# Sheet_1_2023-10-08.net
KiCad netlist of a schematic drawn in Altium Designer
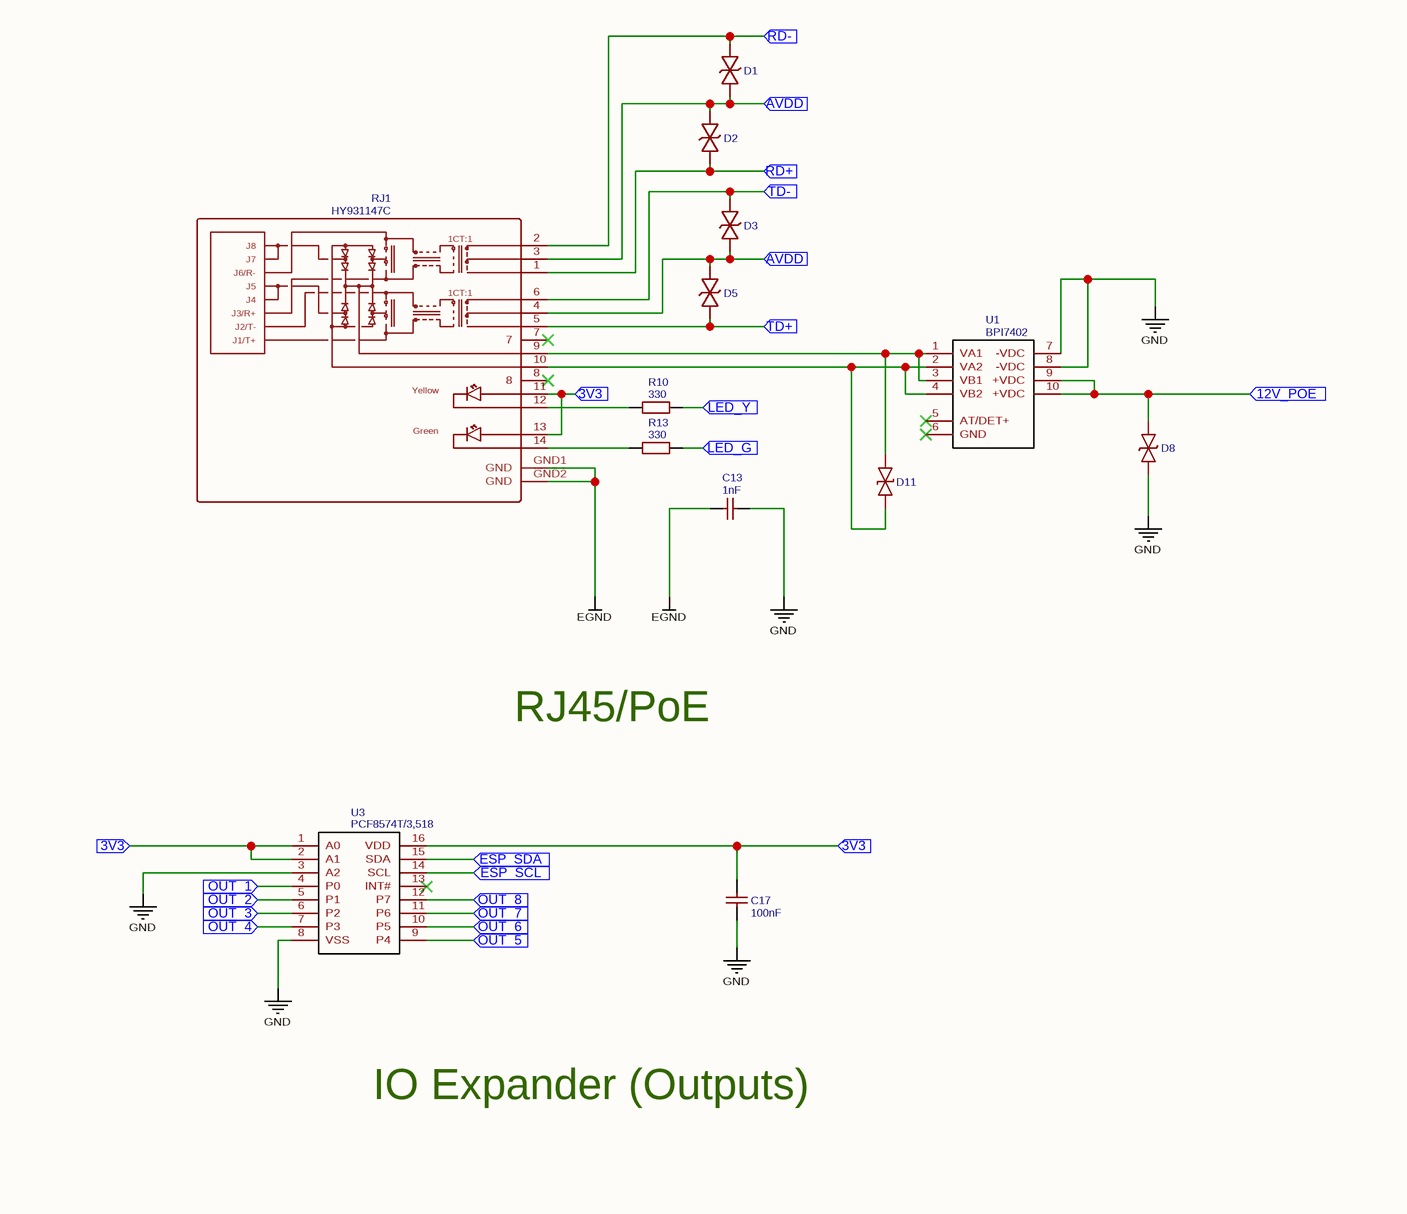
[diagram p0: Sheet_1_2023-10-08.schdoc, top left]
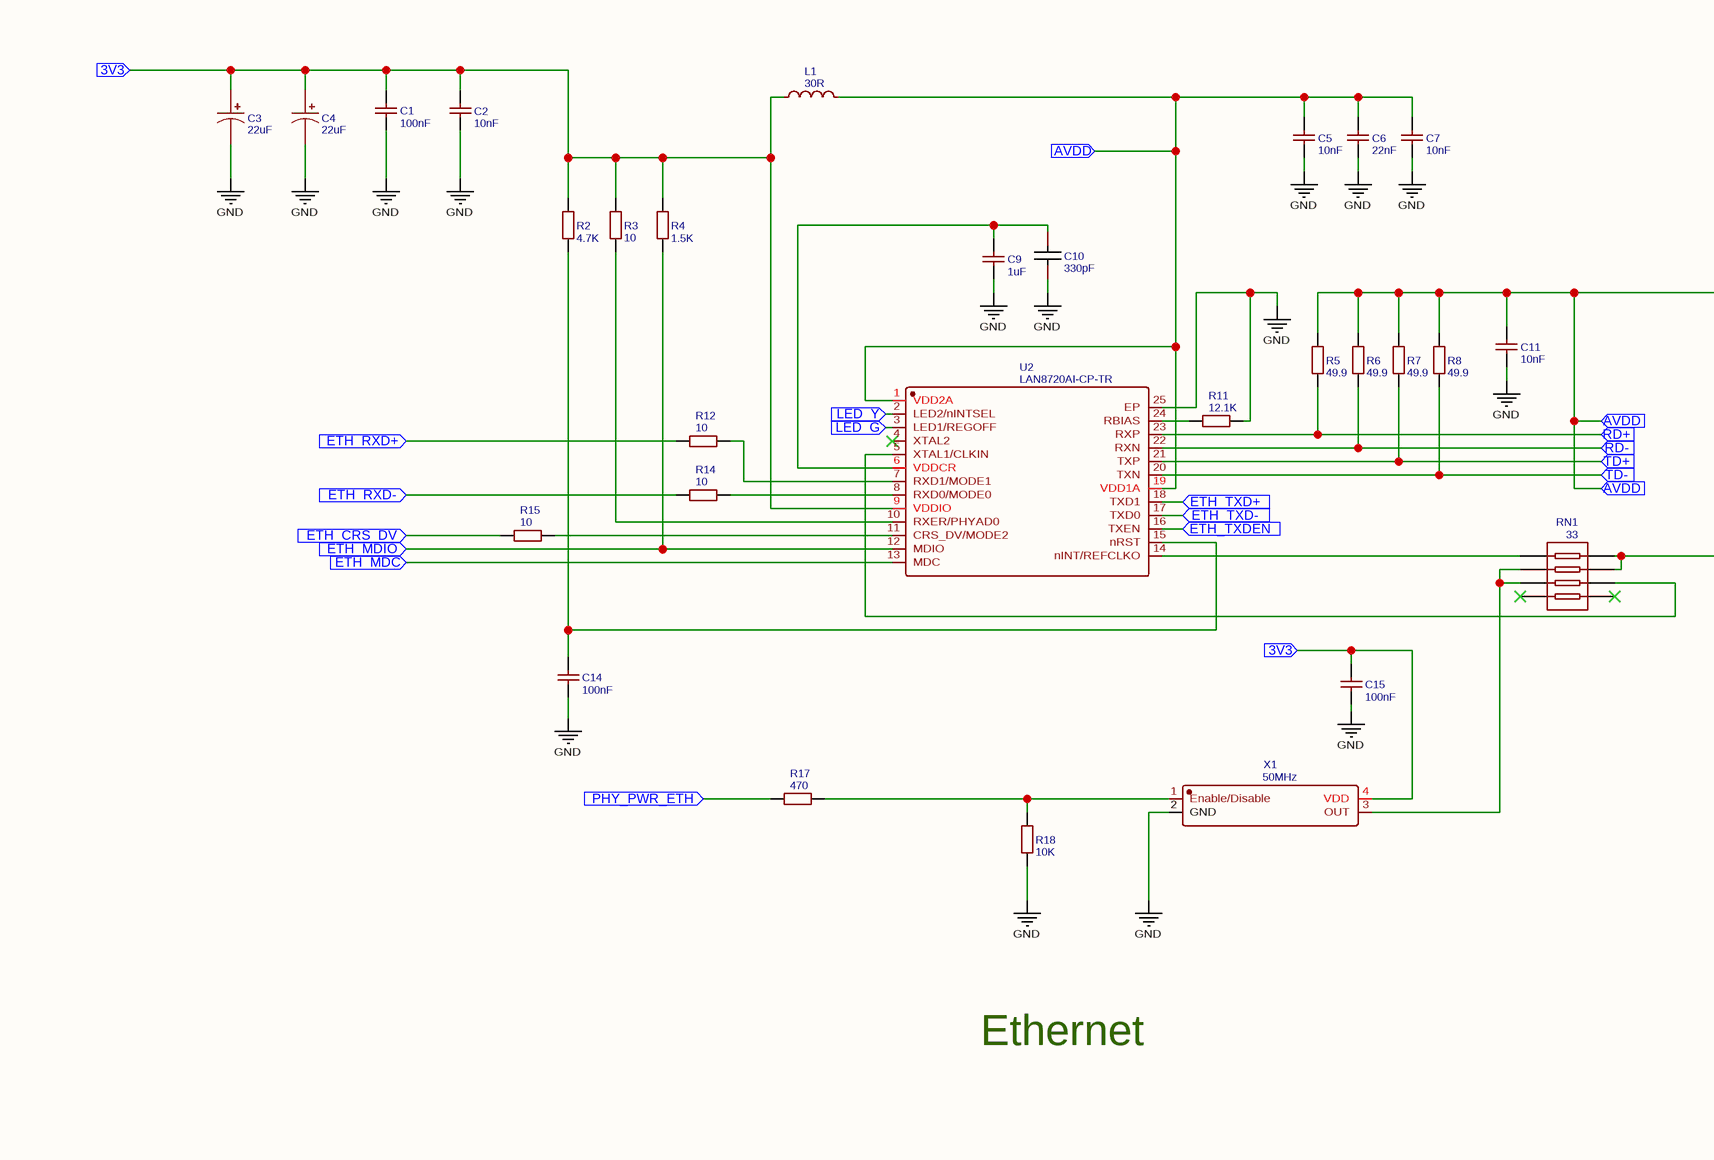
[diagram p1: Sheet_1_2023-10-08.schdoc, top middle]
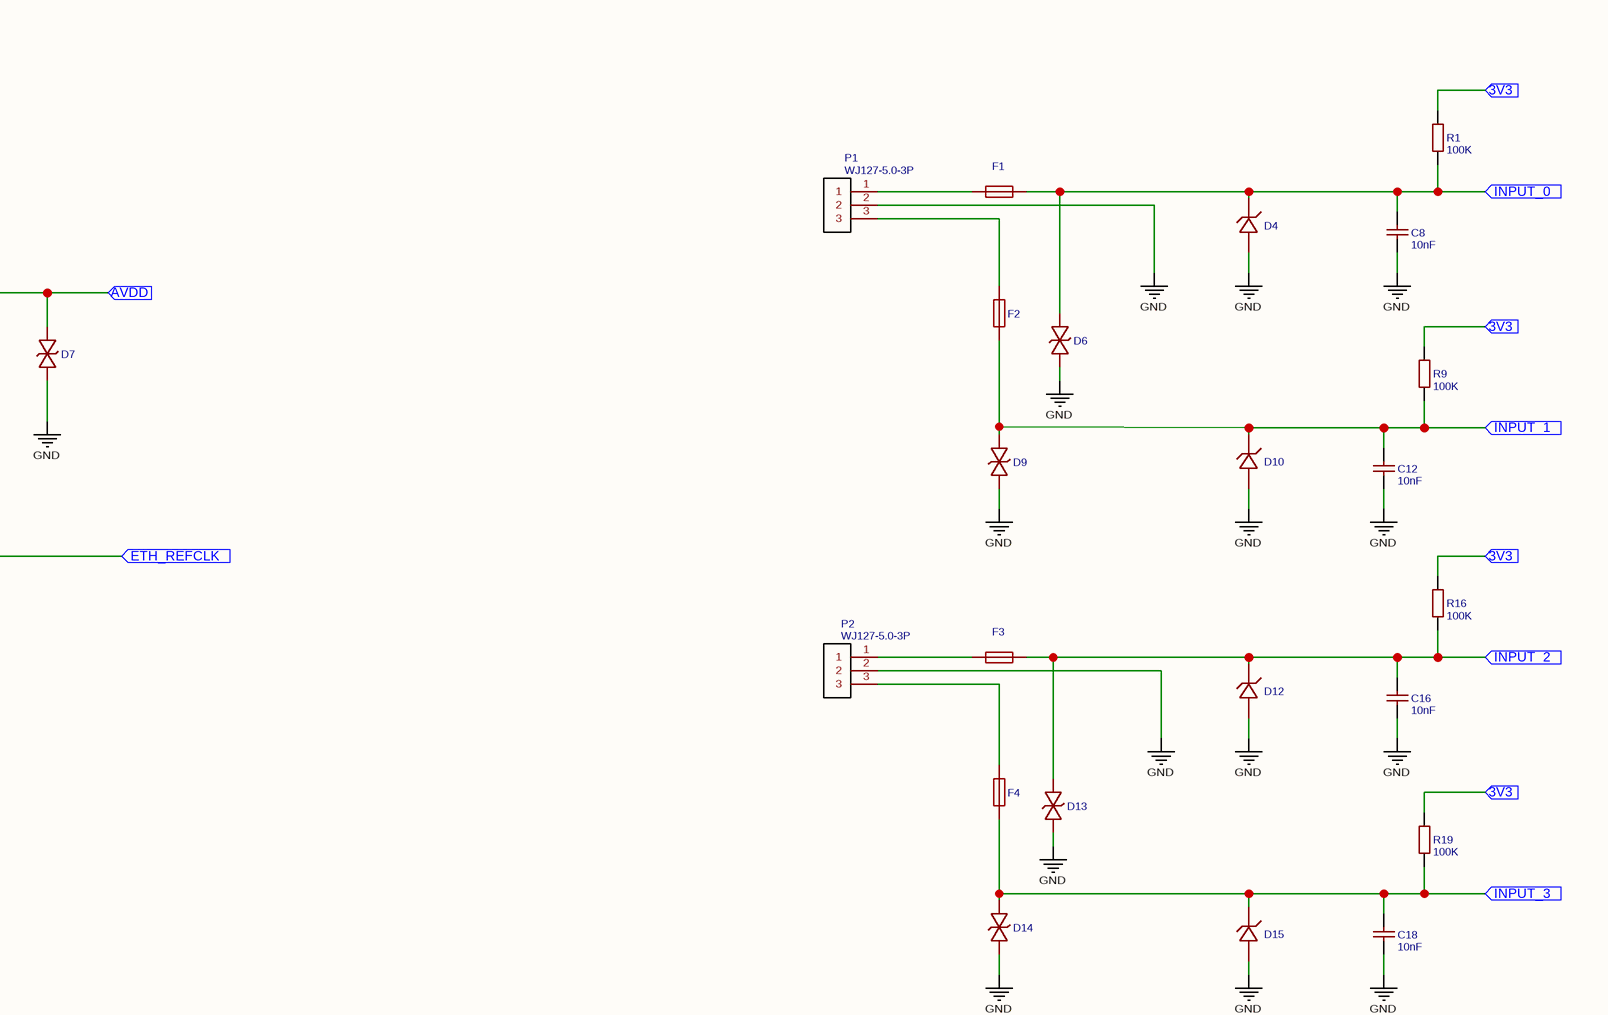
[diagram p2: Sheet_1_2023-10-08.schdoc, top right]
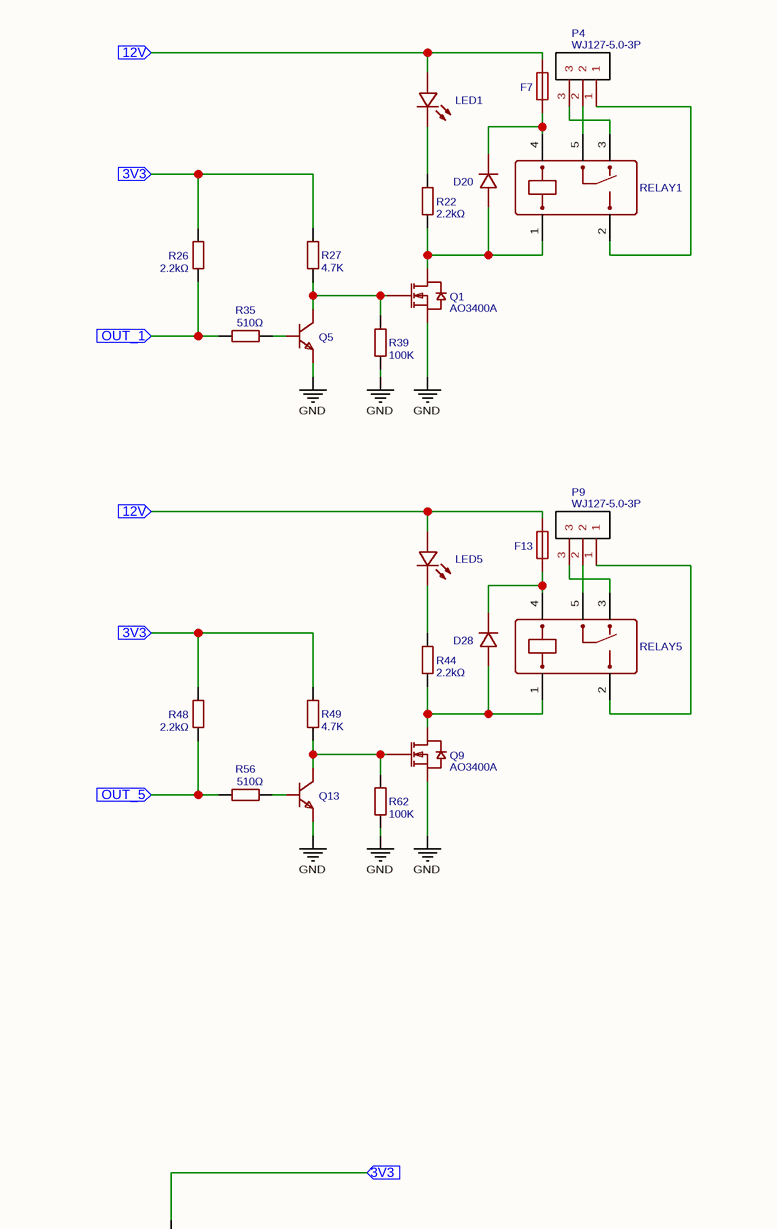
[diagram p3: Sheet_1_2023-10-08.schdoc, centre left]
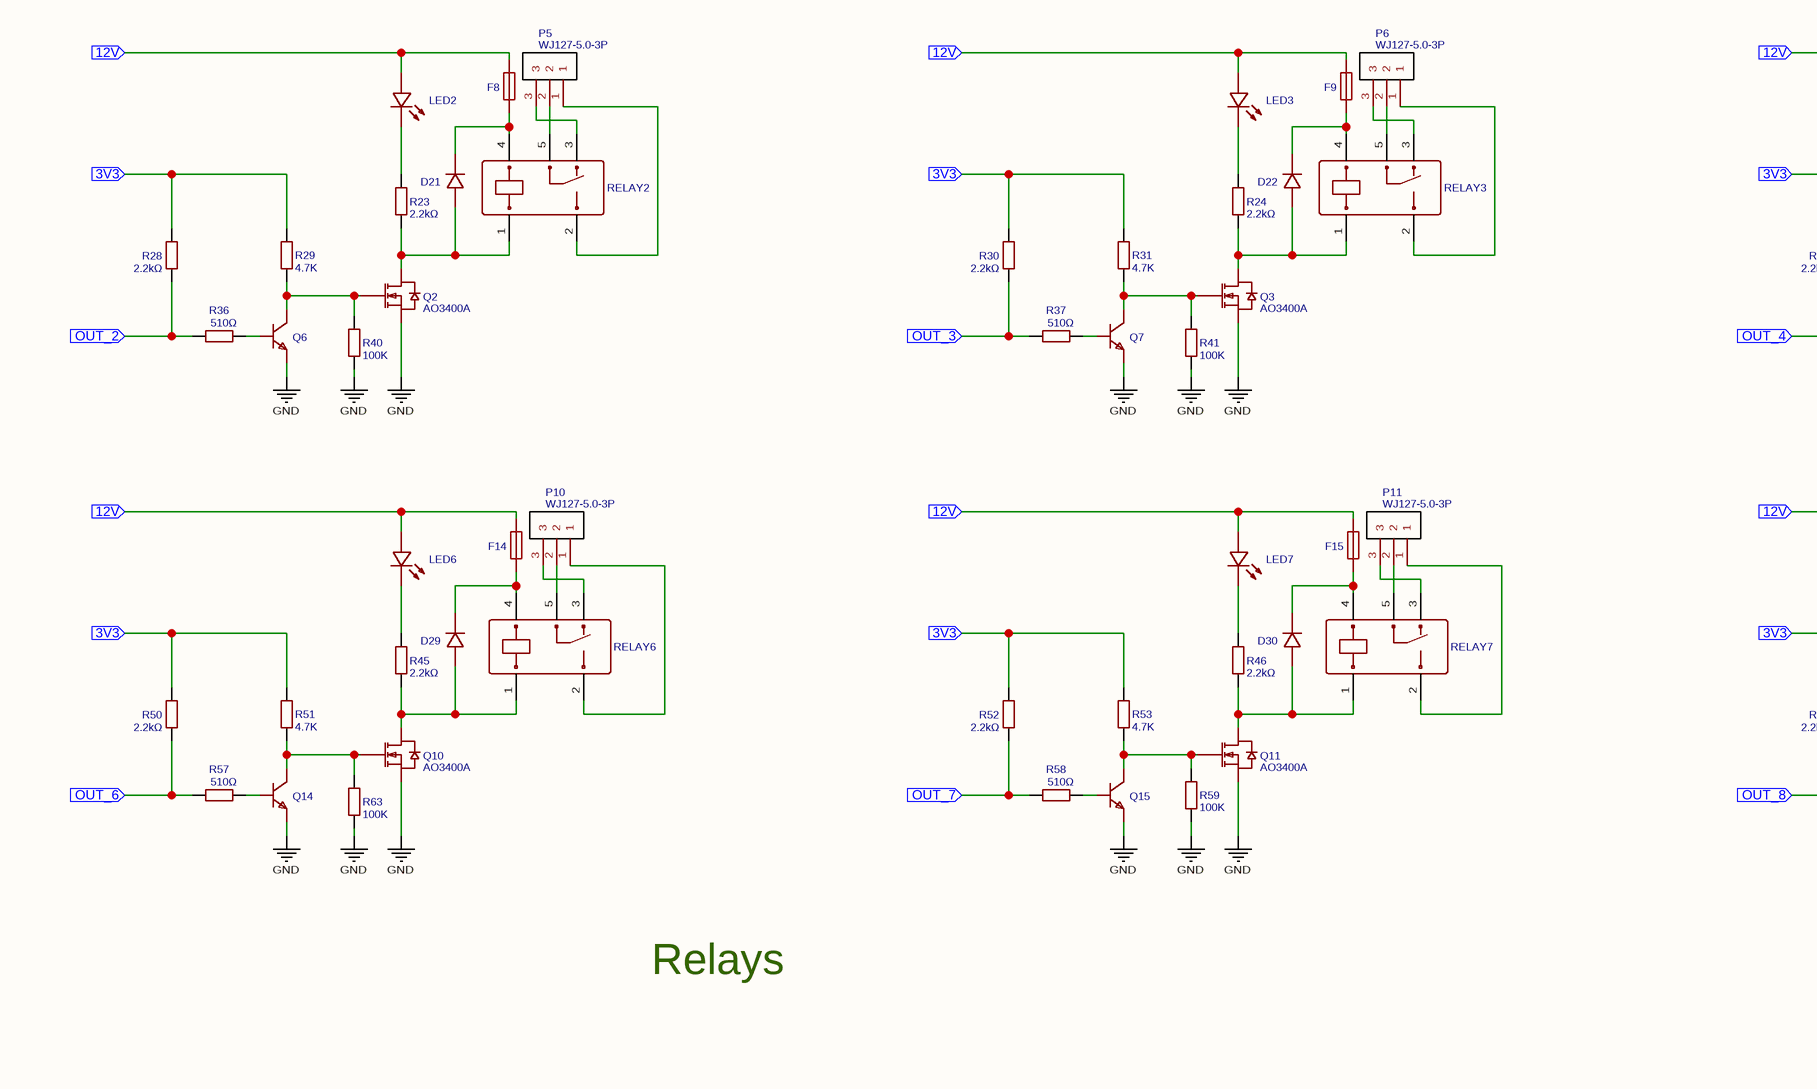
[diagram p4: Sheet_1_2023-10-08.schdoc, centre middle]
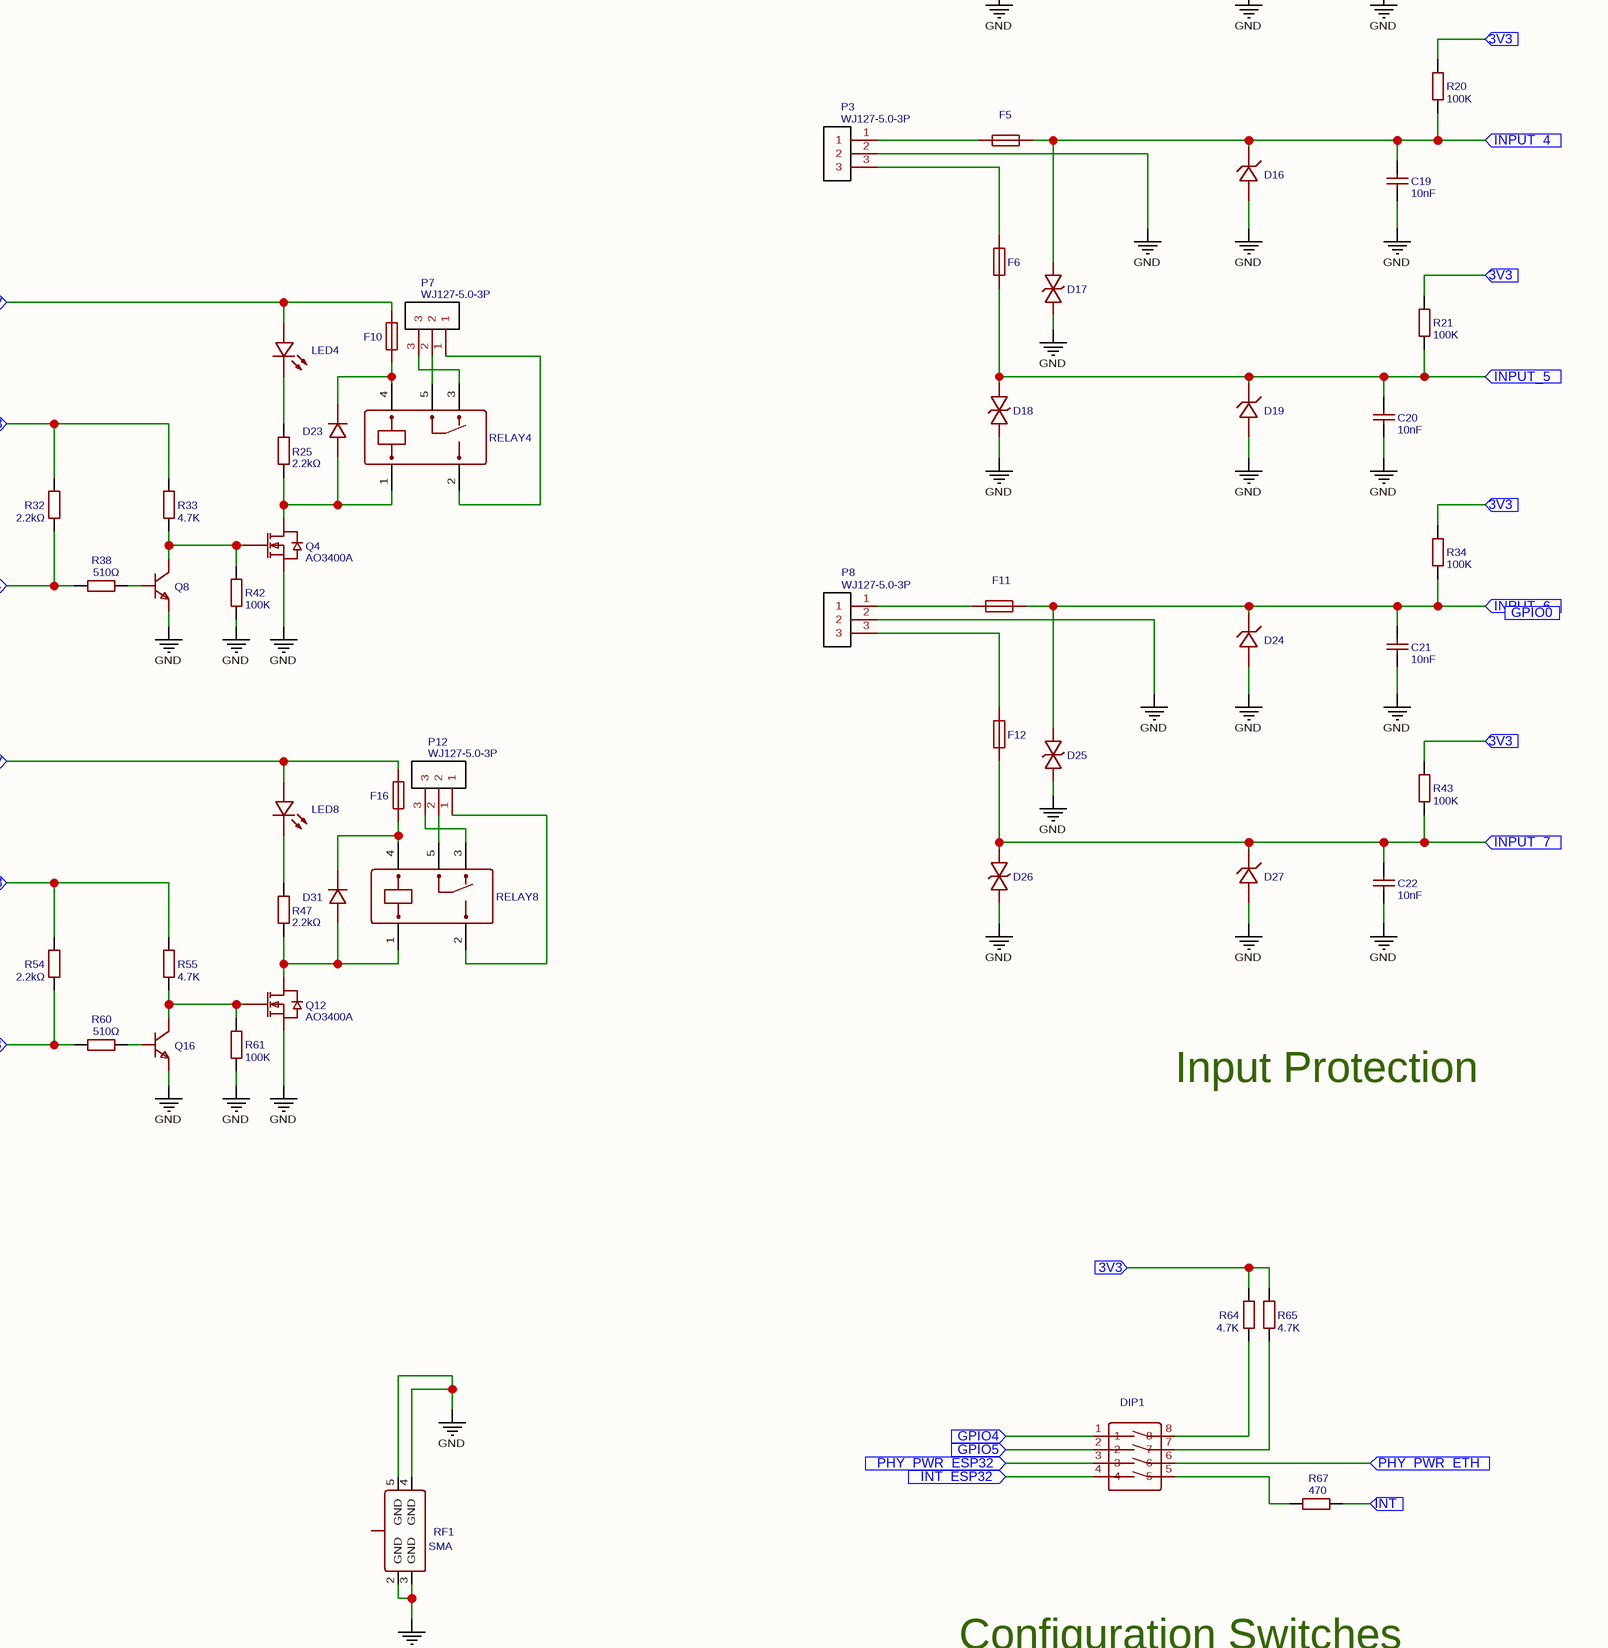
[diagram p5: Sheet_1_2023-10-08.schdoc, centre right]
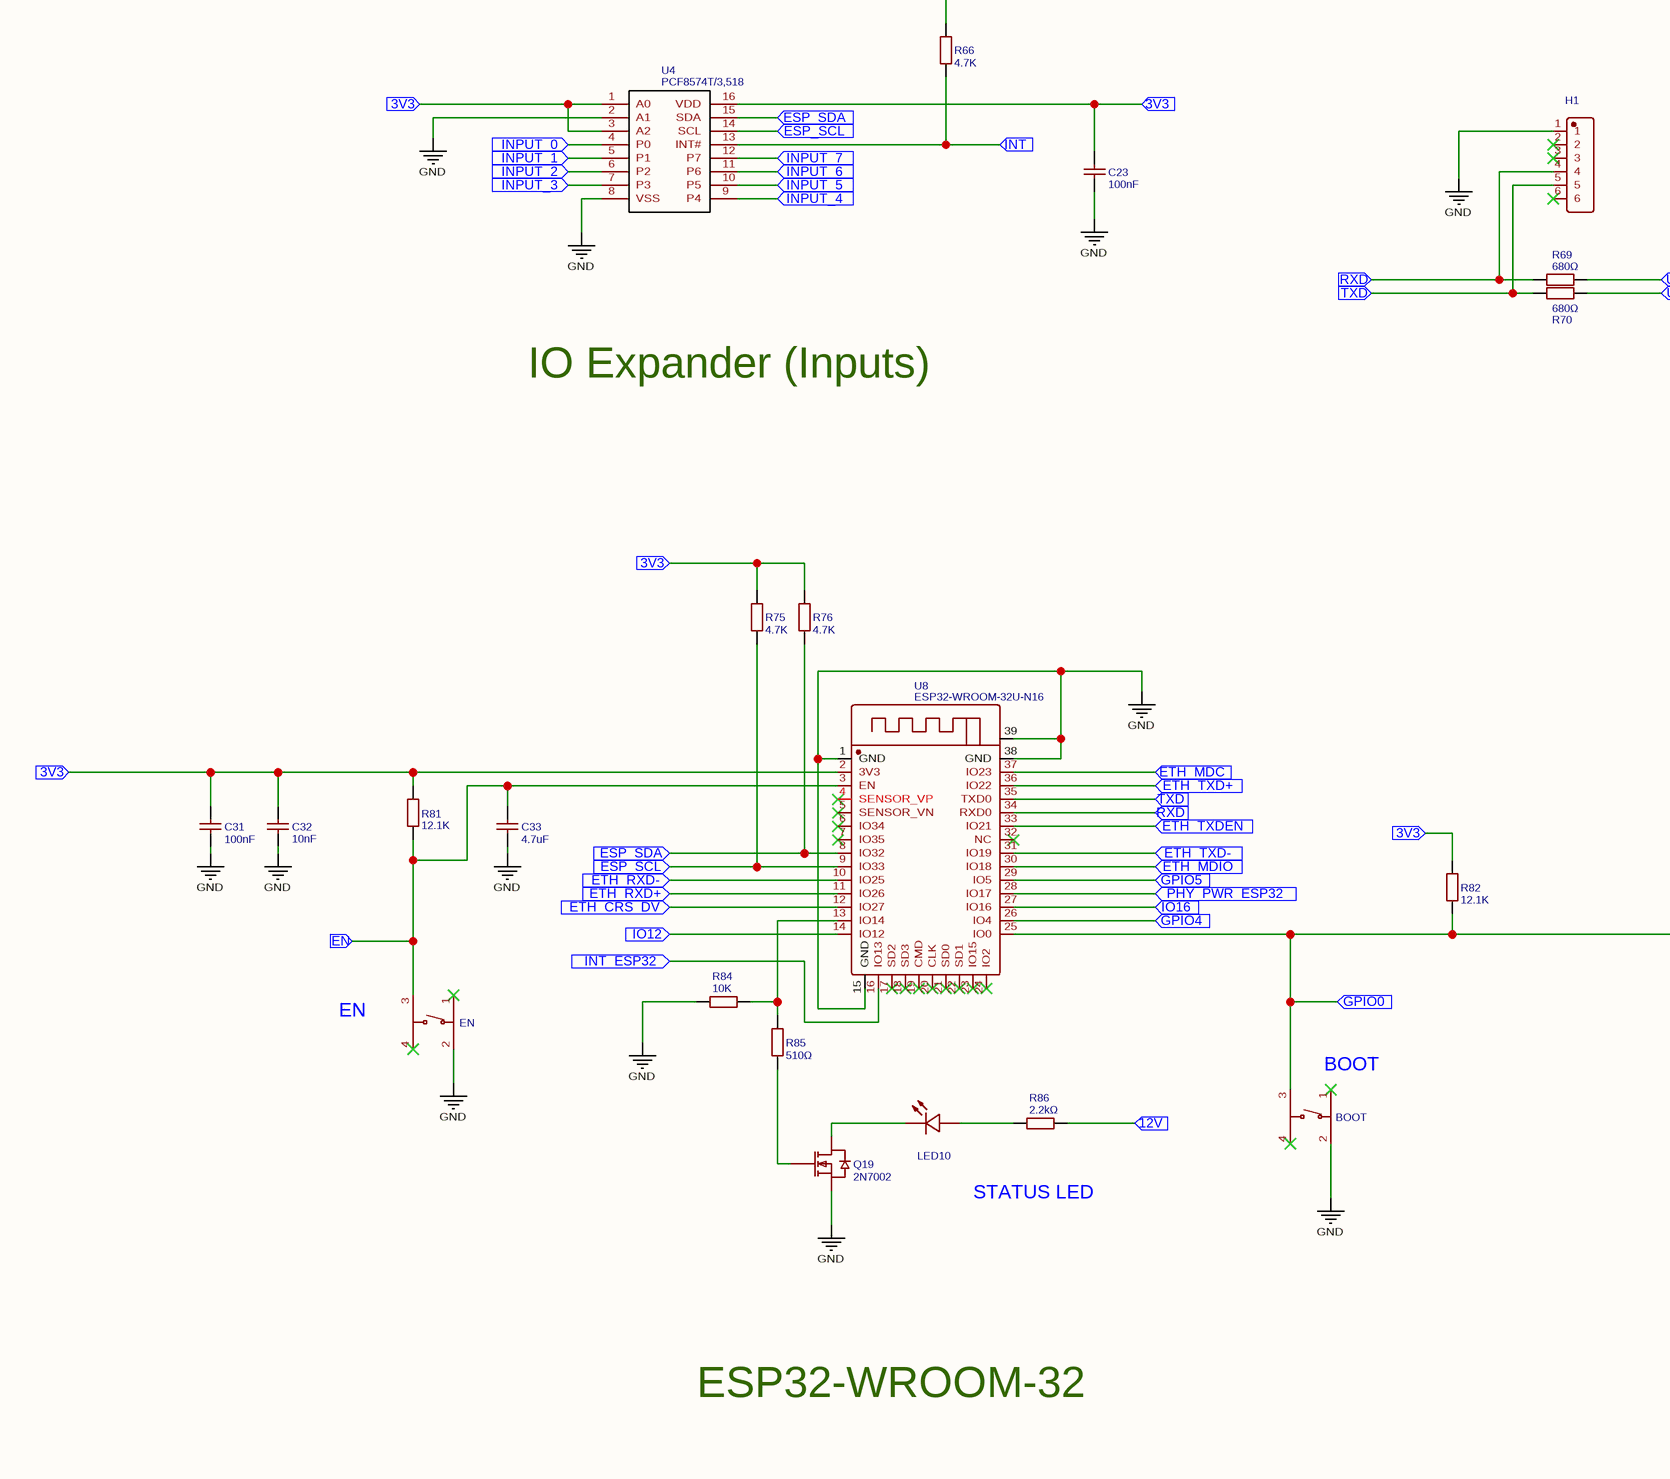
[diagram p6: Sheet_1_2023-10-08.schdoc, bottom left]
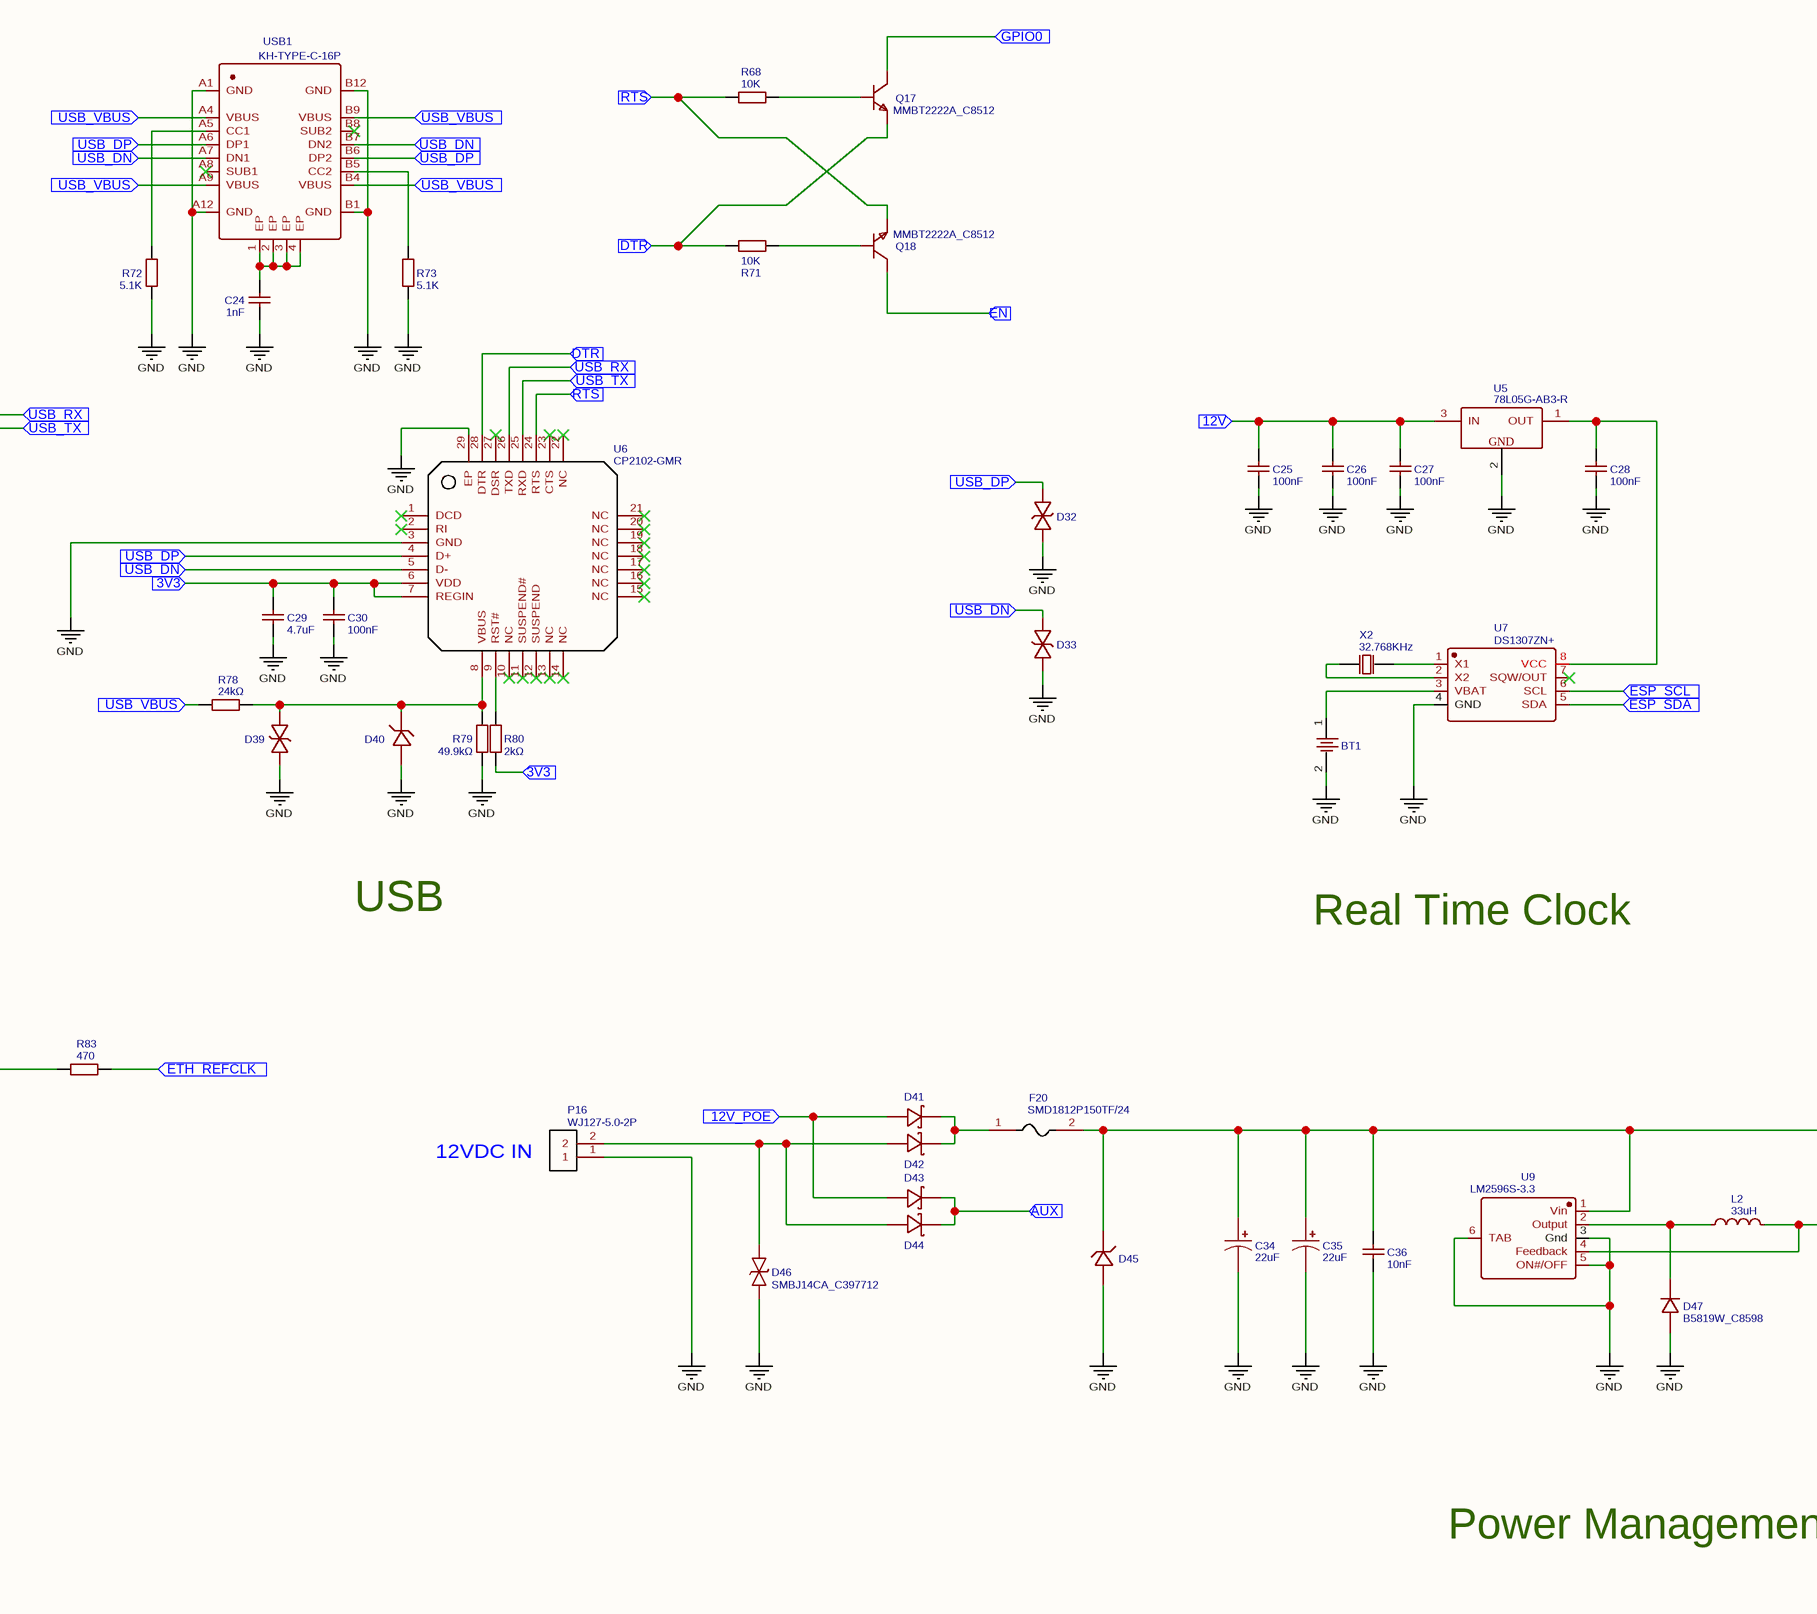
[diagram p7: Sheet_1_2023-10-08.schdoc, bottom middle]
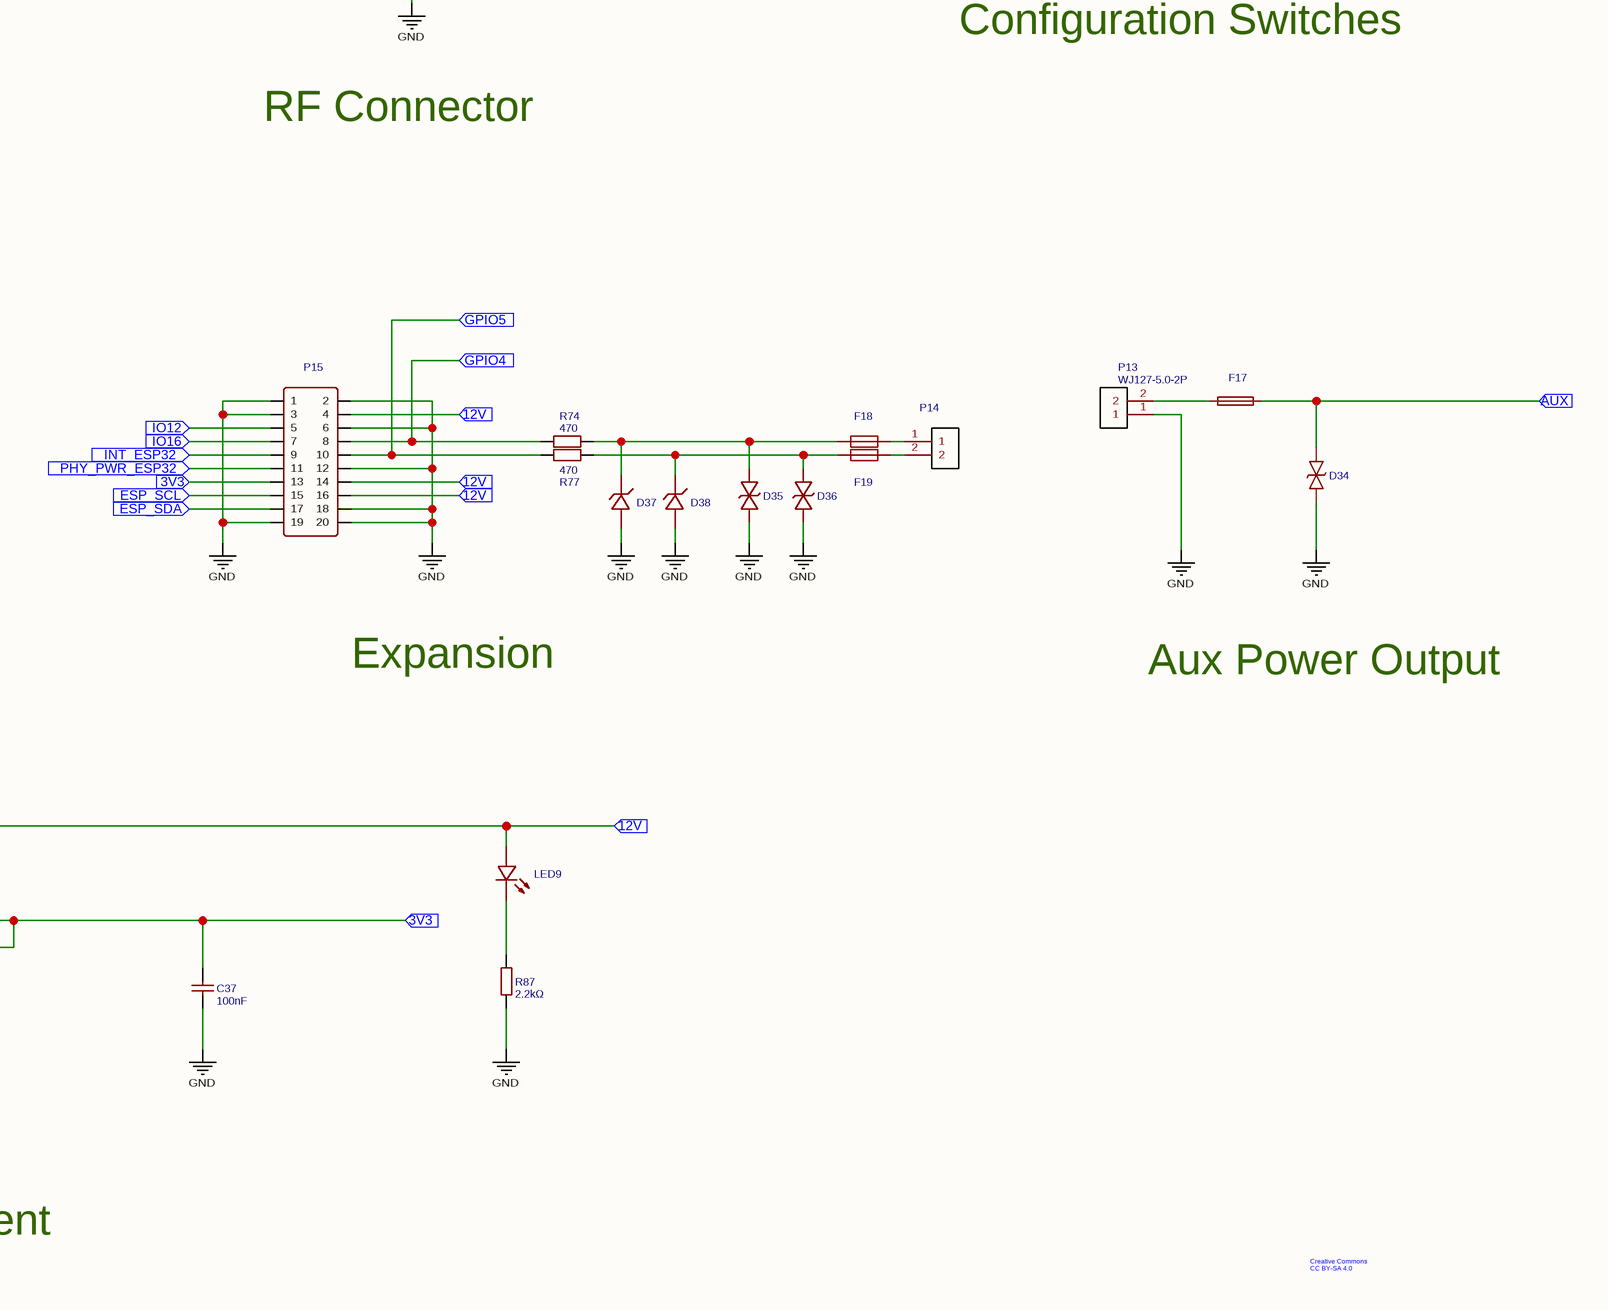
[diagram p8: Sheet_1_2023-10-08.schdoc, bottom right]

(export (version "E")
  (design (tool "Eeschema 10.0.6"))
  (components
    (comp (ref "BOOT")
      (value "TS-1187A-B-A-B")
      (fields (field (name "BOM_SUPPLIER PART") "C318884") (field (name "CONTRIBUTOR") "LCSC"))
      (libsource (lib "altium-import") (part "root_3_TS-1187A-B-A-B_"))
    )
    (comp (ref "BT1")
      (value "BS-12-A1AJ002-F")
      (fields (field (name "BOM_SUPPLIER PART") "C964720") (field (name "CONTRIBUTOR") "LCSC"))
      (libsource (lib "altium-import") (part "root_3_BS-12-A1AJ002-F_"))
    )
    (comp (ref "C1")
      (value "100nF")
      (fields
        (field (name "BOM_MANUFACTURER PART") "CL05B104KO5NNNC")
        (field (name "BOM_SUPPLIER PART") "C1525")
      )
      (libsource (lib "altium-import") (part "root_3_100nF_"))
    )
    (comp (ref "C2")
      (value "10nF")
      (fields
        (field (name "BOM_MANUFACTURER PART") "CL05B103KB5NNNC")
        (field (name "BOM_SUPPLIER PART") "C15195")
      )
      (libsource (lib "altium-import") (part "root_3_10nF_"))
    )
    (comp (ref "C3")
      (value "22uF")
      (fields
        (field (name "BOM_SUPPLIER PART") "C512951")
        (field (name "BOM_MANUFACTURER PART") "CN035M220LO5*11L-1A4T")
        (field (name "CONTRIBUTOR") "LCSC")
      )
      (libsource (lib "altium-import") (part "root_0_22uF_"))
    )
    (comp (ref "C4")
      (value "22uF")
      (fields
        (field (name "BOM_SUPPLIER PART") "C512951")
        (field (name "BOM_MANUFACTURER PART") "CN035M220LO5*11L-1A4T")
        (field (name "CONTRIBUTOR") "LCSC")
      )
      (libsource (lib "altium-import") (part "root_0_22uF_"))
    )
    (comp (ref "C5")
      (value "10nF")
      (fields
        (field (name "BOM_MANUFACTURER PART") "CL05B103KB5NNNC")
        (field (name "BOM_SUPPLIER PART") "C15195")
      )
      (libsource (lib "altium-import") (part "root_3_10nF_"))
    )
    (comp (ref "C6")
      (value "22nF")
      (fields
        (field (name "BOM_MANUFACTURER PART") "0402B223K500NT")
        (field (name "BOM_SUPPLIER PART") "C1532")
      )
      (libsource (lib "altium-import") (part "root_3_22nF_"))
    )
    (comp (ref "C7")
      (value "10nF")
      (fields
        (field (name "BOM_MANUFACTURER PART") "CL05B103KB5NNNC")
        (field (name "BOM_SUPPLIER PART") "C15195")
      )
      (libsource (lib "altium-import") (part "root_3_10nF_"))
    )
    (comp (ref "C8")
      (value "10nF")
      (fields
        (field (name "BOM_MANUFACTURER PART") "CL05B103KB5NNNC")
        (field (name "BOM_SUPPLIER PART") "C15195")
      )
      (libsource (lib "altium-import") (part "root_3_10nF_"))
    )
    (comp (ref "C9")
      (value "1uF")
      (fields
        (field (name "BOM_MANUFACTURER PART") "CL10A105KB8NNNC")
        (field (name "BOM_SUPPLIER PART") "C15849")
      )
      (libsource (lib "altium-import") (part "root_3_1uF_"))
    )
    (comp (ref "C10")
      (value "330pF")
      (fields
        (field (name "BOM_MANUFACTURER PART") "CL05C331JB5NNNC")
        (field (name "BOM_SUPPLIER PART") "C13533")
      )
      (libsource (lib "altium-import") (part "root_3_330pF_"))
    )
    (comp (ref "C11")
      (value "10nF")
      (fields
        (field (name "BOM_MANUFACTURER PART") "CL05B103KB5NNNC")
        (field (name "BOM_SUPPLIER PART") "C15195")
      )
      (libsource (lib "altium-import") (part "root_3_10nF_"))
    )
    (comp (ref "C12")
      (value "10nF")
      (fields
        (field (name "BOM_MANUFACTURER PART") "CL05B103KB5NNNC")
        (field (name "BOM_SUPPLIER PART") "C15195")
      )
      (libsource (lib "altium-import") (part "root_3_10nF_"))
    )
    (comp (ref "C13")
      (value "1nF")
      (fields
        (field (name "BOM_MANUFACTURER PART") "1206B102K202NT")
        (field (name "BOM_SUPPLIER PART") "C9196")
      )
      (libsource (lib "altium-import") (part "root_0_1nF_"))
    )
    (comp (ref "C14")
      (value "100nF")
      (fields
        (field (name "BOM_MANUFACTURER PART") "CL05B104KO5NNNC")
        (field (name "BOM_SUPPLIER PART") "C1525")
      )
      (libsource (lib "altium-import") (part "root_3_100nF_"))
    )
    (comp (ref "C15")
      (value "100nF")
      (fields
        (field (name "BOM_MANUFACTURER PART") "CL05B104KO5NNNC")
        (field (name "BOM_SUPPLIER PART") "C1525")
      )
      (libsource (lib "altium-import") (part "root_3_100nF_"))
    )
    (comp (ref "C16")
      (value "10nF")
      (fields
        (field (name "BOM_MANUFACTURER PART") "CL05B103KB5NNNC")
        (field (name "BOM_SUPPLIER PART") "C15195")
      )
      (libsource (lib "altium-import") (part "root_3_10nF_"))
    )
    (comp (ref "C17")
      (value "100nF")
      (fields
        (field (name "BOM_MANUFACTURER PART") "CL05B104KO5NNNC")
        (field (name "BOM_SUPPLIER PART") "C1525")
      )
      (libsource (lib "altium-import") (part "root_3_100nF_"))
    )
    (comp (ref "C18")
      (value "10nF")
      (fields
        (field (name "BOM_MANUFACTURER PART") "CL05B103KB5NNNC")
        (field (name "BOM_SUPPLIER PART") "C15195")
      )
      (libsource (lib "altium-import") (part "root_3_10nF_"))
    )
    (comp (ref "C19")
      (value "10nF")
      (fields
        (field (name "BOM_MANUFACTURER PART") "CL05B103KB5NNNC")
        (field (name "BOM_SUPPLIER PART") "C15195")
      )
      (libsource (lib "altium-import") (part "root_3_10nF_"))
    )
    (comp (ref "C20")
      (value "10nF")
      (fields
        (field (name "BOM_MANUFACTURER PART") "CL05B103KB5NNNC")
        (field (name "BOM_SUPPLIER PART") "C15195")
      )
      (libsource (lib "altium-import") (part "root_3_10nF_"))
    )
    (comp (ref "C21")
      (value "10nF")
      (fields
        (field (name "BOM_MANUFACTURER PART") "CL05B103KB5NNNC")
        (field (name "BOM_SUPPLIER PART") "C15195")
      )
      (libsource (lib "altium-import") (part "root_3_10nF_"))
    )
    (comp (ref "C22")
      (value "10nF")
      (fields
        (field (name "BOM_MANUFACTURER PART") "CL05B103KB5NNNC")
        (field (name "BOM_SUPPLIER PART") "C15195")
      )
      (libsource (lib "altium-import") (part "root_3_10nF_"))
    )
    (comp (ref "C23")
      (value "100nF")
      (fields
        (field (name "BOM_MANUFACTURER PART") "CL05B104KO5NNNC")
        (field (name "BOM_SUPPLIER PART") "C1525")
      )
      (libsource (lib "altium-import") (part "root_3_100nF_"))
    )
    (comp (ref "C24")
      (value "1nF")
      (fields
        (field (name "BOM_MANUFACTURER PART") "1206B102K202NT")
        (field (name "BOM_SUPPLIER PART") "C9196")
      )
      (libsource (lib "altium-import") (part "root_3_1nF_"))
    )
    (comp (ref "C25")
      (value "100nF")
      (fields
        (field (name "BOM_MANUFACTURER PART") "CL05B104KO5NNNC")
        (field (name "BOM_SUPPLIER PART") "C1525")
      )
      (libsource (lib "altium-import") (part "root_3_100nF_"))
    )
    (comp (ref "C26")
      (value "100nF")
      (fields
        (field (name "BOM_MANUFACTURER PART") "CL05B104KO5NNNC")
        (field (name "BOM_SUPPLIER PART") "C1525")
      )
      (libsource (lib "altium-import") (part "root_3_100nF_"))
    )
    (comp (ref "C27")
      (value "100nF")
      (fields
        (field (name "BOM_MANUFACTURER PART") "CL05B104KO5NNNC")
        (field (name "BOM_SUPPLIER PART") "C1525")
      )
      (libsource (lib "altium-import") (part "root_3_100nF_"))
    )
    (comp (ref "C28")
      (value "100nF")
      (fields
        (field (name "BOM_MANUFACTURER PART") "CL05B104KO5NNNC")
        (field (name "BOM_SUPPLIER PART") "C1525")
      )
      (libsource (lib "altium-import") (part "root_3_100nF_"))
    )
    (comp (ref "C29")
      (value "4.7uF")
      (fields
        (field (name "BOM_MANUFACTURER PART") "1206B475K500NT")
        (field (name "BOM_SUPPLIER PART") "C29823")
      )
      (libsource (lib "altium-import") (part "root_1_4.7uF_"))
    )
    (comp (ref "C30")
      (value "100nF")
      (fields
        (field (name "BOM_MANUFACTURER PART") "CL05B104KO5NNNC")
        (field (name "BOM_SUPPLIER PART") "C1525")
      )
      (libsource (lib "altium-import") (part "root_3_100nF_"))
    )
    (comp (ref "C31")
      (value "100nF")
      (fields
        (field (name "BOM_MANUFACTURER PART") "CL05B104KO5NNNC")
        (field (name "BOM_SUPPLIER PART") "C1525")
      )
      (libsource (lib "altium-import") (part "root_3_100nF_"))
    )
    (comp (ref "C32")
      (value "10nF")
      (fields
        (field (name "BOM_MANUFACTURER PART") "CL05B103KB5NNNC")
        (field (name "BOM_SUPPLIER PART") "C15195")
      )
      (libsource (lib "altium-import") (part "root_3_10nF_"))
    )
    (comp (ref "C33")
      (value "4.7uF")
      (fields
        (field (name "BOM_MANUFACTURER PART") "1206B475K500NT")
        (field (name "BOM_SUPPLIER PART") "C29823")
      )
      (libsource (lib "altium-import") (part "root_1_4.7uF_"))
    )
    (comp (ref "C34")
      (value "22uF")
      (fields
        (field (name "BOM_SUPPLIER PART") "C512951")
        (field (name "BOM_MANUFACTURER PART") "CN035M220LO5*11L-1A4T")
        (field (name "CONTRIBUTOR") "LCSC")
      )
      (libsource (lib "altium-import") (part "root_0_22uF_"))
    )
    (comp (ref "C35")
      (value "22uF")
      (fields
        (field (name "BOM_SUPPLIER PART") "C512951")
        (field (name "BOM_MANUFACTURER PART") "CN035M220LO5*11L-1A4T")
        (field (name "CONTRIBUTOR") "LCSC")
      )
      (libsource (lib "altium-import") (part "root_0_22uF_"))
    )
    (comp (ref "C36")
      (value "10nF")
      (fields
        (field (name "BOM_MANUFACTURER PART") "CL21B103KBANNNC")
        (field (name "BOM_SUPPLIER PART") "C1710")
      )
      (libsource (lib "altium-import") (part "root_3_10nF_"))
    )
    (comp (ref "C37")
      (value "100nF")
      (fields
        (field (name "BOM_MANUFACTURER PART") "CL05B104KO5NNNC")
        (field (name "BOM_SUPPLIER PART") "C1525")
      )
      (libsource (lib "altium-import") (part "root_3_100nF_"))
    )
    (comp (ref "D1")
      (value "PESD03V32D-LC")
      (fields (field (name "BOM_SUPPLIER PART") "C2912528") (field (name "CONTRIBUTOR") "LCSC"))
      (libsource (lib "altium-import") (part "root_3_PESD03V32D-LC_"))
    )
    (comp (ref "D2")
      (value "PESD03V32D-LC")
      (fields (field (name "BOM_SUPPLIER PART") "C2912528") (field (name "CONTRIBUTOR") "LCSC"))
      (libsource (lib "altium-import") (part "root_3_PESD03V32D-LC_"))
    )
    (comp (ref "D3")
      (value "PESD03V32D-LC")
      (fields (field (name "BOM_SUPPLIER PART") "C2912528") (field (name "CONTRIBUTOR") "LCSC"))
      (libsource (lib "altium-import") (part "root_3_PESD03V32D-LC_"))
    )
    (comp (ref "D4")
      (value "ZMM3V3")
      (fields (field (name "BOM_SUPPLIER PART") "C8056"))
      (libsource (lib "altium-import") (part "root_3_ZMM3V3_"))
    )
    (comp (ref "D5")
      (value "PESD03V32D-LC")
      (fields (field (name "BOM_SUPPLIER PART") "C2912528") (field (name "CONTRIBUTOR") "LCSC"))
      (libsource (lib "altium-import") (part "root_3_PESD03V32D-LC_"))
    )
    (comp (ref "D6")
      (value "PESD03V32D-LC")
      (fields (field (name "BOM_SUPPLIER PART") "C2912528") (field (name "CONTRIBUTOR") "LCSC"))
      (libsource (lib "altium-import") (part "root_3_PESD03V32D-LC_"))
    )
    (comp (ref "D7")
      (value "PESD03V32D-LC")
      (fields (field (name "BOM_SUPPLIER PART") "C2912528") (field (name "CONTRIBUTOR") "LCSC"))
      (libsource (lib "altium-import") (part "root_3_PESD03V32D-LC_"))
    )
    (comp (ref "D8")
      (value "SMBJ14CA_C397712")
      (fields
        (field (name "BOM_SUPPLIER PART") "C397712")
        (field (name "BOM_MANUFACTURER PART") "SMBJ14CA")
        (field (name "CONTRIBUTOR") "LCSC")
      )
      (libsource (lib "altium-import") (part "root_3_SMBJ14CA_C397712_"))
    )
    (comp (ref "D9")
      (value "PESD03V32D-LC")
      (fields (field (name "BOM_SUPPLIER PART") "C2912528") (field (name "CONTRIBUTOR") "LCSC"))
      (libsource (lib "altium-import") (part "root_3_PESD03V32D-LC_"))
    )
    (comp (ref "D10")
      (value "ZMM3V3")
      (fields (field (name "BOM_SUPPLIER PART") "C8056"))
      (libsource (lib "altium-import") (part "root_3_ZMM3V3_"))
    )
    (comp (ref "D11")
      (value "SMBJ64CA")
      (fields (field (name "BOM_SUPPLIER PART") "C123975") (field (name "CONTRIBUTOR") "LCSC"))
      (libsource (lib "altium-import") (part "root_3_SMBJ64CA_"))
    )
    (comp (ref "D12")
      (value "ZMM3V3")
      (fields (field (name "BOM_SUPPLIER PART") "C8056"))
      (libsource (lib "altium-import") (part "root_3_ZMM3V3_"))
    )
    (comp (ref "D13")
      (value "PESD03V32D-LC")
      (fields (field (name "BOM_SUPPLIER PART") "C2912528") (field (name "CONTRIBUTOR") "LCSC"))
      (libsource (lib "altium-import") (part "root_3_PESD03V32D-LC_"))
    )
    (comp (ref "D14")
      (value "PESD03V32D-LC")
      (fields (field (name "BOM_SUPPLIER PART") "C2912528") (field (name "CONTRIBUTOR") "LCSC"))
      (libsource (lib "altium-import") (part "root_3_PESD03V32D-LC_"))
    )
    (comp (ref "D15")
      (value "ZMM3V3")
      (fields (field (name "BOM_SUPPLIER PART") "C8056"))
      (libsource (lib "altium-import") (part "root_3_ZMM3V3_"))
    )
    (comp (ref "D16")
      (value "ZMM3V3")
      (fields (field (name "BOM_SUPPLIER PART") "C8056"))
      (libsource (lib "altium-import") (part "root_3_ZMM3V3_"))
    )
    (comp (ref "D17")
      (value "PESD03V32D-LC")
      (fields (field (name "BOM_SUPPLIER PART") "C2912528") (field (name "CONTRIBUTOR") "LCSC"))
      (libsource (lib "altium-import") (part "root_3_PESD03V32D-LC_"))
    )
    (comp (ref "D18")
      (value "PESD03V32D-LC")
      (fields (field (name "BOM_SUPPLIER PART") "C2912528") (field (name "CONTRIBUTOR") "LCSC"))
      (libsource (lib "altium-import") (part "root_3_PESD03V32D-LC_"))
    )
    (comp (ref "D19")
      (value "ZMM3V3")
      (fields (field (name "BOM_SUPPLIER PART") "C8056"))
      (libsource (lib "altium-import") (part "root_3_ZMM3V3_"))
    )
    (comp (ref "D20")
      (value "B5819W_C8598")
      (fields (field (name "BOM_MANUFACTURER PART") "B5819W") (field (name "BOM_SUPPLIER PART") "C8598"))
      (libsource (lib "altium-import") (part "root_1_B5819W_C8598_"))
    )
    (comp (ref "D21")
      (value "B5819W_C8598")
      (fields (field (name "BOM_MANUFACTURER PART") "B5819W") (field (name "BOM_SUPPLIER PART") "C8598"))
      (libsource (lib "altium-import") (part "root_1_B5819W_C8598_"))
    )
    (comp (ref "D22")
      (value "B5819W_C8598")
      (fields (field (name "BOM_MANUFACTURER PART") "B5819W") (field (name "BOM_SUPPLIER PART") "C8598"))
      (libsource (lib "altium-import") (part "root_1_B5819W_C8598_"))
    )
    (comp (ref "D23")
      (value "B5819W_C8598")
      (fields (field (name "BOM_MANUFACTURER PART") "B5819W") (field (name "BOM_SUPPLIER PART") "C8598"))
      (libsource (lib "altium-import") (part "root_1_B5819W_C8598_"))
    )
    (comp (ref "D24")
      (value "ZMM3V3")
      (fields (field (name "BOM_SUPPLIER PART") "C8056"))
      (libsource (lib "altium-import") (part "root_3_ZMM3V3_"))
    )
    (comp (ref "D25")
      (value "PESD03V32D-LC")
      (fields (field (name "BOM_SUPPLIER PART") "C2912528") (field (name "CONTRIBUTOR") "LCSC"))
      (libsource (lib "altium-import") (part "root_3_PESD03V32D-LC_"))
    )
    (comp (ref "D26")
      (value "PESD03V32D-LC")
      (fields (field (name "BOM_SUPPLIER PART") "C2912528") (field (name "CONTRIBUTOR") "LCSC"))
      (libsource (lib "altium-import") (part "root_3_PESD03V32D-LC_"))
    )
    (comp (ref "D27")
      (value "ZMM3V3")
      (fields (field (name "BOM_SUPPLIER PART") "C8056"))
      (libsource (lib "altium-import") (part "root_3_ZMM3V3_"))
    )
    (comp (ref "D28")
      (value "B5819W_C8598")
      (fields (field (name "BOM_MANUFACTURER PART") "B5819W") (field (name "BOM_SUPPLIER PART") "C8598"))
      (libsource (lib "altium-import") (part "root_1_B5819W_C8598_"))
    )
    (comp (ref "D29")
      (value "B5819W_C8598")
      (fields (field (name "BOM_MANUFACTURER PART") "B5819W") (field (name "BOM_SUPPLIER PART") "C8598"))
      (libsource (lib "altium-import") (part "root_1_B5819W_C8598_"))
    )
    (comp (ref "D30")
      (value "B5819W_C8598")
      (fields (field (name "BOM_MANUFACTURER PART") "B5819W") (field (name "BOM_SUPPLIER PART") "C8598"))
      (libsource (lib "altium-import") (part "root_1_B5819W_C8598_"))
    )
    (comp (ref "D31")
      (value "B5819W_C8598")
      (fields (field (name "BOM_MANUFACTURER PART") "B5819W") (field (name "BOM_SUPPLIER PART") "C8598"))
      (libsource (lib "altium-import") (part "root_1_B5819W_C8598_"))
    )
    (comp (ref "D32")
      (value "PESD03V32D-LC")
      (fields (field (name "BOM_SUPPLIER PART") "C2912528") (field (name "CONTRIBUTOR") "LCSC"))
      (libsource (lib "") (part "root_1_PESD03V32D-LC__1"))
    )
    (comp (ref "D33")
      (value "PESD03V32D-LC")
      (fields (field (name "BOM_SUPPLIER PART") "C2912528") (field (name "CONTRIBUTOR") "LCSC"))
      (libsource (lib "altium-import") (part "root_1_PESD03V32D-LC_"))
    )
    (comp (ref "D34")
      (value "SMBJ14CA_C397712")
      (fields
        (field (name "BOM_SUPPLIER PART") "C397712")
        (field (name "BOM_MANUFACTURER PART") "SMBJ14CA")
        (field (name "CONTRIBUTOR") "LCSC")
      )
      (libsource (lib "altium-import") (part "root_3_SMBJ14CA_C397712_"))
    )
    (comp (ref "D35")
      (value "PESD03V32D-LC")
      (fields (field (name "BOM_SUPPLIER PART") "C2912528") (field (name "CONTRIBUTOR") "LCSC"))
      (libsource (lib "altium-import") (part "root_3_PESD03V32D-LC_"))
    )
    (comp (ref "D36")
      (value "PESD03V32D-LC")
      (fields (field (name "BOM_SUPPLIER PART") "C2912528") (field (name "CONTRIBUTOR") "LCSC"))
      (libsource (lib "altium-import") (part "root_3_PESD03V32D-LC_"))
    )
    (comp (ref "D37")
      (value "ZMM3V3")
      (fields (field (name "BOM_SUPPLIER PART") "C8056"))
      (libsource (lib "altium-import") (part "root_3_ZMM3V3_"))
    )
    (comp (ref "D38")
      (value "ZMM3V3")
      (fields (field (name "BOM_SUPPLIER PART") "C8056"))
      (libsource (lib "altium-import") (part "root_3_ZMM3V3_"))
    )
    (comp (ref "D39")
      (value "PESD03V32D-LC")
      (fields (field (name "BOM_SUPPLIER PART") "C2912528") (field (name "CONTRIBUTOR") "LCSC"))
      (libsource (lib "altium-import") (part "root_1_PESD03V32D-LC_"))
    )
    (comp (ref "D40")
      (value "ZMM3V3")
      (fields (field (name "BOM_SUPPLIER PART") "C8056"))
      (libsource (lib "") (part "root_3_ZMM3V3__1"))
    )
    (comp (ref "D41")
      (value "SS34_C8678")
      (fields (field (name "BOM_MANUFACTURER PART") "SS34") (field (name "BOM_SUPPLIER PART") "C8678"))
      (libsource (lib "") (part "root_0_SS34_C8678__1"))
    )
    (comp (ref "D42")
      (value "SS34_C8678")
      (fields (field (name "BOM_MANUFACTURER PART") "SS34") (field (name "BOM_SUPPLIER PART") "C8678"))
      (libsource (lib "altium-import") (part "root_0_SS34_C8678_"))
    )
    (comp (ref "D43")
      (value "SS34_C8678")
      (fields (field (name "BOM_MANUFACTURER PART") "SS34") (field (name "BOM_SUPPLIER PART") "C8678"))
      (libsource (lib "") (part "root_0_SS34_C8678__1"))
    )
    (comp (ref "D44")
      (value "SS34_C8678")
      (fields (field (name "BOM_MANUFACTURER PART") "SS34") (field (name "BOM_SUPPLIER PART") "C8678"))
      (libsource (lib "altium-import") (part "root_0_SS34_C8678_"))
    )
    (comp (ref "D45")
      (value "2EZ13D5_C388131")
      (fields
        (field (name "BOM_SUPPLIER PART") "C388131")
        (field (name "BOM_MANUFACTURER PART") "2EZ13D5")
        (field (name "CONTRIBUTOR") "LCSC")
      )
      (libsource (lib "altium-import") (part "root_3_2EZ13D5_C388131_"))
    )
    (comp (ref "D46")
      (value "SMBJ14CA_C397712")
      (fields
        (field (name "BOM_SUPPLIER PART") "C397712")
        (field (name "BOM_MANUFACTURER PART") "SMBJ14CA")
        (field (name "CONTRIBUTOR") "LCSC")
      )
      (libsource (lib "altium-import") (part "root_3_SMBJ14CA_C397712_"))
    )
    (comp (ref "D47")
      (value "B5819W_C8598")
      (fields (field (name "BOM_MANUFACTURER PART") "B5819W") (field (name "BOM_SUPPLIER PART") "C8598"))
      (libsource (lib "altium-import") (part "root_3_B5819W_C8598_"))
    )
    (comp (ref "DIP1")
      (value "DSIC04LHGET")
      (fields (field (name "BOM_SUPPLIER PART") "C54959"))
      (libsource (lib "altium-import") (part "root_3_DSIC04LHGET_"))
    )
    (comp (ref "EN")
      (value "TS-1187A-B-A-B")
      (fields (field (name "BOM_SUPPLIER PART") "C318884") (field (name "CONTRIBUTOR") "LCSC"))
      (libsource (lib "altium-import") (part "root_3_TS-1187A-B-A-B_"))
    )
    (comp (ref "F1")
      (value "BSMD0603-002-60V")
      (fields (field (name "BOM_SUPPLIER PART") "C914089") (field (name "CONTRIBUTOR") "LCSC"))
      (libsource (lib "altium-import") (part "root_0_BSMD0603-002-60V_"))
    )
    (comp (ref "F2")
      (value "BSMD0603-002-60V")
      (fields (field (name "BOM_SUPPLIER PART") "C914089") (field (name "CONTRIBUTOR") "LCSC"))
      (libsource (lib "altium-import") (part "root_1_BSMD0603-002-60V_"))
    )
    (comp (ref "F3")
      (value "BSMD0603-002-60V")
      (fields (field (name "BOM_SUPPLIER PART") "C914089") (field (name "CONTRIBUTOR") "LCSC"))
      (libsource (lib "altium-import") (part "root_0_BSMD0603-002-60V_"))
    )
    (comp (ref "F4")
      (value "BSMD0603-002-60V")
      (fields (field (name "BOM_SUPPLIER PART") "C914089") (field (name "CONTRIBUTOR") "LCSC"))
      (libsource (lib "altium-import") (part "root_1_BSMD0603-002-60V_"))
    )
    (comp (ref "F5")
      (value "BSMD0603-002-60V")
      (fields (field (name "BOM_SUPPLIER PART") "C914089") (field (name "CONTRIBUTOR") "LCSC"))
      (libsource (lib "altium-import") (part "root_0_BSMD0603-002-60V_"))
    )
    (comp (ref "F6")
      (value "BSMD0603-002-60V")
      (fields (field (name "BOM_SUPPLIER PART") "C914089") (field (name "CONTRIBUTOR") "LCSC"))
      (libsource (lib "altium-import") (part "root_1_BSMD0603-002-60V_"))
    )
    (comp (ref "F7")
      (value "BSMD0603-025-16V")
      (fields (field (name "BOM_SUPPLIER PART") "C883094") (field (name "CONTRIBUTOR") "LCSC"))
      (libsource (lib "altium-import") (part "root_3_BSMD0603-025-16V_"))
    )
    (comp (ref "F8")
      (value "BSMD0603-025-16V")
      (fields (field (name "BOM_SUPPLIER PART") "C883094") (field (name "CONTRIBUTOR") "LCSC"))
      (libsource (lib "altium-import") (part "root_3_BSMD0603-025-16V_"))
    )
    (comp (ref "F9")
      (value "BSMD0603-025-16V")
      (fields (field (name "BOM_SUPPLIER PART") "C883094") (field (name "CONTRIBUTOR") "LCSC"))
      (libsource (lib "altium-import") (part "root_3_BSMD0603-025-16V_"))
    )
    (comp (ref "F10")
      (value "BSMD0603-025-16V")
      (fields (field (name "BOM_SUPPLIER PART") "C883094") (field (name "CONTRIBUTOR") "LCSC"))
      (libsource (lib "altium-import") (part "root_3_BSMD0603-025-16V_"))
    )
    (comp (ref "F11")
      (value "BSMD0603-002-60V")
      (fields (field (name "BOM_SUPPLIER PART") "C914089") (field (name "CONTRIBUTOR") "LCSC"))
      (libsource (lib "altium-import") (part "root_0_BSMD0603-002-60V_"))
    )
    (comp (ref "F12")
      (value "BSMD0603-002-60V")
      (fields (field (name "BOM_SUPPLIER PART") "C914089") (field (name "CONTRIBUTOR") "LCSC"))
      (libsource (lib "altium-import") (part "root_1_BSMD0603-002-60V_"))
    )
    (comp (ref "F13")
      (value "BSMD0603-025-16V")
      (fields (field (name "BOM_SUPPLIER PART") "C883094") (field (name "CONTRIBUTOR") "LCSC"))
      (libsource (lib "altium-import") (part "root_3_BSMD0603-025-16V_"))
    )
    (comp (ref "F14")
      (value "BSMD0603-025-16V")
      (fields (field (name "BOM_SUPPLIER PART") "C883094") (field (name "CONTRIBUTOR") "LCSC"))
      (libsource (lib "altium-import") (part "root_3_BSMD0603-025-16V_"))
    )
    (comp (ref "F15")
      (value "BSMD0603-025-16V")
      (fields (field (name "BOM_SUPPLIER PART") "C883094") (field (name "CONTRIBUTOR") "LCSC"))
      (libsource (lib "altium-import") (part "root_3_BSMD0603-025-16V_"))
    )
    (comp (ref "F16")
      (value "BSMD0603-025-16V")
      (fields (field (name "BOM_SUPPLIER PART") "C883094") (field (name "CONTRIBUTOR") "LCSC"))
      (libsource (lib "altium-import") (part "root_3_BSMD0603-025-16V_"))
    )
    (comp (ref "F17")
      (value "ASMD2920-075")
      (fields (field (name "BOM_SUPPLIER PART") "C135375") (field (name "CONTRIBUTOR") "LCSC"))
      (libsource (lib "altium-import") (part "root_0_ASMD2920-075_"))
    )
    (comp (ref "F18")
      (value "BSMD0603-002-60V")
      (fields (field (name "BOM_SUPPLIER PART") "C914089") (field (name "CONTRIBUTOR") "LCSC"))
      (libsource (lib "altium-import") (part "root_0_BSMD0603-002-60V_"))
    )
    (comp (ref "F19")
      (value "BSMD0603-002-60V")
      (fields (field (name "BOM_SUPPLIER PART") "C914089") (field (name "CONTRIBUTOR") "LCSC"))
      (libsource (lib "altium-import") (part "root_0_BSMD0603-002-60V_"))
    )
    (comp (ref "F20")
      (value "SMD1812P150TF/24")
      (fields (field (name "BOM_SUPPLIER PART") "C32404"))
      (libsource (lib "altium-import") (part "root_0_SMD1812P150TF/24_"))
    )
    (comp (ref "H1")
      (value "PZ254-1-06-Z-8.5")
      (fields (field (name "BOM_SUPPLIER PART") "C2894929") (field (name "CONTRIBUTOR") "LCSC"))
      (libsource (lib "altium-import") (part "root_0_PZ254-1-06-Z-8.5_"))
    )
    (comp (ref "L1")
      (value "30R")
      (fields
        (field (name "BOM_SUPPLIER PART") "C216133")
        (field (name "BOM_MANUFACTURER PART") "SBM2012G300LSP")
        (field (name "CONTRIBUTOR") "LCSC")
      )
      (libsource (lib "altium-import") (part "root_0_30R_"))
    )
    (comp (ref "L2")
      (value "33uH")
      (fields
        (field (name "BOM_MANUFACTURER PART") "VLU0810-330K")
        (field (name "BOM_SUPPLIER PART") "C72622")
      )
      (libsource (lib "altium-import") (part "root_0_33uH_"))
    )
    (comp (ref "LED1")
      (value "0603White light_C2290")
      (fields (field (name "BOM_MANUFACTURER PART") "KT-0603白灯") (field (name "BOM_SUPPLIER PART") "C2290"))
      (libsource (lib "altium-import") (part "root_3_0603White light_C2290_"))
    )
    (comp (ref "LED2")
      (value "0603White light_C2290")
      (fields (field (name "BOM_MANUFACTURER PART") "KT-0603白灯") (field (name "BOM_SUPPLIER PART") "C2290"))
      (libsource (lib "altium-import") (part "root_3_0603White light_C2290_"))
    )
    (comp (ref "LED3")
      (value "0603White light_C2290")
      (fields (field (name "BOM_MANUFACTURER PART") "KT-0603白灯") (field (name "BOM_SUPPLIER PART") "C2290"))
      (libsource (lib "altium-import") (part "root_3_0603White light_C2290_"))
    )
    (comp (ref "LED4")
      (value "0603White light_C2290")
      (fields (field (name "BOM_MANUFACTURER PART") "KT-0603白灯") (field (name "BOM_SUPPLIER PART") "C2290"))
      (libsource (lib "altium-import") (part "root_3_0603White light_C2290_"))
    )
    (comp (ref "LED5")
      (value "0603White light_C2290")
      (fields (field (name "BOM_MANUFACTURER PART") "KT-0603白灯") (field (name "BOM_SUPPLIER PART") "C2290"))
      (libsource (lib "altium-import") (part "root_3_0603White light_C2290_"))
    )
    (comp (ref "LED6")
      (value "0603White light_C2290")
      (fields (field (name "BOM_MANUFACTURER PART") "KT-0603白灯") (field (name "BOM_SUPPLIER PART") "C2290"))
      (libsource (lib "altium-import") (part "root_3_0603White light_C2290_"))
    )
    (comp (ref "LED7")
      (value "0603White light_C2290")
      (fields (field (name "BOM_MANUFACTURER PART") "KT-0603白灯") (field (name "BOM_SUPPLIER PART") "C2290"))
      (libsource (lib "altium-import") (part "root_3_0603White light_C2290_"))
    )
    (comp (ref "LED8")
      (value "0603White light_C2290")
      (fields (field (name "BOM_MANUFACTURER PART") "KT-0603白灯") (field (name "BOM_SUPPLIER PART") "C2290"))
      (libsource (lib "altium-import") (part "root_3_0603White light_C2290_"))
    )
    (comp (ref "LED9")
      (value "0603White light_C2290")
      (fields (field (name "BOM_MANUFACTURER PART") "KT-0603白灯") (field (name "BOM_SUPPLIER PART") "C2290"))
      (libsource (lib "altium-import") (part "root_3_0603White light_C2290_"))
    )
    (comp (ref "LED10")
      (value "0603White light_C2290")
      (fields (field (name "BOM_MANUFACTURER PART") "KT-0603白灯") (field (name "BOM_SUPPLIER PART") "C2290"))
      (libsource (lib "altium-import") (part "root_2_0603White light_C2290_"))
    )
    (comp (ref "P1")
      (value "WJ127-5.0-3P")
      (fields (field (name "BOM_SUPPLIER PART") "C8393"))
      (libsource (lib "altium-import") (part "root_1_WJ127-5.0-3P_"))
    )
    (comp (ref "P2")
      (value "WJ127-5.0-3P")
      (fields (field (name "BOM_SUPPLIER PART") "C8393"))
      (libsource (lib "altium-import") (part "root_1_WJ127-5.0-3P_"))
    )
    (comp (ref "P3")
      (value "WJ127-5.0-3P")
      (fields (field (name "BOM_SUPPLIER PART") "C8393"))
      (libsource (lib "altium-import") (part "root_1_WJ127-5.0-3P_"))
    )
    (comp (ref "P4")
      (value "WJ127-5.0-3P")
      (fields (field (name "BOM_SUPPLIER PART") "C8393"))
      (libsource (lib "altium-import") (part "root_0_WJ127-5.0-3P_"))
    )
    (comp (ref "P5")
      (value "WJ127-5.0-3P")
      (fields (field (name "BOM_SUPPLIER PART") "C8393"))
      (libsource (lib "altium-import") (part "root_0_WJ127-5.0-3P_"))
    )
    (comp (ref "P6")
      (value "WJ127-5.0-3P")
      (fields (field (name "BOM_SUPPLIER PART") "C8393"))
      (libsource (lib "altium-import") (part "root_0_WJ127-5.0-3P_"))
    )
    (comp (ref "P7")
      (value "WJ127-5.0-3P")
      (fields (field (name "BOM_SUPPLIER PART") "C8393"))
      (libsource (lib "altium-import") (part "root_0_WJ127-5.0-3P_"))
    )
    (comp (ref "P8")
      (value "WJ127-5.0-3P")
      (fields (field (name "BOM_SUPPLIER PART") "C8393"))
      (libsource (lib "altium-import") (part "root_1_WJ127-5.0-3P_"))
    )
    (comp (ref "P9")
      (value "WJ127-5.0-3P")
      (fields (field (name "BOM_SUPPLIER PART") "C8393"))
      (libsource (lib "altium-import") (part "root_0_WJ127-5.0-3P_"))
    )
    (comp (ref "P10")
      (value "WJ127-5.0-3P")
      (fields (field (name "BOM_SUPPLIER PART") "C8393"))
      (libsource (lib "altium-import") (part "root_0_WJ127-5.0-3P_"))
    )
    (comp (ref "P11")
      (value "WJ127-5.0-3P")
      (fields (field (name "BOM_SUPPLIER PART") "C8393"))
      (libsource (lib "altium-import") (part "root_0_WJ127-5.0-3P_"))
    )
    (comp (ref "P12")
      (value "WJ127-5.0-3P")
      (fields (field (name "BOM_SUPPLIER PART") "C8393"))
      (libsource (lib "altium-import") (part "root_0_WJ127-5.0-3P_"))
    )
    (comp (ref "P13")
      (value "WJ127-5.0-2P")
      (fields (field (name "BOM_SUPPLIER PART") "C3703"))
      (libsource (lib "altium-import") (part "root_1_WJ127-5.0-2P_"))
    )
    (comp (ref "P14")
      (value "WJ127-5.0-2P")
      (fields (field (name "BOM_SUPPLIER PART") "C3703"))
      (libsource (lib "altium-import") (part "root_3_WJ127-5.0-2P_"))
    )
    (comp (ref "P15")
      (value "Header-Female-2.54_2x10")
      (fields
        (field (name "BOM_MANUFACTURER PART") "2.54mm,2×10Double row female")
        (field (name "BOM_SUPPLIER PART") "C30867")
      )
      (libsource (lib "altium-import") (part "root_0_Header-Female-2.54_2x10_"))
    )
    (comp (ref "P16")
      (value "WJ127-5.0-2P")
      (fields (field (name "BOM_SUPPLIER PART") "C3703"))
      (libsource (lib "altium-import") (part "root_1_WJ127-5.0-2P_"))
    )
    (comp (ref "Q1")
      (value "AO3400A")
      (fields (field (name "BOM_SUPPLIER PART") "C20917"))
      (libsource (lib "altium-import") (part "root_0_AO3400A_"))
    )
    (comp (ref "Q2")
      (value "AO3400A")
      (fields (field (name "BOM_SUPPLIER PART") "C20917"))
      (libsource (lib "altium-import") (part "root_0_AO3400A_"))
    )
    (comp (ref "Q3")
      (value "AO3400A")
      (fields (field (name "BOM_SUPPLIER PART") "C20917"))
      (libsource (lib "altium-import") (part "root_0_AO3400A_"))
    )
    (comp (ref "Q4")
      (value "AO3400A")
      (fields (field (name "BOM_SUPPLIER PART") "C20917"))
      (libsource (lib "altium-import") (part "root_0_AO3400A_"))
    )
    (comp (ref "Q5")
      (value "2N3904")
      (fields
        (field (name "BOM_MANUFACTURER PART") "MMBT3904")
        (field (name "BOM_SUPPLIER PART") "C20526")
        (field (name "CONTRIBUTOR") "立创EDA官方封装库")
      )
      (libsource (lib "altium-import") (part "root_0_2N3904_"))
    )
    (comp (ref "Q6")
      (value "2N3904")
      (fields
        (field (name "BOM_MANUFACTURER PART") "MMBT3904")
        (field (name "BOM_SUPPLIER PART") "C20526")
        (field (name "CONTRIBUTOR") "立创EDA官方封装库")
      )
      (libsource (lib "altium-import") (part "root_0_2N3904_"))
    )
    (comp (ref "Q7")
      (value "2N3904")
      (fields
        (field (name "BOM_MANUFACTURER PART") "MMBT3904")
        (field (name "BOM_SUPPLIER PART") "C20526")
        (field (name "CONTRIBUTOR") "立创EDA官方封装库")
      )
      (libsource (lib "altium-import") (part "root_0_2N3904_"))
    )
    (comp (ref "Q8")
      (value "2N3904")
      (fields
        (field (name "BOM_MANUFACTURER PART") "MMBT3904")
        (field (name "BOM_SUPPLIER PART") "C20526")
        (field (name "CONTRIBUTOR") "立创EDA官方封装库")
      )
      (libsource (lib "altium-import") (part "root_0_2N3904_"))
    )
    (comp (ref "Q9")
      (value "AO3400A")
      (fields (field (name "BOM_SUPPLIER PART") "C20917"))
      (libsource (lib "altium-import") (part "root_0_AO3400A_"))
    )
    (comp (ref "Q10")
      (value "AO3400A")
      (fields (field (name "BOM_SUPPLIER PART") "C20917"))
      (libsource (lib "altium-import") (part "root_0_AO3400A_"))
    )
    (comp (ref "Q11")
      (value "AO3400A")
      (fields (field (name "BOM_SUPPLIER PART") "C20917"))
      (libsource (lib "altium-import") (part "root_0_AO3400A_"))
    )
    (comp (ref "Q12")
      (value "AO3400A")
      (fields (field (name "BOM_SUPPLIER PART") "C20917"))
      (libsource (lib "altium-import") (part "root_0_AO3400A_"))
    )
    (comp (ref "Q13")
      (value "2N3904")
      (fields
        (field (name "BOM_MANUFACTURER PART") "MMBT3904")
        (field (name "BOM_SUPPLIER PART") "C20526")
        (field (name "CONTRIBUTOR") "立创EDA官方封装库")
      )
      (libsource (lib "altium-import") (part "root_0_2N3904_"))
    )
    (comp (ref "Q14")
      (value "2N3904")
      (fields
        (field (name "BOM_MANUFACTURER PART") "MMBT3904")
        (field (name "BOM_SUPPLIER PART") "C20526")
        (field (name "CONTRIBUTOR") "立创EDA官方封装库")
      )
      (libsource (lib "altium-import") (part "root_0_2N3904_"))
    )
    (comp (ref "Q15")
      (value "2N3904")
      (fields
        (field (name "BOM_MANUFACTURER PART") "MMBT3904")
        (field (name "BOM_SUPPLIER PART") "C20526")
        (field (name "CONTRIBUTOR") "立创EDA官方封装库")
      )
      (libsource (lib "altium-import") (part "root_0_2N3904_"))
    )
    (comp (ref "Q16")
      (value "2N3904")
      (fields
        (field (name "BOM_MANUFACTURER PART") "MMBT3904")
        (field (name "BOM_SUPPLIER PART") "C20526")
        (field (name "CONTRIBUTOR") "立创EDA官方封装库")
      )
      (libsource (lib "altium-import") (part "root_0_2N3904_"))
    )
    (comp (ref "Q17")
      (value "MMBT2222A_C8512")
      (fields (field (name "BOM_MANUFACTURER PART") "MMBT2222A") (field (name "BOM_SUPPLIER PART") "C8512"))
      (libsource (lib "altium-import") (part "root_0_MMBT2222A_C8512_"))
    )
    (comp (ref "Q18")
      (value "MMBT2222A_C8512")
      (fields (field (name "BOM_MANUFACTURER PART") "MMBT2222A") (field (name "BOM_SUPPLIER PART") "C8512"))
      (libsource (lib "") (part "root_0_MMBT2222A_C8512__1"))
    )
    (comp (ref "Q19")
      (value "2N7002")
      (fields (field (name "BOM_SUPPLIER PART") "C8545"))
      (libsource (lib "altium-import") (part "root_0_2N7002_"))
    )
    (comp (ref "R1")
      (value "100K")
      (fields
        (field (name "BOM_MANUFACTURER PART") "0402WGF1003TCE")
        (field (name "BOM_SUPPLIER PART") "C25741")
      )
      (libsource (lib "altium-import") (part "root_3_100K_"))
    )
    (comp (ref "R2")
      (value "4.7K")
      (fields
        (field (name "BOM_MANUFACTURER PART") "0402WGF4701TCE")
        (field (name "BOM_SUPPLIER PART") "C25900")
      )
      (libsource (lib "altium-import") (part "root_3_4.7K_"))
    )
    (comp (ref "R3")
      (value "10")
      (fields
        (field (name "BOM_MANUFACTURER PART") "0402WGF100JTCE")
        (field (name "BOM_SUPPLIER PART") "C25077")
      )
      (libsource (lib "altium-import") (part "root_3_10_"))
    )
    (comp (ref "R4")
      (value "1.5K")
      (fields
        (field (name "BOM_MANUFACTURER PART") "0402WGF1501TCE")
        (field (name "BOM_SUPPLIER PART") "C25867")
      )
      (libsource (lib "altium-import") (part "root_3_1.5K_"))
    )
    (comp (ref "R5")
      (value "49.9")
      (fields
        (field (name "BOM_MANUFACTURER PART") "0402WGF499JTCE")
        (field (name "BOM_SUPPLIER PART") "C25120")
      )
      (libsource (lib "altium-import") (part "root_3_49.9_"))
    )
    (comp (ref "R6")
      (value "49.9")
      (fields
        (field (name "BOM_MANUFACTURER PART") "0402WGF499JTCE")
        (field (name "BOM_SUPPLIER PART") "C25120")
      )
      (libsource (lib "altium-import") (part "root_3_49.9_"))
    )
    (comp (ref "R7")
      (value "49.9")
      (fields
        (field (name "BOM_MANUFACTURER PART") "0402WGF499JTCE")
        (field (name "BOM_SUPPLIER PART") "C25120")
      )
      (libsource (lib "altium-import") (part "root_3_49.9_"))
    )
    (comp (ref "R8")
      (value "49.9")
      (fields
        (field (name "BOM_MANUFACTURER PART") "0402WGF499JTCE")
        (field (name "BOM_SUPPLIER PART") "C25120")
      )
      (libsource (lib "altium-import") (part "root_3_49.9_"))
    )
    (comp (ref "R9")
      (value "100K")
      (fields
        (field (name "BOM_MANUFACTURER PART") "0402WGF1003TCE")
        (field (name "BOM_SUPPLIER PART") "C25741")
      )
      (libsource (lib "altium-import") (part "root_3_100K_"))
    )
    (comp (ref "R10")
      (value "330")
      (fields
        (field (name "BOM_MANUFACTURER PART") "0402WGF3300TCE")
        (field (name "BOM_SUPPLIER PART") "C25104")
      )
      (libsource (lib "altium-import") (part "root_0_330_"))
    )
    (comp (ref "R11")
      (value "12.1K")
      (fields
        (field (name "BOM_MANUFACTURER PART") "0402WGF1212TCE")
        (field (name "BOM_SUPPLIER PART") "C25852")
      )
      (libsource (lib "altium-import") (part "root_0_12.1K_"))
    )
    (comp (ref "R12")
      (value "10")
      (fields
        (field (name "BOM_MANUFACTURER PART") "0402WGF100JTCE")
        (field (name "BOM_SUPPLIER PART") "C25077")
      )
      (libsource (lib "altium-import") (part "root_0_10_"))
    )
    (comp (ref "R13")
      (value "330")
      (fields
        (field (name "BOM_MANUFACTURER PART") "0402WGF3300TCE")
        (field (name "BOM_SUPPLIER PART") "C25104")
      )
      (libsource (lib "altium-import") (part "root_0_330_"))
    )
    (comp (ref "R14")
      (value "10")
      (fields
        (field (name "BOM_MANUFACTURER PART") "0402WGF100JTCE")
        (field (name "BOM_SUPPLIER PART") "C25077")
      )
      (libsource (lib "altium-import") (part "root_0_10_"))
    )
    (comp (ref "R15")
      (value "10")
      (fields
        (field (name "BOM_MANUFACTURER PART") "0402WGF100JTCE")
        (field (name "BOM_SUPPLIER PART") "C25077")
      )
      (libsource (lib "altium-import") (part "root_0_10_"))
    )
    (comp (ref "R16")
      (value "100K")
      (fields
        (field (name "BOM_MANUFACTURER PART") "0402WGF1003TCE")
        (field (name "BOM_SUPPLIER PART") "C25741")
      )
      (libsource (lib "altium-import") (part "root_3_100K_"))
    )
    (comp (ref "R17")
      (value "470")
      (fields
        (field (name "BOM_MANUFACTURER PART") "0402WGF4700TCE")
        (field (name "BOM_SUPPLIER PART") "C25117")
      )
      (libsource (lib "altium-import") (part "root_0_470_"))
    )
    (comp (ref "R18")
      (value "10K")
      (fields
        (field (name "BOM_MANUFACTURER PART") "0402WGF1002TCE")
        (field (name "BOM_SUPPLIER PART") "C25744")
      )
      (libsource (lib "altium-import") (part "root_3_10K_"))
    )
    (comp (ref "R19")
      (value "100K")
      (fields
        (field (name "BOM_MANUFACTURER PART") "0402WGF1003TCE")
        (field (name "BOM_SUPPLIER PART") "C25741")
      )
      (libsource (lib "altium-import") (part "root_3_100K_"))
    )
    (comp (ref "R20")
      (value "100K")
      (fields
        (field (name "BOM_MANUFACTURER PART") "0402WGF1003TCE")
        (field (name "BOM_SUPPLIER PART") "C25741")
      )
      (libsource (lib "altium-import") (part "root_3_100K_"))
    )
    (comp (ref "R21")
      (value "100K")
      (fields
        (field (name "BOM_MANUFACTURER PART") "0402WGF1003TCE")
        (field (name "BOM_SUPPLIER PART") "C25741")
      )
      (libsource (lib "altium-import") (part "root_3_100K_"))
    )
    (comp (ref "R22")
      (value "2.2kΩ")
      (fields
        (field (name "BOM_MANUFACTURER PART") "0603WAF2201T5E")
        (field (name "BOM_SUPPLIER PART") "C4190")
      )
      (libsource (lib "altium-import") (part "root_3_2.2kΩ_"))
    )
    (comp (ref "R23")
      (value "2.2kΩ")
      (fields
        (field (name "BOM_MANUFACTURER PART") "0603WAF2201T5E")
        (field (name "BOM_SUPPLIER PART") "C4190")
      )
      (libsource (lib "altium-import") (part "root_3_2.2kΩ_"))
    )
    (comp (ref "R24")
      (value "2.2kΩ")
      (fields
        (field (name "BOM_MANUFACTURER PART") "0603WAF2201T5E")
        (field (name "BOM_SUPPLIER PART") "C4190")
      )
      (libsource (lib "altium-import") (part "root_3_2.2kΩ_"))
    )
    (comp (ref "R25")
      (value "2.2kΩ")
      (fields
        (field (name "BOM_MANUFACTURER PART") "0603WAF2201T5E")
        (field (name "BOM_SUPPLIER PART") "C4190")
      )
      (libsource (lib "altium-import") (part "root_3_2.2kΩ_"))
    )
    (comp (ref "R26")
      (value "2.2kΩ")
      (fields
        (field (name "BOM_MANUFACTURER PART") "0402WGF2201TCE")
        (field (name "BOM_SUPPLIER PART") "C25879")
      )
      (libsource (lib "altium-import") (part "root_3_2.2kΩ_"))
    )
    (comp (ref "R27")
      (value "4.7K")
      (fields
        (field (name "BOM_MANUFACTURER PART") "0402WGF4701TCE")
        (field (name "BOM_SUPPLIER PART") "C25900")
      )
      (libsource (lib "altium-import") (part "root_3_4.7K_"))
    )
    (comp (ref "R28")
      (value "2.2kΩ")
      (fields
        (field (name "BOM_MANUFACTURER PART") "0402WGF2201TCE")
        (field (name "BOM_SUPPLIER PART") "C25879")
      )
      (libsource (lib "altium-import") (part "root_3_2.2kΩ_"))
    )
    (comp (ref "R29")
      (value "4.7K")
      (fields
        (field (name "BOM_MANUFACTURER PART") "0402WGF4701TCE")
        (field (name "BOM_SUPPLIER PART") "C25900")
      )
      (libsource (lib "altium-import") (part "root_3_4.7K_"))
    )
    (comp (ref "R30")
      (value "2.2kΩ")
      (fields
        (field (name "BOM_MANUFACTURER PART") "0402WGF2201TCE")
        (field (name "BOM_SUPPLIER PART") "C25879")
      )
      (libsource (lib "altium-import") (part "root_3_2.2kΩ_"))
    )
    (comp (ref "R31")
      (value "4.7K")
      (fields
        (field (name "BOM_MANUFACTURER PART") "0402WGF4701TCE")
        (field (name "BOM_SUPPLIER PART") "C25900")
      )
      (libsource (lib "altium-import") (part "root_3_4.7K_"))
    )
    (comp (ref "R32")
      (value "2.2kΩ")
      (fields
        (field (name "BOM_MANUFACTURER PART") "0402WGF2201TCE")
        (field (name "BOM_SUPPLIER PART") "C25879")
      )
      (libsource (lib "altium-import") (part "root_3_2.2kΩ_"))
    )
    (comp (ref "R33")
      (value "4.7K")
      (fields
        (field (name "BOM_MANUFACTURER PART") "0402WGF4701TCE")
        (field (name "BOM_SUPPLIER PART") "C25900")
      )
      (libsource (lib "altium-import") (part "root_3_4.7K_"))
    )
    (comp (ref "R34")
      (value "100K")
      (fields
        (field (name "BOM_MANUFACTURER PART") "0402WGF1003TCE")
        (field (name "BOM_SUPPLIER PART") "C25741")
      )
      (libsource (lib "altium-import") (part "root_3_100K_"))
    )
    (comp (ref "R35")
      (value "510Ω")
      (fields
        (field (name "BOM_MANUFACTURER PART") "0402WGF5100TCE")
        (field (name "BOM_SUPPLIER PART") "C25123")
      )
      (libsource (lib "altium-import") (part "root_2_510Ω_"))
    )
    (comp (ref "R36")
      (value "510Ω")
      (fields
        (field (name "BOM_MANUFACTURER PART") "0402WGF5100TCE")
        (field (name "BOM_SUPPLIER PART") "C25123")
      )
      (libsource (lib "altium-import") (part "root_2_510Ω_"))
    )
    (comp (ref "R37")
      (value "510Ω")
      (fields
        (field (name "BOM_MANUFACTURER PART") "0402WGF5100TCE")
        (field (name "BOM_SUPPLIER PART") "C25123")
      )
      (libsource (lib "altium-import") (part "root_2_510Ω_"))
    )
    (comp (ref "R38")
      (value "510Ω")
      (fields
        (field (name "BOM_MANUFACTURER PART") "0402WGF5100TCE")
        (field (name "BOM_SUPPLIER PART") "C25123")
      )
      (libsource (lib "altium-import") (part "root_2_510Ω_"))
    )
    (comp (ref "R39")
      (value "100K")
      (fields
        (field (name "BOM_MANUFACTURER PART") "0402WGF1003TCE")
        (field (name "BOM_SUPPLIER PART") "C25741")
      )
      (libsource (lib "altium-import") (part "root_3_100K_"))
    )
    (comp (ref "R40")
      (value "100K")
      (fields
        (field (name "BOM_MANUFACTURER PART") "0402WGF1003TCE")
        (field (name "BOM_SUPPLIER PART") "C25741")
      )
      (libsource (lib "altium-import") (part "root_3_100K_"))
    )
    (comp (ref "R41")
      (value "100K")
      (fields
        (field (name "BOM_MANUFACTURER PART") "0402WGF1003TCE")
        (field (name "BOM_SUPPLIER PART") "C25741")
      )
      (libsource (lib "altium-import") (part "root_3_100K_"))
    )
    (comp (ref "R42")
      (value "100K")
      (fields
        (field (name "BOM_MANUFACTURER PART") "0402WGF1003TCE")
        (field (name "BOM_SUPPLIER PART") "C25741")
      )
      (libsource (lib "altium-import") (part "root_3_100K_"))
    )
    (comp (ref "R43")
      (value "100K")
      (fields
        (field (name "BOM_MANUFACTURER PART") "0402WGF1003TCE")
        (field (name "BOM_SUPPLIER PART") "C25741")
      )
      (libsource (lib "altium-import") (part "root_3_100K_"))
    )
    (comp (ref "R44")
      (value "2.2kΩ")
      (fields
        (field (name "BOM_MANUFACTURER PART") "0603WAF2201T5E")
        (field (name "BOM_SUPPLIER PART") "C4190")
      )
      (libsource (lib "altium-import") (part "root_3_2.2kΩ_"))
    )
    (comp (ref "R45")
      (value "2.2kΩ")
      (fields
        (field (name "BOM_MANUFACTURER PART") "0603WAF2201T5E")
        (field (name "BOM_SUPPLIER PART") "C4190")
      )
      (libsource (lib "altium-import") (part "root_3_2.2kΩ_"))
    )
    (comp (ref "R46")
      (value "2.2kΩ")
      (fields
        (field (name "BOM_MANUFACTURER PART") "0603WAF2201T5E")
        (field (name "BOM_SUPPLIER PART") "C4190")
      )
      (libsource (lib "altium-import") (part "root_3_2.2kΩ_"))
    )
    (comp (ref "R47")
      (value "2.2kΩ")
      (fields
        (field (name "BOM_MANUFACTURER PART") "0603WAF2201T5E")
        (field (name "BOM_SUPPLIER PART") "C4190")
      )
      (libsource (lib "altium-import") (part "root_3_2.2kΩ_"))
    )
    (comp (ref "R48")
      (value "2.2kΩ")
      (fields
        (field (name "BOM_MANUFACTURER PART") "0402WGF2201TCE")
        (field (name "BOM_SUPPLIER PART") "C25879")
      )
      (libsource (lib "altium-import") (part "root_3_2.2kΩ_"))
    )
    (comp (ref "R49")
      (value "4.7K")
      (fields
        (field (name "BOM_MANUFACTURER PART") "0402WGF4701TCE")
        (field (name "BOM_SUPPLIER PART") "C25900")
      )
      (libsource (lib "altium-import") (part "root_3_4.7K_"))
    )
    (comp (ref "R50")
      (value "2.2kΩ")
      (fields
        (field (name "BOM_MANUFACTURER PART") "0402WGF2201TCE")
        (field (name "BOM_SUPPLIER PART") "C25879")
      )
      (libsource (lib "altium-import") (part "root_3_2.2kΩ_"))
    )
    (comp (ref "R51")
      (value "4.7K")
      (fields
        (field (name "BOM_MANUFACTURER PART") "0402WGF4701TCE")
        (field (name "BOM_SUPPLIER PART") "C25900")
      )
      (libsource (lib "altium-import") (part "root_3_4.7K_"))
    )
    (comp (ref "R52")
      (value "2.2kΩ")
      (fields
        (field (name "BOM_MANUFACTURER PART") "0402WGF2201TCE")
        (field (name "BOM_SUPPLIER PART") "C25879")
      )
      (libsource (lib "altium-import") (part "root_3_2.2kΩ_"))
    )
    (comp (ref "R53")
      (value "4.7K")
      (fields
        (field (name "BOM_MANUFACTURER PART") "0402WGF4701TCE")
        (field (name "BOM_SUPPLIER PART") "C25900")
      )
      (libsource (lib "altium-import") (part "root_3_4.7K_"))
    )
    (comp (ref "R54")
      (value "2.2kΩ")
      (fields
        (field (name "BOM_MANUFACTURER PART") "0402WGF2201TCE")
        (field (name "BOM_SUPPLIER PART") "C25879")
      )
      (libsource (lib "altium-import") (part "root_3_2.2kΩ_"))
    )
    (comp (ref "R55")
      (value "4.7K")
      (fields
        (field (name "BOM_MANUFACTURER PART") "0402WGF4701TCE")
        (field (name "BOM_SUPPLIER PART") "C25900")
      )
      (libsource (lib "altium-import") (part "root_3_4.7K_"))
    )
    (comp (ref "R56")
      (value "510Ω")
      (fields
        (field (name "BOM_MANUFACTURER PART") "0402WGF5100TCE")
        (field (name "BOM_SUPPLIER PART") "C25123")
      )
      (libsource (lib "altium-import") (part "root_2_510Ω_"))
    )
    (comp (ref "R57")
      (value "510Ω")
      (fields
        (field (name "BOM_MANUFACTURER PART") "0402WGF5100TCE")
        (field (name "BOM_SUPPLIER PART") "C25123")
      )
      (libsource (lib "altium-import") (part "root_2_510Ω_"))
    )
    (comp (ref "R58")
      (value "510Ω")
      (fields
        (field (name "BOM_MANUFACTURER PART") "0402WGF5100TCE")
        (field (name "BOM_SUPPLIER PART") "C25123")
      )
      (libsource (lib "altium-import") (part "root_2_510Ω_"))
    )
    (comp (ref "R59")
      (value "100K")
      (fields
        (field (name "BOM_MANUFACTURER PART") "0402WGF1003TCE")
        (field (name "BOM_SUPPLIER PART") "C25741")
      )
      (libsource (lib "altium-import") (part "root_3_100K_"))
    )
    (comp (ref "R60")
      (value "510Ω")
      (fields
        (field (name "BOM_MANUFACTURER PART") "0402WGF5100TCE")
        (field (name "BOM_SUPPLIER PART") "C25123")
      )
      (libsource (lib "altium-import") (part "root_2_510Ω_"))
    )
    (comp (ref "R61")
      (value "100K")
      (fields
        (field (name "BOM_MANUFACTURER PART") "0402WGF1003TCE")
        (field (name "BOM_SUPPLIER PART") "C25741")
      )
      (libsource (lib "altium-import") (part "root_3_100K_"))
    )
    (comp (ref "R62")
      (value "100K")
      (fields
        (field (name "BOM_MANUFACTURER PART") "0402WGF1003TCE")
        (field (name "BOM_SUPPLIER PART") "C25741")
      )
      (libsource (lib "altium-import") (part "root_3_100K_"))
    )
    (comp (ref "R63")
      (value "100K")
      (fields
        (field (name "BOM_MANUFACTURER PART") "0402WGF1003TCE")
        (field (name "BOM_SUPPLIER PART") "C25741")
      )
      (libsource (lib "altium-import") (part "root_3_100K_"))
    )
    (comp (ref "R64")
      (value "4.7K")
      (fields
        (field (name "BOM_MANUFACTURER PART") "0402WGF4701TCE")
        (field (name "BOM_SUPPLIER PART") "C25900")
      )
      (libsource (lib "altium-import") (part "root_3_4.7K_"))
    )
    (comp (ref "R65")
      (value "4.7K")
      (fields
        (field (name "BOM_MANUFACTURER PART") "0402WGF4701TCE")
        (field (name "BOM_SUPPLIER PART") "C25900")
      )
      (libsource (lib "altium-import") (part "root_3_4.7K_"))
    )
    (comp (ref "R66")
      (value "4.7K")
      (fields
        (field (name "BOM_MANUFACTURER PART") "0402WGF4701TCE")
        (field (name "BOM_SUPPLIER PART") "C25900")
      )
      (libsource (lib "altium-import") (part "root_3_4.7K_"))
    )
    (comp (ref "R67")
      (value "470")
      (fields
        (field (name "BOM_MANUFACTURER PART") "0402WGF4700TCE")
        (field (name "BOM_SUPPLIER PART") "C25117")
      )
      (libsource (lib "altium-import") (part "root_0_470_"))
    )
    (comp (ref "R68")
      (value "10K")
      (fields
        (field (name "BOM_MANUFACTURER PART") "0402WGF1002TCE")
        (field (name "BOM_SUPPLIER PART") "C25744")
      )
      (libsource (lib "altium-import") (part "root_2_10K_"))
    )
    (comp (ref "R69")
      (value "680Ω")
      (fields
        (field (name "BOM_MANUFACTURER PART") "0402WGF6800TCE")
        (field (name "BOM_SUPPLIER PART") "C25130")
      )
      (libsource (lib "altium-import") (part "root_0_680Ω_"))
    )
    (comp (ref "R70")
      (value "680Ω")
      (fields
        (field (name "BOM_MANUFACTURER PART") "0402WGF6800TCE")
        (field (name "BOM_SUPPLIER PART") "C25130")
      )
      (libsource (lib "altium-import") (part "root_0_680Ω_"))
    )
    (comp (ref "R71")
      (value "10K")
      (fields
        (field (name "BOM_MANUFACTURER PART") "0402WGF1002TCE")
        (field (name "BOM_SUPPLIER PART") "C25744")
      )
      (libsource (lib "altium-import") (part "root_2_10K_"))
    )
    (comp (ref "R72")
      (value "5.1K")
      (fields
        (field (name "BOM_MANUFACTURER PART") "RC0402FR-075K1L")
        (field (name "BOM_SUPPLIER PART") "C105872")
      )
      (libsource (lib "altium-import") (part "root_3_5.1K_"))
    )
    (comp (ref "R73")
      (value "5.1K")
      (fields
        (field (name "BOM_MANUFACTURER PART") "RC0402FR-075K1L")
        (field (name "BOM_SUPPLIER PART") "C105872")
      )
      (libsource (lib "altium-import") (part "root_3_5.1K_"))
    )
    (comp (ref "R74")
      (value "470")
      (fields
        (field (name "BOM_MANUFACTURER PART") "0402WGF4700TCE")
        (field (name "BOM_SUPPLIER PART") "C25117")
      )
      (libsource (lib "altium-import") (part "root_0_470_"))
    )
    (comp (ref "R75")
      (value "4.7K")
      (fields
        (field (name "BOM_MANUFACTURER PART") "0402WGF4701TCE")
        (field (name "BOM_SUPPLIER PART") "C25900")
      )
      (libsource (lib "altium-import") (part "root_3_4.7K_"))
    )
    (comp (ref "R76")
      (value "4.7K")
      (fields
        (field (name "BOM_MANUFACTURER PART") "0402WGF4701TCE")
        (field (name "BOM_SUPPLIER PART") "C25900")
      )
      (libsource (lib "altium-import") (part "root_3_4.7K_"))
    )
    (comp (ref "R77")
      (value "470")
      (fields
        (field (name "BOM_MANUFACTURER PART") "0402WGF4700TCE")
        (field (name "BOM_SUPPLIER PART") "C25117")
      )
      (libsource (lib "altium-import") (part "root_0_470_"))
    )
    (comp (ref "R78")
      (value "24kΩ")
      (fields
        (field (name "BOM_MANUFACTURER PART") "0402WGF2402TCE")
        (field (name "BOM_SUPPLIER PART") "C25769")
      )
      (libsource (lib "altium-import") (part "root_0_24kΩ_"))
    )
    (comp (ref "R79")
      (value "49.9kΩ")
      (fields
        (field (name "BOM_MANUFACTURER PART") "0402WGF4992TCE")
        (field (name "BOM_SUPPLIER PART") "C25897")
      )
      (libsource (lib "altium-import") (part "root_3_49.9kΩ_"))
    )
    (comp (ref "R80")
      (value "2kΩ")
      (fields
        (field (name "BOM_MANUFACTURER PART") "0402WGF2001TCE")
        (field (name "BOM_SUPPLIER PART") "C4109")
      )
      (libsource (lib "altium-import") (part "root_3_2kΩ_"))
    )
    (comp (ref "R81")
      (value "12.1K")
      (fields
        (field (name "BOM_MANUFACTURER PART") "0402WGF1212TCE")
        (field (name "BOM_SUPPLIER PART") "C25852")
      )
      (libsource (lib "altium-import") (part "root_3_12.1K_"))
    )
    (comp (ref "R82")
      (value "12.1K")
      (fields
        (field (name "BOM_MANUFACTURER PART") "0402WGF1212TCE")
        (field (name "BOM_SUPPLIER PART") "C25852")
      )
      (libsource (lib "altium-import") (part "root_3_12.1K_"))
    )
    (comp (ref "R83")
      (value "470")
      (fields
        (field (name "BOM_MANUFACTURER PART") "0402WGF4700TCE")
        (field (name "BOM_SUPPLIER PART") "C25117")
      )
      (libsource (lib "altium-import") (part "root_0_470_"))
    )
    (comp (ref "R84")
      (value "10K")
      (fields
        (field (name "BOM_MANUFACTURER PART") "0402WGF1002TCE")
        (field (name "BOM_SUPPLIER PART") "C25744")
      )
      (libsource (lib "altium-import") (part "root_2_10K_"))
    )
    (comp (ref "R85")
      (value "510Ω")
      (fields
        (field (name "BOM_MANUFACTURER PART") "0402WGF5100TCE")
        (field (name "BOM_SUPPLIER PART") "C25123")
      )
      (libsource (lib "altium-import") (part "root_3_510Ω_"))
    )
    (comp (ref "R86")
      (value "2.2kΩ")
      (fields
        (field (name "BOM_MANUFACTURER PART") "0603WAF2201T5E")
        (field (name "BOM_SUPPLIER PART") "C4190")
      )
      (libsource (lib "altium-import") (part "root_2_2.2kΩ_"))
    )
    (comp (ref "R87")
      (value "2.2kΩ")
      (fields
        (field (name "BOM_MANUFACTURER PART") "0603WAF2201T5E")
        (field (name "BOM_SUPPLIER PART") "C4190")
      )
      (libsource (lib "altium-import") (part "root_3_2.2kΩ_"))
    )
    (comp (ref "RELAY1")
      (value "SRD-12VDC-SL-C")
      (fields (field (name "BOM_SUPPLIER PART") "C30431"))
      (libsource (lib "altium-import") (part "root_3_SRD-12VDC-SL-C_"))
    )
    (comp (ref "RELAY2")
      (value "SRD-12VDC-SL-C")
      (fields (field (name "BOM_SUPPLIER PART") "C30431"))
      (libsource (lib "altium-import") (part "root_3_SRD-12VDC-SL-C_"))
    )
    (comp (ref "RELAY3")
      (value "SRD-12VDC-SL-C")
      (fields (field (name "BOM_SUPPLIER PART") "C30431"))
      (libsource (lib "altium-import") (part "root_3_SRD-12VDC-SL-C_"))
    )
    (comp (ref "RELAY4")
      (value "SRD-12VDC-SL-C")
      (fields (field (name "BOM_SUPPLIER PART") "C30431"))
      (libsource (lib "altium-import") (part "root_3_SRD-12VDC-SL-C_"))
    )
    (comp (ref "RELAY5")
      (value "SRD-12VDC-SL-C")
      (fields (field (name "BOM_SUPPLIER PART") "C30431"))
      (libsource (lib "altium-import") (part "root_3_SRD-12VDC-SL-C_"))
    )
    (comp (ref "RELAY6")
      (value "SRD-12VDC-SL-C")
      (fields (field (name "BOM_SUPPLIER PART") "C30431"))
      (libsource (lib "altium-import") (part "root_3_SRD-12VDC-SL-C_"))
    )
    (comp (ref "RELAY7")
      (value "SRD-12VDC-SL-C")
      (fields (field (name "BOM_SUPPLIER PART") "C30431"))
      (libsource (lib "altium-import") (part "root_3_SRD-12VDC-SL-C_"))
    )
    (comp (ref "RELAY8")
      (value "SRD-12VDC-SL-C")
      (fields (field (name "BOM_SUPPLIER PART") "C30431"))
      (libsource (lib "altium-import") (part "root_3_SRD-12VDC-SL-C_"))
    )
    (comp (ref "RF1")
      (value "SMA")
      (fields
        (field (name "BOM_SUPPLIER PART") "C1509215")
        (field (name "BOM_MANUFACTURER PART") "HJ-SMA200")
        (field (name "CONTRIBUTOR") "LCSC")
      )
      (libsource (lib "altium-import") (part "root_0_SMA_"))
    )
    (comp (ref "RJ1")
      (value "HY931147C")
      (fields (field (name "BOM_SUPPLIER PART") "C91754"))
      (libsource (lib "altium-import") (part "root_0_HY931147C_"))
    )
    (comp (ref "RN1")
      (value "33")
      (fields
        (field (name "BOM_MANUFACTURER PART") "4D02WGJ0330TCE")
        (field (name "BOM_SUPPLIER PART") "C25501")
      )
      (libsource (lib "altium-import") (part "root_0_33_"))
    )
    (comp (ref "U1")
      (value "BPI7402")
      (fields (field (name "CONTRIBUTOR") "dirtypolecat"))
      (libsource (lib "altium-import") (part "root_0_BPI7402_"))
    )
    (comp (ref "U2")
      (value "LAN8720AI-CP-TR")
      (fields (field (name "BOM_SUPPLIER PART") "C17146"))
      (libsource (lib "altium-import") (part "root_0_LAN8720AI-CP-TR_"))
    )
    (comp (ref "U3")
      (value "PCF8574T/3,518")
      (fields (field (name "BOM_SUPPLIER PART") "C7605"))
      (libsource (lib "altium-import") (part "root_0_PCF8574T/3,518_"))
    )
    (comp (ref "U4")
      (value "PCF8574T/3,518")
      (fields (field (name "BOM_SUPPLIER PART") "C7605"))
      (libsource (lib "altium-import") (part "root_0_PCF8574T/3,518_"))
    )
    (comp (ref "U5")
      (value "78L05G-AB3-R")
      (fields (field (name "BOM_SUPPLIER PART") "C71136"))
      (libsource (lib "altium-import") (part "root_0_78L05G-AB3-R_"))
    )
    (comp (ref "U6")
      (value "CP2102-GMR")
      (fields (field (name "BOM_SUPPLIER PART") "C6568"))
      (libsource (lib "altium-import") (part "root_0_CP2102-GMR_"))
    )
    (comp (ref "U7")
      (value "DS1307ZN+")
      (fields (field (name "BOM_SUPPLIER PART") "C26858"))
      (libsource (lib "altium-import") (part "root_0_DS1307ZN+_"))
    )
    (comp (ref "U8")
      (value "ESP32-WROOM-32U-N16")
      (fields (field (name "BOM_SUPPLIER PART") "C529580") (field (name "CONTRIBUTOR") "LCSC"))
      (libsource (lib "altium-import") (part "root_1_ESP32-WROOM-32U-N16_"))
    )
    (comp (ref "U9")
      (value "LM2596S-3.3")
      (fields (field (name "BOM_SUPPLIER PART") "C347420") (field (name "CONTRIBUTOR") "LCSC"))
      (libsource (lib "altium-import") (part "root_0_LM2596S-3.3_"))
    )
    (comp (ref "USB1")
      (value "KH-TYPE-C-16P")
      (fields (field (name "BOM_SUPPLIER PART") "C709357") (field (name "CONTRIBUTOR") "LCSC"))
      (libsource (lib "altium-import") (part "root_0_KH-TYPE-C-16P_"))
    )
    (comp (ref "X1")
      (value "50MHz")
      (fields
        (field (name "BOM_SUPPLIER PART") "C669094")
        (field (name "BOM_MANUFACTURER PART") "OT705050MJBA4SL")
        (field (name "CONTRIBUTOR") "LCSC")
      )
      (libsource (lib "altium-import") (part "root_0_50MHz_"))
    )
    (comp (ref "X2")
      (value "32.768KHz")
      (fields (field (name "BOM_SUPPLIER PART") "C145164") (field (name "CONTRIBUTOR") "LCSC"))
      (libsource (lib "altium-import") (part "root_2_32.768KHz_"))
    )
  )
  (nets
    (net (code "1") (name "/3V3") (class "Default")
      (node (ref "C1") (pin "1") (pinfunction "1_1") (pintype "passive"))
      (node (ref "C15") (pin "1") (pinfunction "1_1") (pintype "passive"))
      (node (ref "C17") (pin "1") (pinfunction "1_1") (pintype "passive"))
      (node (ref "C2") (pin "1") (pinfunction "1_1") (pintype "passive"))
      (node (ref "C23") (pin "1") (pinfunction "1_1") (pintype "passive"))
      (node (ref "C29") (pin "2") (pinfunction "2_2") (pintype "passive"))
      (node (ref "C3") (pin "1") (pinfunction "1_1") (pintype "passive"))
      (node (ref "C30") (pin "1") (pinfunction "1_1") (pintype "passive"))
      (node (ref "C31") (pin "1") (pinfunction "1_1") (pintype "passive"))
      (node (ref "C32") (pin "1") (pinfunction "1_1") (pintype "passive"))
      (node (ref "C37") (pin "1") (pinfunction "1_1") (pintype "passive"))
      (node (ref "C4") (pin "1") (pinfunction "1_1") (pintype "passive"))
      (node (ref "L1") (pin "1") (pinfunction "1_1") (pintype "passive"))
      (node (ref "L2") (pin "2") (pinfunction "2_2") (pintype "passive"))
      (node (ref "P15") (pin "13") (pinfunction "13_13") (pintype "passive"))
      (node (ref "R1") (pin "1") (pinfunction "1_1") (pintype "passive"))
      (node (ref "R16") (pin "1") (pinfunction "1_1") (pintype "passive"))
      (node (ref "R19") (pin "1") (pinfunction "1_1") (pintype "passive"))
      (node (ref "R2") (pin "1") (pinfunction "1_1") (pintype "passive"))
      (node (ref "R20") (pin "1") (pinfunction "1_1") (pintype "passive"))
      (node (ref "R21") (pin "1") (pinfunction "1_1") (pintype "passive"))
      (node (ref "R26") (pin "1") (pinfunction "1_1") (pintype "passive"))
      (node (ref "R27") (pin "1") (pinfunction "1_1") (pintype "passive"))
      (node (ref "R28") (pin "1") (pinfunction "1_1") (pintype "passive"))
      (node (ref "R29") (pin "1") (pinfunction "1_1") (pintype "passive"))
      (node (ref "R3") (pin "1") (pinfunction "1_1") (pintype "passive"))
      (node (ref "R30") (pin "1") (pinfunction "1_1") (pintype "passive"))
      (node (ref "R31") (pin "1") (pinfunction "1_1") (pintype "passive"))
      (node (ref "R32") (pin "1") (pinfunction "1_1") (pintype "passive"))
      (node (ref "R33") (pin "1") (pinfunction "1_1") (pintype "passive"))
      (node (ref "R34") (pin "1") (pinfunction "1_1") (pintype "passive"))
      (node (ref "R4") (pin "1") (pinfunction "1_1") (pintype "passive"))
      (node (ref "R43") (pin "1") (pinfunction "1_1") (pintype "passive"))
      (node (ref "R48") (pin "1") (pinfunction "1_1") (pintype "passive"))
      (node (ref "R49") (pin "1") (pinfunction "1_1") (pintype "passive"))
      (node (ref "R50") (pin "1") (pinfunction "1_1") (pintype "passive"))
      (node (ref "R51") (pin "1") (pinfunction "1_1") (pintype "passive"))
      (node (ref "R52") (pin "1") (pinfunction "1_1") (pintype "passive"))
      (node (ref "R53") (pin "1") (pinfunction "1_1") (pintype "passive"))
      (node (ref "R54") (pin "1") (pinfunction "1_1") (pintype "passive"))
      (node (ref "R55") (pin "1") (pinfunction "1_1") (pintype "passive"))
      (node (ref "R64") (pin "1") (pinfunction "1_1") (pintype "passive"))
      (node (ref "R65") (pin "1") (pinfunction "1_1") (pintype "passive"))
      (node (ref "R66") (pin "1") (pinfunction "1_1") (pintype "passive"))
      (node (ref "R75") (pin "1") (pinfunction "1_1") (pintype "passive"))
      (node (ref "R76") (pin "1") (pinfunction "1_1") (pintype "passive"))
      (node (ref "R80") (pin "2") (pinfunction "2_2") (pintype "passive"))
      (node (ref "R81") (pin "1") (pinfunction "1_1") (pintype "passive"))
      (node (ref "R82") (pin "1") (pinfunction "1_1") (pintype "passive"))
      (node (ref "R9") (pin "1") (pinfunction "1_1") (pintype "passive"))
      (node (ref "RJ1") (pin "11") (pinfunction "11_11") (pintype "passive"))
      (node (ref "RJ1") (pin "13") (pinfunction "13_13") (pintype "passive"))
      (node (ref "U2") (pin "9") (pinfunction "VDDIO_9") (pintype "passive"))
      (node (ref "U3") (pin "1") (pinfunction "A0_1") (pintype "passive"))
      (node (ref "U3") (pin "16") (pinfunction "VDD_16") (pintype "passive"))
      (node (ref "U3") (pin "2") (pinfunction "A1_2") (pintype "passive"))
      (node (ref "U4") (pin "1") (pinfunction "A0_1") (pintype "passive"))
      (node (ref "U4") (pin "16") (pinfunction "VDD_16") (pintype "passive"))
      (node (ref "U4") (pin "3") (pinfunction "A2_3") (pintype "passive"))
      (node (ref "U6") (pin "6") (pinfunction "VDD_6") (pintype "passive"))
      (node (ref "U6") (pin "7") (pinfunction "REGIN_7") (pintype "passive"))
      (node (ref "U8") (pin "2") (pinfunction "3V3_2") (pintype "passive"))
      (node (ref "U9") (pin "4") (pinfunction "Feedback_4") (pintype "passive"))
      (node (ref "X1") (pin "4") (pinfunction "VDD_4") (pintype "passive"))
    )
    (net (code "2") (name "/12V") (class "Default")
      (node (ref "C25") (pin "1") (pinfunction "1_1") (pintype "passive"))
      (node (ref "C26") (pin "1") (pinfunction "1_1") (pintype "passive"))
      (node (ref "C27") (pin "1") (pinfunction "1_1") (pintype "passive"))
      (node (ref "C34") (pin "1") (pinfunction "1_1") (pintype "passive"))
      (node (ref "C35") (pin "1") (pinfunction "1_1") (pintype "passive"))
      (node (ref "C36") (pin "1") (pinfunction "1_1") (pintype "passive"))
      (node (ref "D45") (pin "1") (pinfunction "C_1") (pintype "passive"))
      (node (ref "F10") (pin "1") (pinfunction "1_1") (pintype "passive"))
      (node (ref "F13") (pin "1") (pinfunction "1_1") (pintype "passive"))
      (node (ref "F14") (pin "1") (pinfunction "1_1") (pintype "passive"))
      (node (ref "F15") (pin "1") (pinfunction "1_1") (pintype "passive"))
      (node (ref "F16") (pin "1") (pinfunction "1_1") (pintype "passive"))
      (node (ref "F20") (pin "2") (pinfunction "2_2") (pintype "passive"))
      (node (ref "F7") (pin "1") (pinfunction "1_1") (pintype "passive"))
      (node (ref "F8") (pin "1") (pinfunction "1_1") (pintype "passive"))
      (node (ref "F9") (pin "1") (pinfunction "1_1") (pintype "passive"))
      (node (ref "LED1") (pin "1") (pinfunction "A_1") (pintype "passive"))
      (node (ref "LED2") (pin "1") (pinfunction "A_1") (pintype "passive"))
      (node (ref "LED3") (pin "1") (pinfunction "A_1") (pintype "passive"))
      (node (ref "LED4") (pin "1") (pinfunction "A_1") (pintype "passive"))
      (node (ref "LED5") (pin "1") (pinfunction "A_1") (pintype "passive"))
      (node (ref "LED6") (pin "1") (pinfunction "A_1") (pintype "passive"))
      (node (ref "LED7") (pin "1") (pinfunction "A_1") (pintype "passive"))
      (node (ref "LED8") (pin "1") (pinfunction "A_1") (pintype "passive"))
      (node (ref "LED9") (pin "1") (pinfunction "A_1") (pintype "passive"))
      (node (ref "P15") (pin "14") (pinfunction "14_14") (pintype "passive"))
      (node (ref "P15") (pin "16") (pinfunction "16_16") (pintype "passive"))
      (node (ref "P15") (pin "4") (pinfunction "4_4") (pintype "passive"))
      (node (ref "R86") (pin "1") (pinfunction "1_1") (pintype "passive"))
      (node (ref "U5") (pin "3") (pinfunction "IN_3") (pintype "passive"))
      (node (ref "U9") (pin "1") (pinfunction "Vin_1") (pintype "passive"))
    )
    (net (code "3") (name "/12V_POE") (class "Default")
      (node (ref "D41") (pin "2") (pinfunction "A_2") (pintype "passive"))
      (node (ref "D43") (pin "2") (pinfunction "A_2") (pintype "passive"))
      (node (ref "D8") (pin "1") (pinfunction "1_1") (pintype "passive"))
      (node (ref "U1") (pin "10") (pinfunction "+VDC_10") (pintype "passive"))
      (node (ref "U1") (pin "9") (pinfunction "+VDC_9") (pintype "passive"))
    )
    (net (code "4") (name "/AUX") (class "Default")
      (node (ref "D34") (pin "1") (pinfunction "1_1") (pintype "passive"))
      (node (ref "D43") (pin "1") (pinfunction "K_1") (pintype "passive"))
      (node (ref "D44") (pin "1") (pinfunction "K_1") (pintype "passive"))
      (node (ref "F17") (pin "2") (pinfunction "2_2") (pintype "passive"))
    )
    (net (code "5") (name "/AVDD") (class "Default")
      (node (ref "C11") (pin "1") (pinfunction "1_1") (pintype "passive"))
      (node (ref "C5") (pin "1") (pinfunction "1_1") (pintype "passive"))
      (node (ref "C6") (pin "1") (pinfunction "1_1") (pintype "passive"))
      (node (ref "C7") (pin "1") (pinfunction "1_1") (pintype "passive"))
      (node (ref "D1") (pin "2") (pinfunction "2_2") (pintype "passive"))
      (node (ref "D2") (pin "1") (pinfunction "1_1") (pintype "passive"))
      (node (ref "D3") (pin "2") (pinfunction "2_2") (pintype "passive"))
      (node (ref "D5") (pin "1") (pinfunction "1_1") (pintype "passive"))
      (node (ref "D7") (pin "1") (pinfunction "1_1") (pintype "passive"))
      (node (ref "L1") (pin "2") (pinfunction "2_2") (pintype "passive"))
      (node (ref "R5") (pin "1") (pinfunction "1_1") (pintype "passive"))
      (node (ref "R6") (pin "1") (pinfunction "1_1") (pintype "passive"))
      (node (ref "R7") (pin "1") (pinfunction "1_1") (pintype "passive"))
      (node (ref "R8") (pin "1") (pinfunction "1_1") (pintype "passive"))
      (node (ref "RJ1") (pin "3") (pinfunction "3_3") (pintype "passive"))
      (node (ref "RJ1") (pin "4") (pinfunction "4_4") (pintype "passive"))
      (node (ref "U2") (pin "1") (pinfunction "VDD2A_1") (pintype "passive"))
      (node (ref "U2") (pin "19") (pinfunction "VDD1A_19") (pintype "passive"))
    )
    (net (code "6") (name "/DTR") (class "Default")
      (node (ref "Q17") (pin "2") (pinfunction "E_2") (pintype "passive"))
      (node (ref "R71") (pin "2") (pinfunction "2_2") (pintype "passive"))
      (node (ref "U6") (pin "28") (pinfunction "DTR_28") (pintype "passive"))
    )
    (net (code "7") (name "/EN") (class "Default")
      (node (ref "C33") (pin "2") (pinfunction "2_2") (pintype "passive"))
      (node (ref "EN") (pin "3") (pinfunction "C_3") (pintype "passive"))
      (node (ref "Q18") (pin "3") (pinfunction "C_3") (pintype "passive"))
      (node (ref "R81") (pin "2") (pinfunction "2_2") (pintype "passive"))
      (node (ref "U8") (pin "3") (pinfunction "EN_3") (pintype "passive"))
    )
    (net (code "8") (name "/ESP_SCL") (class "Default")
      (node (ref "P15") (pin "15") (pinfunction "15_15") (pintype "passive"))
      (node (ref "R75") (pin "2") (pinfunction "2_2") (pintype "passive"))
      (node (ref "U3") (pin "14") (pinfunction "SCL_14") (pintype "passive"))
      (node (ref "U4") (pin "14") (pinfunction "SCL_14") (pintype "passive"))
      (node (ref "U7") (pin "6") (pinfunction "SCL_6") (pintype "passive"))
      (node (ref "U8") (pin "9") (pinfunction "IO33_9") (pintype "passive"))
    )
    (net (code "9") (name "/ESP_SDA") (class "Default")
      (node (ref "P15") (pin "17") (pinfunction "17_17") (pintype "passive"))
      (node (ref "R76") (pin "2") (pinfunction "2_2") (pintype "passive"))
      (node (ref "U3") (pin "15") (pinfunction "SDA_15") (pintype "passive"))
      (node (ref "U4") (pin "15") (pinfunction "SDA_15") (pintype "passive"))
      (node (ref "U7") (pin "5") (pinfunction "SDA_5") (pintype "passive"))
      (node (ref "U8") (pin "8") (pinfunction "IO32_8") (pintype "passive"))
    )
    (net (code "10") (name "/ETH_CRS_DV") (class "Default")
      (node (ref "R15") (pin "1") (pinfunction "1_1") (pintype "passive"))
      (node (ref "U8") (pin "12") (pinfunction "IO27_12") (pintype "passive"))
    )
    (net (code "11") (name "/ETH_MDC") (class "Default")
      (node (ref "U2") (pin "13") (pinfunction "MDC_13") (pintype "passive"))
      (node (ref "U8") (pin "37") (pinfunction "IO23_37") (pintype "passive"))
    )
    (net (code "12") (name "/ETH_MDIO") (class "Default")
      (node (ref "R4") (pin "2") (pinfunction "2_2") (pintype "passive"))
      (node (ref "U2") (pin "12") (pinfunction "MDIO_12") (pintype "passive"))
      (node (ref "U8") (pin "30") (pinfunction "IO18_30") (pintype "passive"))
    )
    (net (code "13") (name "/ETH_REFCLK") (class "Default")
      (node (ref "R83") (pin "2") (pinfunction "2_2") (pintype "passive"))
      (node (ref "RN1") (pin "1") (pinfunction "1_1") (pintype "passive"))
      (node (ref "RN1") (pin "2") (pinfunction "2_2") (pintype "passive"))
    )
    (net (code "14") (name "/ETH_RXD+") (class "Default")
      (node (ref "R12") (pin "1") (pinfunction "1_1") (pintype "passive"))
      (node (ref "U8") (pin "11") (pinfunction "IO26_11") (pintype "passive"))
    )
    (net (code "15") (name "/ETH_RXD-") (class "Default")
      (node (ref "R14") (pin "1") (pinfunction "1_1") (pintype "passive"))
      (node (ref "U8") (pin "10") (pinfunction "IO25_10") (pintype "passive"))
    )
    (net (code "16") (name "/ETH_TXD+") (class "Default")
      (node (ref "U2") (pin "18") (pinfunction "TXD1_18") (pintype "passive"))
      (node (ref "U8") (pin "36") (pinfunction "IO22_36") (pintype "passive"))
    )
    (net (code "17") (name "/ETH_TXD-") (class "Default")
      (node (ref "U2") (pin "17") (pinfunction "TXD0_17") (pintype "passive"))
      (node (ref "U8") (pin "31") (pinfunction "IO19_31") (pintype "passive"))
    )
    (net (code "18") (name "/ETH_TXDEN") (class "Default")
      (node (ref "U2") (pin "16") (pinfunction "TXEN_16") (pintype "passive"))
      (node (ref "U8") (pin "33") (pinfunction "IO21_33") (pintype "passive"))
    )
    (net (code "19") (name "/GPIO0") (class "Default")
      (node (ref "BOOT") (pin "3") (pinfunction "C_3") (pintype "passive"))
      (node (ref "Q17") (pin "3") (pinfunction "C_3") (pintype "passive"))
      (node (ref "R82") (pin "2") (pinfunction "2_2") (pintype "passive"))
      (node (ref "R83") (pin "1") (pinfunction "1_1") (pintype "passive"))
      (node (ref "U8") (pin "25") (pinfunction "IO0_25") (pintype "passive"))
    )
    (net (code "20") (name "/GPIO4") (class "Default")
      (node (ref "DIP1") (pin "1") (pinfunction "1_1") (pintype "passive"))
      (node (ref "P15") (pin "8") (pinfunction "8_8") (pintype "passive"))
      (node (ref "R74") (pin "1") (pinfunction "1_1") (pintype "passive"))
      (node (ref "U8") (pin "26") (pinfunction "IO4_26") (pintype "passive"))
    )
    (net (code "21") (name "/GPIO5") (class "Default")
      (node (ref "DIP1") (pin "2") (pinfunction "2_2") (pintype "passive"))
      (node (ref "P15") (pin "10") (pinfunction "10_10") (pintype "passive"))
      (node (ref "R77") (pin "1") (pinfunction "1_1") (pintype "passive"))
      (node (ref "U8") (pin "29") (pinfunction "IO5_29") (pintype "passive"))
    )
    (net (code "22") (name "/INPUT_0") (class "Default")
      (node (ref "C8") (pin "1") (pinfunction "1_1") (pintype "passive"))
      (node (ref "D4") (pin "1") (pinfunction "C_1") (pintype "passive"))
      (node (ref "D6") (pin "1") (pinfunction "1_1") (pintype "passive"))
      (node (ref "F1") (pin "2") (pinfunction "2_2") (pintype "passive"))
      (node (ref "R1") (pin "2") (pinfunction "2_2") (pintype "passive"))
      (node (ref "U4") (pin "4") (pinfunction "P0_4") (pintype "passive"))
    )
    (net (code "23") (name "/INPUT_1") (class "Default")
      (node (ref "C12") (pin "1") (pinfunction "1_1") (pintype "passive"))
      (node (ref "D10") (pin "1") (pinfunction "C_1") (pintype "passive"))
      (node (ref "D9") (pin "1") (pinfunction "1_1") (pintype "passive"))
      (node (ref "F2") (pin "1") (pinfunction "1_1") (pintype "passive"))
      (node (ref "R9") (pin "2") (pinfunction "2_2") (pintype "passive"))
      (node (ref "U4") (pin "5") (pinfunction "P1_5") (pintype "passive"))
    )
    (net (code "24") (name "/INPUT_2") (class "Default")
      (node (ref "C16") (pin "1") (pinfunction "1_1") (pintype "passive"))
      (node (ref "D12") (pin "1") (pinfunction "C_1") (pintype "passive"))
      (node (ref "D13") (pin "1") (pinfunction "1_1") (pintype "passive"))
      (node (ref "F3") (pin "2") (pinfunction "2_2") (pintype "passive"))
      (node (ref "R16") (pin "2") (pinfunction "2_2") (pintype "passive"))
      (node (ref "U4") (pin "6") (pinfunction "P2_6") (pintype "passive"))
    )
    (net (code "25") (name "/INPUT_3") (class "Default")
      (node (ref "C18") (pin "1") (pinfunction "1_1") (pintype "passive"))
      (node (ref "D14") (pin "1") (pinfunction "1_1") (pintype "passive"))
      (node (ref "D15") (pin "1") (pinfunction "C_1") (pintype "passive"))
      (node (ref "F4") (pin "1") (pinfunction "1_1") (pintype "passive"))
      (node (ref "R19") (pin "2") (pinfunction "2_2") (pintype "passive"))
      (node (ref "U4") (pin "7") (pinfunction "P3_7") (pintype "passive"))
    )
    (net (code "26") (name "/INPUT_4") (class "Default")
      (node (ref "C19") (pin "1") (pinfunction "1_1") (pintype "passive"))
      (node (ref "D16") (pin "1") (pinfunction "C_1") (pintype "passive"))
      (node (ref "D17") (pin "1") (pinfunction "1_1") (pintype "passive"))
      (node (ref "F5") (pin "2") (pinfunction "2_2") (pintype "passive"))
      (node (ref "R20") (pin "2") (pinfunction "2_2") (pintype "passive"))
      (node (ref "U4") (pin "9") (pinfunction "P4_9") (pintype "passive"))
    )
    (net (code "27") (name "/INPUT_5") (class "Default")
      (node (ref "C20") (pin "1") (pinfunction "1_1") (pintype "passive"))
      (node (ref "D18") (pin "1") (pinfunction "1_1") (pintype "passive"))
      (node (ref "D19") (pin "1") (pinfunction "C_1") (pintype "passive"))
      (node (ref "F6") (pin "1") (pinfunction "1_1") (pintype "passive"))
      (node (ref "R21") (pin "2") (pinfunction "2_2") (pintype "passive"))
      (node (ref "U4") (pin "10") (pinfunction "P5_10") (pintype "passive"))
    )
    (net (code "28") (name "/INPUT_6") (class "Default")
      (node (ref "C21") (pin "1") (pinfunction "1_1") (pintype "passive"))
      (node (ref "D24") (pin "1") (pinfunction "C_1") (pintype "passive"))
      (node (ref "D25") (pin "1") (pinfunction "1_1") (pintype "passive"))
      (node (ref "F11") (pin "2") (pinfunction "2_2") (pintype "passive"))
      (node (ref "R34") (pin "2") (pinfunction "2_2") (pintype "passive"))
      (node (ref "U4") (pin "11") (pinfunction "P6_11") (pintype "passive"))
    )
    (net (code "29") (name "/INPUT_7") (class "Default")
      (node (ref "C22") (pin "1") (pinfunction "1_1") (pintype "passive"))
      (node (ref "D26") (pin "1") (pinfunction "1_1") (pintype "passive"))
      (node (ref "D27") (pin "1") (pinfunction "C_1") (pintype "passive"))
      (node (ref "F12") (pin "1") (pinfunction "1_1") (pintype "passive"))
      (node (ref "R43") (pin "2") (pinfunction "2_2") (pintype "passive"))
      (node (ref "U4") (pin "12") (pinfunction "P7_12") (pintype "passive"))
    )
    (net (code "30") (name "/INT") (class "Default")
      (node (ref "R66") (pin "2") (pinfunction "2_2") (pintype "passive"))
      (node (ref "R67") (pin "2") (pinfunction "2_2") (pintype "passive"))
      (node (ref "U4") (pin "13") (pinfunction "INT#_13") (pintype "passive"))
    )
    (net (code "31") (name "/INT_ESP32") (class "Default")
      (node (ref "DIP1") (pin "4") (pinfunction "4_4") (pintype "passive"))
      (node (ref "P15") (pin "9") (pinfunction "9_9") (pintype "passive"))
      (node (ref "U8") (pin "16") (pinfunction "IO13_16") (pintype "passive"))
    )
    (net (code "32") (name "/IO12") (class "Default")
      (node (ref "P15") (pin "5") (pinfunction "5_5") (pintype "passive"))
      (node (ref "U8") (pin "14") (pinfunction "IO12_14") (pintype "passive"))
    )
    (net (code "33") (name "/IO16") (class "Default")
      (node (ref "P15") (pin "7") (pinfunction "7_7") (pintype "passive"))
      (node (ref "U8") (pin "27") (pinfunction "IO16_27") (pintype "passive"))
    )
    (net (code "34") (name "/LED_G") (class "Default")
      (node (ref "R13") (pin "2") (pinfunction "2_2") (pintype "passive"))
      (node (ref "U2") (pin "3") (pinfunction "LED1/REGOFF_3") (pintype "passive"))
    )
    (net (code "35") (name "/LED_Y") (class "Default")
      (node (ref "R10") (pin "2") (pinfunction "2_2") (pintype "passive"))
      (node (ref "U2") (pin "2") (pinfunction "LED2/nINTSEL_2") (pintype "passive"))
    )
    (net (code "36") (name "/OUT_1") (class "Default")
      (node (ref "R26") (pin "2") (pinfunction "2_2") (pintype "passive"))
      (node (ref "R35") (pin "2") (pinfunction "2_2") (pintype "passive"))
      (node (ref "U3") (pin "4") (pinfunction "P0_4") (pintype "passive"))
    )
    (net (code "37") (name "/OUT_2") (class "Default")
      (node (ref "R28") (pin "2") (pinfunction "2_2") (pintype "passive"))
      (node (ref "R36") (pin "2") (pinfunction "2_2") (pintype "passive"))
      (node (ref "U3") (pin "5") (pinfunction "P1_5") (pintype "passive"))
    )
    (net (code "38") (name "/OUT_3") (class "Default")
      (node (ref "R30") (pin "2") (pinfunction "2_2") (pintype "passive"))
      (node (ref "R37") (pin "2") (pinfunction "2_2") (pintype "passive"))
      (node (ref "U3") (pin "6") (pinfunction "P2_6") (pintype "passive"))
    )
    (net (code "39") (name "/OUT_4") (class "Default")
      (node (ref "R32") (pin "2") (pinfunction "2_2") (pintype "passive"))
      (node (ref "R38") (pin "2") (pinfunction "2_2") (pintype "passive"))
      (node (ref "U3") (pin "7") (pinfunction "P3_7") (pintype "passive"))
    )
    (net (code "40") (name "/OUT_5") (class "Default")
      (node (ref "R48") (pin "2") (pinfunction "2_2") (pintype "passive"))
      (node (ref "R56") (pin "2") (pinfunction "2_2") (pintype "passive"))
      (node (ref "U3") (pin "9") (pinfunction "P4_9") (pintype "passive"))
    )
    (net (code "41") (name "/OUT_6") (class "Default")
      (node (ref "R50") (pin "2") (pinfunction "2_2") (pintype "passive"))
      (node (ref "R57") (pin "2") (pinfunction "2_2") (pintype "passive"))
      (node (ref "U3") (pin "10") (pinfunction "P5_10") (pintype "passive"))
    )
    (net (code "42") (name "/OUT_7") (class "Default")
      (node (ref "R52") (pin "2") (pinfunction "2_2") (pintype "passive"))
      (node (ref "R58") (pin "2") (pinfunction "2_2") (pintype "passive"))
      (node (ref "U3") (pin "11") (pinfunction "P6_11") (pintype "passive"))
    )
    (net (code "43") (name "/OUT_8") (class "Default")
      (node (ref "R54") (pin "2") (pinfunction "2_2") (pintype "passive"))
      (node (ref "R60") (pin "2") (pinfunction "2_2") (pintype "passive"))
      (node (ref "U3") (pin "12") (pinfunction "P7_12") (pintype "passive"))
    )
    (net (code "44") (name "/PHY_PWR_ESP32") (class "Default")
      (node (ref "DIP1") (pin "3") (pinfunction "3_3") (pintype "passive"))
      (node (ref "P15") (pin "11") (pinfunction "11_11") (pintype "passive"))
      (node (ref "U8") (pin "28") (pinfunction "IO17_28") (pintype "passive"))
    )
    (net (code "45") (name "/PHY_PWR_ETH") (class "Default")
      (node (ref "DIP1") (pin "6") (pinfunction "6_6") (pintype "passive"))
      (node (ref "R17") (pin "1") (pinfunction "1_1") (pintype "passive"))
    )
    (net (code "46") (name "/RD+") (class "Default")
      (node (ref "D2") (pin "2") (pinfunction "2_2") (pintype "passive"))
      (node (ref "R5") (pin "2") (pinfunction "2_2") (pintype "passive"))
      (node (ref "RJ1") (pin "1") (pinfunction "1_1") (pintype "passive"))
      (node (ref "U2") (pin "23") (pinfunction "RXP_23") (pintype "passive"))
    )
    (net (code "47") (name "/RD-") (class "Default")
      (node (ref "D1") (pin "1") (pinfunction "1_1") (pintype "passive"))
      (node (ref "R6") (pin "2") (pinfunction "2_2") (pintype "passive"))
      (node (ref "RJ1") (pin "2") (pinfunction "2_2") (pintype "passive"))
      (node (ref "U2") (pin "22") (pinfunction "RXN_22") (pintype "passive"))
    )
    (net (code "48") (name "/RTS") (class "Default")
      (node (ref "Q18") (pin "2") (pinfunction "E_2") (pintype "passive"))
      (node (ref "R68") (pin "2") (pinfunction "2_2") (pintype "passive"))
      (node (ref "U6") (pin "24") (pinfunction "RTS_24") (pintype "passive"))
    )
    (net (code "49") (name "/RXD") (class "Default")
      (node (ref "H1") (pin "4") (pinfunction "4_4") (pintype "passive"))
      (node (ref "R69") (pin "1") (pinfunction "1_1") (pintype "passive"))
      (node (ref "U8") (pin "34") (pinfunction "RXD0_34") (pintype "passive"))
    )
    (net (code "50") (name "/TD+") (class "Default")
      (node (ref "D5") (pin "2") (pinfunction "2_2") (pintype "passive"))
      (node (ref "R7") (pin "2") (pinfunction "2_2") (pintype "passive"))
      (node (ref "RJ1") (pin "5") (pinfunction "5_5") (pintype "passive"))
      (node (ref "U2") (pin "21") (pinfunction "TXP_21") (pintype "passive"))
    )
    (net (code "51") (name "/TD-") (class "Default")
      (node (ref "D3") (pin "1") (pinfunction "1_1") (pintype "passive"))
      (node (ref "R8") (pin "2") (pinfunction "2_2") (pintype "passive"))
      (node (ref "RJ1") (pin "6") (pinfunction "6_6") (pintype "passive"))
      (node (ref "U2") (pin "20") (pinfunction "TXN_20") (pintype "passive"))
    )
    (net (code "52") (name "/TXD") (class "Default")
      (node (ref "H1") (pin "5") (pinfunction "5_5") (pintype "passive"))
      (node (ref "R70") (pin "1") (pinfunction "1_1") (pintype "passive"))
      (node (ref "U8") (pin "35") (pinfunction "TXD0_35") (pintype "passive"))
    )
    (net (code "53") (name "/USB_DN") (class "Default")
      (node (ref "D33") (pin "2") (pinfunction "2_2") (pintype "passive"))
      (node (ref "U6") (pin "5") (pinfunction "D-_5") (pintype "passive"))
      (node (ref "USB1") (pin "A7") (pinfunction "DN1_A7") (pintype "passive"))
      (node (ref "USB1") (pin "B7") (pinfunction "DN2_B7") (pintype "passive"))
    )
    (net (code "54") (name "/USB_DP") (class "Default")
      (node (ref "D32") (pin "2") (pinfunction "2_2") (pintype "passive"))
      (node (ref "U6") (pin "4") (pinfunction "D+_4") (pintype "passive"))
      (node (ref "USB1") (pin "A6") (pinfunction "DP1_A6") (pintype "passive"))
      (node (ref "USB1") (pin "B6") (pinfunction "DP2_B6") (pintype "passive"))
    )
    (net (code "55") (name "/USB_RX") (class "Default")
      (node (ref "R69") (pin "2") (pinfunction "2_2") (pintype "passive"))
      (node (ref "U6") (pin "26") (pinfunction "TXD_26") (pintype "passive"))
    )
    (net (code "56") (name "/USB_TX") (class "Default")
      (node (ref "R70") (pin "2") (pinfunction "2_2") (pintype "passive"))
      (node (ref "U6") (pin "25") (pinfunction "RXD_25") (pintype "passive"))
    )
    (net (code "57") (name "/USB_VBUS") (class "Default")
      (node (ref "R78") (pin "1") (pinfunction "1_1") (pintype "passive"))
      (node (ref "USB1") (pin "A4") (pinfunction "VBUS_A4") (pintype "passive"))
      (node (ref "USB1") (pin "A9") (pinfunction "VBUS_A9") (pintype "passive"))
      (node (ref "USB1") (pin "B4") (pinfunction "VBUS_B4") (pintype "passive"))
      (node (ref "USB1") (pin "B9") (pinfunction "VBUS_B9") (pintype "passive"))
    )
    (net (code "58") (name "EGND") (class "Default")
      (node (ref "C13") (pin "1") (pinfunction "1_1") (pintype "passive"))
      (node (ref "RJ1") (pin "GND1") (pinfunction "GND_GND1") (pintype "passive"))
      (node (ref "RJ1") (pin "GND2") (pinfunction "GND_GND2") (pintype "passive"))
    )
    (net (code "59") (name "GND") (class "Default")
      (node (ref "BOOT") (pin "2") (pinfunction "B_2") (pintype "passive"))
      (node (ref "BT1") (pin "2") (pinfunction "2_2") (pintype "passive"))
      (node (ref "C1") (pin "2") (pinfunction "2_2") (pintype "passive"))
      (node (ref "C10") (pin "2") (pinfunction "2_2") (pintype "passive"))
      (node (ref "C11") (pin "2") (pinfunction "2_2") (pintype "passive"))
      (node (ref "C12") (pin "2") (pinfunction "2_2") (pintype "passive"))
      (node (ref "C13") (pin "2") (pinfunction "2_2") (pintype "passive"))
      (node (ref "C14") (pin "2") (pinfunction "2_2") (pintype "passive"))
      (node (ref "C15") (pin "2") (pinfunction "2_2") (pintype "passive"))
      (node (ref "C16") (pin "2") (pinfunction "2_2") (pintype "passive"))
      (node (ref "C17") (pin "2") (pinfunction "2_2") (pintype "passive"))
      (node (ref "C18") (pin "2") (pinfunction "2_2") (pintype "passive"))
      (node (ref "C19") (pin "2") (pinfunction "2_2") (pintype "passive"))
      (node (ref "C2") (pin "2") (pinfunction "2_2") (pintype "passive"))
      (node (ref "C20") (pin "2") (pinfunction "2_2") (pintype "passive"))
      (node (ref "C21") (pin "2") (pinfunction "2_2") (pintype "passive"))
      (node (ref "C22") (pin "2") (pinfunction "2_2") (pintype "passive"))
      (node (ref "C23") (pin "2") (pinfunction "2_2") (pintype "passive"))
      (node (ref "C24") (pin "2") (pinfunction "2_2") (pintype "passive"))
      (node (ref "C25") (pin "2") (pinfunction "2_2") (pintype "passive"))
      (node (ref "C26") (pin "2") (pinfunction "2_2") (pintype "passive"))
      (node (ref "C27") (pin "2") (pinfunction "2_2") (pintype "passive"))
      (node (ref "C28") (pin "2") (pinfunction "2_2") (pintype "passive"))
      (node (ref "C29") (pin "1") (pinfunction "1_1") (pintype "passive"))
      (node (ref "C3") (pin "2") (pinfunction "2_2") (pintype "passive"))
      (node (ref "C30") (pin "2") (pinfunction "2_2") (pintype "passive"))
      (node (ref "C31") (pin "2") (pinfunction "2_2") (pintype "passive"))
      (node (ref "C32") (pin "2") (pinfunction "2_2") (pintype "passive"))
      (node (ref "C33") (pin "1") (pinfunction "1_1") (pintype "passive"))
      (node (ref "C34") (pin "2") (pinfunction "2_2") (pintype "passive"))
      (node (ref "C35") (pin "2") (pinfunction "2_2") (pintype "passive"))
      (node (ref "C36") (pin "2") (pinfunction "2_2") (pintype "passive"))
      (node (ref "C37") (pin "2") (pinfunction "2_2") (pintype "passive"))
      (node (ref "C4") (pin "2") (pinfunction "2_2") (pintype "passive"))
      (node (ref "C5") (pin "2") (pinfunction "2_2") (pintype "passive"))
      (node (ref "C6") (pin "2") (pinfunction "2_2") (pintype "passive"))
      (node (ref "C7") (pin "2") (pinfunction "2_2") (pintype "passive"))
      (node (ref "C8") (pin "2") (pinfunction "2_2") (pintype "passive"))
      (node (ref "C9") (pin "2") (pinfunction "2_2") (pintype "passive"))
      (node (ref "D10") (pin "2") (pinfunction "A_2") (pintype "passive"))
      (node (ref "D12") (pin "2") (pinfunction "A_2") (pintype "passive"))
      (node (ref "D13") (pin "2") (pinfunction "2_2") (pintype "passive"))
      (node (ref "D14") (pin "2") (pinfunction "2_2") (pintype "passive"))
      (node (ref "D15") (pin "2") (pinfunction "A_2") (pintype "passive"))
      (node (ref "D16") (pin "2") (pinfunction "A_2") (pintype "passive"))
      (node (ref "D17") (pin "2") (pinfunction "2_2") (pintype "passive"))
      (node (ref "D18") (pin "2") (pinfunction "2_2") (pintype "passive"))
      (node (ref "D19") (pin "2") (pinfunction "A_2") (pintype "passive"))
      (node (ref "D24") (pin "2") (pinfunction "A_2") (pintype "passive"))
      (node (ref "D25") (pin "2") (pinfunction "2_2") (pintype "passive"))
      (node (ref "D26") (pin "2") (pinfunction "2_2") (pintype "passive"))
      (node (ref "D27") (pin "2") (pinfunction "A_2") (pintype "passive"))
      (node (ref "D32") (pin "1") (pinfunction "1_1") (pintype "passive"))
      (node (ref "D33") (pin "1") (pinfunction "1_1") (pintype "passive"))
      (node (ref "D34") (pin "2") (pinfunction "2_2") (pintype "passive"))
      (node (ref "D35") (pin "2") (pinfunction "2_2") (pintype "passive"))
      (node (ref "D36") (pin "2") (pinfunction "2_2") (pintype "passive"))
      (node (ref "D37") (pin "2") (pinfunction "A_2") (pintype "passive"))
      (node (ref "D38") (pin "2") (pinfunction "A_2") (pintype "passive"))
      (node (ref "D39") (pin "1") (pinfunction "1_1") (pintype "passive"))
      (node (ref "D4") (pin "2") (pinfunction "A_2") (pintype "passive"))
      (node (ref "D40") (pin "2") (pinfunction "A_2") (pintype "passive"))
      (node (ref "D45") (pin "2") (pinfunction "A_2") (pintype "passive"))
      (node (ref "D46") (pin "2") (pinfunction "2_2") (pintype "passive"))
      (node (ref "D47") (pin "2") (pinfunction "+_2") (pintype "passive"))
      (node (ref "D6") (pin "2") (pinfunction "2_2") (pintype "passive"))
      (node (ref "D7") (pin "2") (pinfunction "2_2") (pintype "passive"))
      (node (ref "D8") (pin "2") (pinfunction "2_2") (pintype "passive"))
      (node (ref "D9") (pin "2") (pinfunction "2_2") (pintype "passive"))
      (node (ref "EN") (pin "2") (pinfunction "B_2") (pintype "passive"))
      (node (ref "H1") (pin "1") (pinfunction "1_1") (pintype "passive"))
      (node (ref "P1") (pin "2") (pinfunction "2_2") (pintype "passive"))
      (node (ref "P13") (pin "1") (pinfunction "1_1") (pintype "passive"))
      (node (ref "P15") (pin "1") (pinfunction "1_1") (pintype "passive"))
      (node (ref "P15") (pin "12") (pinfunction "12_12") (pintype "passive"))
      (node (ref "P15") (pin "18") (pinfunction "18_18") (pintype "passive"))
      (node (ref "P15") (pin "19") (pinfunction "19_19") (pintype "passive"))
      (node (ref "P15") (pin "2") (pinfunction "2_2") (pintype "passive"))
      (node (ref "P15") (pin "20") (pinfunction "20_20") (pintype "passive"))
      (node (ref "P15") (pin "3") (pinfunction "3_3") (pintype "passive"))
      (node (ref "P15") (pin "6") (pinfunction "6_6") (pintype "passive"))
      (node (ref "P16") (pin "1") (pinfunction "1_1") (pintype "passive"))
      (node (ref "P2") (pin "2") (pinfunction "2_2") (pintype "passive"))
      (node (ref "P3") (pin "2") (pinfunction "2_2") (pintype "passive"))
      (node (ref "P8") (pin "2") (pinfunction "2_2") (pintype "passive"))
      (node (ref "Q1") (pin "2") (pinfunction "S_2") (pintype "passive"))
      (node (ref "Q10") (pin "2") (pinfunction "S_2") (pintype "passive"))
      (node (ref "Q11") (pin "2") (pinfunction "S_2") (pintype "passive"))
      (node (ref "Q12") (pin "2") (pinfunction "S_2") (pintype "passive"))
      (node (ref "Q13") (pin "2") (pinfunction "E_2") (pintype "passive"))
      (node (ref "Q14") (pin "2") (pinfunction "E_2") (pintype "passive"))
      (node (ref "Q15") (pin "2") (pinfunction "E_2") (pintype "passive"))
      (node (ref "Q16") (pin "2") (pinfunction "E_2") (pintype "passive"))
      (node (ref "Q19") (pin "2") (pinfunction "S_2") (pintype "passive"))
      (node (ref "Q2") (pin "2") (pinfunction "S_2") (pintype "passive"))
      (node (ref "Q3") (pin "2") (pinfunction "S_2") (pintype "passive"))
      (node (ref "Q4") (pin "2") (pinfunction "S_2") (pintype "passive"))
      (node (ref "Q5") (pin "2") (pinfunction "E_2") (pintype "passive"))
      (node (ref "Q6") (pin "2") (pinfunction "E_2") (pintype "passive"))
      (node (ref "Q7") (pin "2") (pinfunction "E_2") (pintype "passive"))
      (node (ref "Q8") (pin "2") (pinfunction "E_2") (pintype "passive"))
      (node (ref "Q9") (pin "2") (pinfunction "S_2") (pintype "passive"))
      (node (ref "R11") (pin "2") (pinfunction "2_2") (pintype "passive"))
      (node (ref "R18") (pin "2") (pinfunction "2_2") (pintype "passive"))
      (node (ref "R39") (pin "2") (pinfunction "2_2") (pintype "passive"))
      (node (ref "R40") (pin "2") (pinfunction "2_2") (pintype "passive"))
      (node (ref "R41") (pin "2") (pinfunction "2_2") (pintype "passive"))
      (node (ref "R42") (pin "2") (pinfunction "2_2") (pintype "passive"))
      (node (ref "R59") (pin "2") (pinfunction "2_2") (pintype "passive"))
      (node (ref "R61") (pin "2") (pinfunction "2_2") (pintype "passive"))
      (node (ref "R62") (pin "2") (pinfunction "2_2") (pintype "passive"))
      (node (ref "R63") (pin "2") (pinfunction "2_2") (pintype "passive"))
      (node (ref "R72") (pin "2") (pinfunction "2_2") (pintype "passive"))
      (node (ref "R73") (pin "2") (pinfunction "2_2") (pintype "passive"))
      (node (ref "R79") (pin "2") (pinfunction "2_2") (pintype "passive"))
      (node (ref "R84") (pin "2") (pinfunction "2_2") (pintype "passive"))
      (node (ref "R87") (pin "2") (pinfunction "2_2") (pintype "passive"))
      (node (ref "RF1") (pin "2") (pinfunction "GND_2") (pintype "passive"))
      (node (ref "RF1") (pin "3") (pinfunction "GND_3") (pintype "passive"))
      (node (ref "RF1") (pin "4") (pinfunction "GND_4") (pintype "passive"))
      (node (ref "RF1") (pin "5") (pinfunction "GND_5") (pintype "passive"))
      (node (ref "U1") (pin "7") (pinfunction "-VDC_7") (pintype "passive"))
      (node (ref "U1") (pin "8") (pinfunction "-VDC_8") (pintype "passive"))
      (node (ref "U2") (pin "25") (pinfunction "EP_25") (pintype "passive"))
      (node (ref "U3") (pin "3") (pinfunction "A2_3") (pintype "passive"))
      (node (ref "U3") (pin "8") (pinfunction "VSS_8") (pintype "passive"))
      (node (ref "U4") (pin "2") (pinfunction "A1_2") (pintype "passive"))
      (node (ref "U4") (pin "8") (pinfunction "VSS_8") (pintype "passive"))
      (node (ref "U5") (pin "2") (pinfunction "GND_2") (pintype "passive"))
      (node (ref "U6") (pin "29") (pinfunction "EP_29") (pintype "passive"))
      (node (ref "U6") (pin "3") (pinfunction "GND_3") (pintype "passive"))
      (node (ref "U7") (pin "4") (pinfunction "GND_4") (pintype "passive"))
      (node (ref "U8") (pin "1") (pinfunction "GND_1") (pintype "passive"))
      (node (ref "U8") (pin "15") (pinfunction "GND_15") (pintype "passive"))
      (node (ref "U8") (pin "38") (pinfunction "GND_38") (pintype "passive"))
      (node (ref "U8") (pin "39") (pinfunction "GND_39") (pintype "passive"))
      (node (ref "U9") (pin "3") (pinfunction "Gnd_3") (pintype "passive"))
      (node (ref "U9") (pin "5") (pinfunction "ON#/OFF_5") (pintype "passive"))
      (node (ref "U9") (pin "6") (pinfunction "TAB_6") (pintype "passive"))
      (node (ref "USB1") (pin "A1") (pinfunction "GND_A1") (pintype "passive"))
      (node (ref "USB1") (pin "A12") (pinfunction "GND_A12") (pintype "passive"))
      (node (ref "USB1") (pin "B1") (pinfunction "GND_B1") (pintype "passive"))
      (node (ref "USB1") (pin "B12") (pinfunction "GND_B12") (pintype "passive"))
      (node (ref "X1") (pin "2") (pinfunction "GND_2") (pintype "passive"))
    )
    (net (code "60") (name "Net-(C24-Pad1)") (class "Default")
      (node (ref "C24") (pin "1") (pinfunction "1_1") (pintype "passive"))
      (node (ref "USB1") (pin "1") (pinfunction "EP_1") (pintype "passive"))
      (node (ref "USB1") (pin "2") (pinfunction "EP_2") (pintype "passive"))
      (node (ref "USB1") (pin "3") (pinfunction "EP_3") (pintype "passive"))
      (node (ref "USB1") (pin "4") (pinfunction "EP_4") (pintype "passive"))
    )
    (net (code "61") (name "Net-(D20-+)") (class "Default")
      (node (ref "D20") (pin "2") (pinfunction "+_2") (pintype "passive"))
      (node (ref "Q1") (pin "3") (pinfunction "D_3") (pintype "passive"))
      (node (ref "R22") (pin "2") (pinfunction "2_2") (pintype "passive"))
      (node (ref "RELAY1") (pin "1") (pinfunction "1_1") (pintype "passive"))
    )
    (net (code "62") (name "Net-(D20--)") (class "Default")
      (node (ref "D20") (pin "1") (pinfunction "-_1") (pintype "passive"))
      (node (ref "F7") (pin "2") (pinfunction "2_2") (pintype "passive"))
      (node (ref "RELAY1") (pin "4") (pinfunction "4_4") (pintype "passive"))
    )
    (net (code "63") (name "Net-(D21-+)") (class "Default")
      (node (ref "D21") (pin "2") (pinfunction "+_2") (pintype "passive"))
      (node (ref "Q2") (pin "3") (pinfunction "D_3") (pintype "passive"))
      (node (ref "R23") (pin "2") (pinfunction "2_2") (pintype "passive"))
      (node (ref "RELAY2") (pin "1") (pinfunction "1_1") (pintype "passive"))
    )
    (net (code "64") (name "Net-(D21--)") (class "Default")
      (node (ref "D21") (pin "1") (pinfunction "-_1") (pintype "passive"))
      (node (ref "F8") (pin "2") (pinfunction "2_2") (pintype "passive"))
      (node (ref "RELAY2") (pin "4") (pinfunction "4_4") (pintype "passive"))
    )
    (net (code "65") (name "Net-(D22-+)") (class "Default")
      (node (ref "D22") (pin "2") (pinfunction "+_2") (pintype "passive"))
      (node (ref "Q3") (pin "3") (pinfunction "D_3") (pintype "passive"))
      (node (ref "R24") (pin "2") (pinfunction "2_2") (pintype "passive"))
      (node (ref "RELAY3") (pin "1") (pinfunction "1_1") (pintype "passive"))
    )
    (net (code "66") (name "Net-(D22--)") (class "Default")
      (node (ref "D22") (pin "1") (pinfunction "-_1") (pintype "passive"))
      (node (ref "F9") (pin "2") (pinfunction "2_2") (pintype "passive"))
      (node (ref "RELAY3") (pin "4") (pinfunction "4_4") (pintype "passive"))
    )
    (net (code "67") (name "Net-(D23-+)") (class "Default")
      (node (ref "D23") (pin "2") (pinfunction "+_2") (pintype "passive"))
      (node (ref "Q4") (pin "3") (pinfunction "D_3") (pintype "passive"))
      (node (ref "R25") (pin "2") (pinfunction "2_2") (pintype "passive"))
      (node (ref "RELAY4") (pin "1") (pinfunction "1_1") (pintype "passive"))
    )
    (net (code "68") (name "Net-(D23--)") (class "Default")
      (node (ref "D23") (pin "1") (pinfunction "-_1") (pintype "passive"))
      (node (ref "F10") (pin "2") (pinfunction "2_2") (pintype "passive"))
      (node (ref "RELAY4") (pin "4") (pinfunction "4_4") (pintype "passive"))
    )
    (net (code "69") (name "Net-(D28-+)") (class "Default")
      (node (ref "D28") (pin "2") (pinfunction "+_2") (pintype "passive"))
      (node (ref "Q9") (pin "3") (pinfunction "D_3") (pintype "passive"))
      (node (ref "R44") (pin "2") (pinfunction "2_2") (pintype "passive"))
      (node (ref "RELAY5") (pin "1") (pinfunction "1_1") (pintype "passive"))
    )
    (net (code "70") (name "Net-(D28--)") (class "Default")
      (node (ref "D28") (pin "1") (pinfunction "-_1") (pintype "passive"))
      (node (ref "F13") (pin "2") (pinfunction "2_2") (pintype "passive"))
      (node (ref "RELAY5") (pin "4") (pinfunction "4_4") (pintype "passive"))
    )
    (net (code "71") (name "Net-(D29-+)") (class "Default")
      (node (ref "D29") (pin "2") (pinfunction "+_2") (pintype "passive"))
      (node (ref "Q10") (pin "3") (pinfunction "D_3") (pintype "passive"))
      (node (ref "R45") (pin "2") (pinfunction "2_2") (pintype "passive"))
      (node (ref "RELAY6") (pin "1") (pinfunction "1_1") (pintype "passive"))
    )
    (net (code "72") (name "Net-(D29--)") (class "Default")
      (node (ref "D29") (pin "1") (pinfunction "-_1") (pintype "passive"))
      (node (ref "F14") (pin "2") (pinfunction "2_2") (pintype "passive"))
      (node (ref "RELAY6") (pin "4") (pinfunction "4_4") (pintype "passive"))
    )
    (net (code "73") (name "Net-(D30-+)") (class "Default")
      (node (ref "D30") (pin "2") (pinfunction "+_2") (pintype "passive"))
      (node (ref "Q11") (pin "3") (pinfunction "D_3") (pintype "passive"))
      (node (ref "R46") (pin "2") (pinfunction "2_2") (pintype "passive"))
      (node (ref "RELAY7") (pin "1") (pinfunction "1_1") (pintype "passive"))
    )
    (net (code "74") (name "Net-(D30--)") (class "Default")
      (node (ref "D30") (pin "1") (pinfunction "-_1") (pintype "passive"))
      (node (ref "F15") (pin "2") (pinfunction "2_2") (pintype "passive"))
      (node (ref "RELAY7") (pin "4") (pinfunction "4_4") (pintype "passive"))
    )
    (net (code "75") (name "Net-(D31-+)") (class "Default")
      (node (ref "D31") (pin "2") (pinfunction "+_2") (pintype "passive"))
      (node (ref "Q12") (pin "3") (pinfunction "D_3") (pintype "passive"))
      (node (ref "R47") (pin "2") (pinfunction "2_2") (pintype "passive"))
      (node (ref "RELAY8") (pin "1") (pinfunction "1_1") (pintype "passive"))
    )
    (net (code "76") (name "Net-(D31--)") (class "Default")
      (node (ref "D31") (pin "1") (pinfunction "-_1") (pintype "passive"))
      (node (ref "F16") (pin "2") (pinfunction "2_2") (pintype "passive"))
      (node (ref "RELAY8") (pin "4") (pinfunction "4_4") (pintype "passive"))
    )
    (net (code "77") (name "Net-(D37-C)") (class "Default")
      (node (ref "D35") (pin "1") (pinfunction "1_1") (pintype "passive"))
      (node (ref "D37") (pin "1") (pinfunction "C_1") (pintype "passive"))
      (node (ref "F18") (pin "1") (pinfunction "1_1") (pintype "passive"))
      (node (ref "R74") (pin "2") (pinfunction "2_2") (pintype "passive"))
    )
    (net (code "78") (name "Net-(D38-C)") (class "Default")
      (node (ref "D36") (pin "1") (pinfunction "1_1") (pintype "passive"))
      (node (ref "D38") (pin "1") (pinfunction "C_1") (pintype "passive"))
      (node (ref "F19") (pin "1") (pinfunction "1_1") (pintype "passive"))
      (node (ref "R77") (pin "2") (pinfunction "2_2") (pintype "passive"))
    )
    (net (code "79") (name "Net-(D40-C)") (class "Default")
      (node (ref "D39") (pin "2") (pinfunction "2_2") (pintype "passive"))
      (node (ref "D40") (pin "1") (pinfunction "C_1") (pintype "passive"))
      (node (ref "R78") (pin "2") (pinfunction "2_2") (pintype "passive"))
      (node (ref "R79") (pin "1") (pinfunction "1_1") (pintype "passive"))
      (node (ref "U6") (pin "8") (pinfunction "VBUS_8") (pintype "passive"))
    )
    (net (code "80") (name "Net-(D41-K)") (class "Default")
      (node (ref "D41") (pin "1") (pinfunction "K_1") (pintype "passive"))
      (node (ref "D42") (pin "1") (pinfunction "K_1") (pintype "passive"))
      (node (ref "F20") (pin "1") (pinfunction "1_1") (pintype "passive"))
    )
    (net (code "81") (name "Net-(D42-A)") (class "Default")
      (node (ref "D42") (pin "2") (pinfunction "A_2") (pintype "passive"))
      (node (ref "D44") (pin "2") (pinfunction "A_2") (pintype "passive"))
      (node (ref "D46") (pin "1") (pinfunction "1_1") (pintype "passive"))
      (node (ref "P16") (pin "2") (pinfunction "2_2") (pintype "passive"))
    )
    (net (code "82") (name "Net-(D47--)") (class "Default")
      (node (ref "D47") (pin "1") (pinfunction "-_1") (pintype "passive"))
      (node (ref "L2") (pin "1") (pinfunction "1_1") (pintype "passive"))
      (node (ref "U9") (pin "2") (pinfunction "Output_2") (pintype "passive"))
    )
    (net (code "83") (name "Net-(DIP1-Pad5)") (class "Default")
      (node (ref "DIP1") (pin "5") (pinfunction "5_5") (pintype "passive"))
      (node (ref "R67") (pin "1") (pinfunction "1_1") (pintype "passive"))
    )
    (net (code "84") (name "Net-(DIP1-Pad7)") (class "Default")
      (node (ref "DIP1") (pin "7") (pinfunction "7_7") (pintype "passive"))
      (node (ref "R65") (pin "2") (pinfunction "2_2") (pintype "passive"))
    )
    (net (code "85") (name "Net-(DIP1-Pad8)") (class "Default")
      (node (ref "DIP1") (pin "8") (pinfunction "8_8") (pintype "passive"))
      (node (ref "R64") (pin "2") (pinfunction "2_2") (pintype "passive"))
    )
    (net (code "86") (name "Net-(F1-Pad1)") (class "Default")
      (node (ref "F1") (pin "1") (pinfunction "1_1") (pintype "passive"))
      (node (ref "P1") (pin "1") (pinfunction "1_1") (pintype "passive"))
    )
    (net (code "87") (name "Net-(F2-Pad2)") (class "Default")
      (node (ref "F2") (pin "2") (pinfunction "2_2") (pintype "passive"))
      (node (ref "P1") (pin "3") (pinfunction "3_3") (pintype "passive"))
    )
    (net (code "88") (name "Net-(F3-Pad1)") (class "Default")
      (node (ref "F3") (pin "1") (pinfunction "1_1") (pintype "passive"))
      (node (ref "P2") (pin "1") (pinfunction "1_1") (pintype "passive"))
    )
    (net (code "89") (name "Net-(F4-Pad2)") (class "Default")
      (node (ref "F4") (pin "2") (pinfunction "2_2") (pintype "passive"))
      (node (ref "P2") (pin "3") (pinfunction "3_3") (pintype "passive"))
    )
    (net (code "90") (name "Net-(F5-Pad1)") (class "Default")
      (node (ref "F5") (pin "1") (pinfunction "1_1") (pintype "passive"))
      (node (ref "P3") (pin "1") (pinfunction "1_1") (pintype "passive"))
    )
    (net (code "91") (name "Net-(F6-Pad2)") (class "Default")
      (node (ref "F6") (pin "2") (pinfunction "2_2") (pintype "passive"))
      (node (ref "P3") (pin "3") (pinfunction "3_3") (pintype "passive"))
    )
    (net (code "92") (name "Net-(F11-Pad1)") (class "Default")
      (node (ref "F11") (pin "1") (pinfunction "1_1") (pintype "passive"))
      (node (ref "P8") (pin "1") (pinfunction "1_1") (pintype "passive"))
    )
    (net (code "93") (name "Net-(F12-Pad2)") (class "Default")
      (node (ref "F12") (pin "2") (pinfunction "2_2") (pintype "passive"))
      (node (ref "P8") (pin "3") (pinfunction "3_3") (pintype "passive"))
    )
    (net (code "94") (name "Net-(F17-Pad1)") (class "Default")
      (node (ref "F17") (pin "1") (pinfunction "1_1") (pintype "passive"))
      (node (ref "P13") (pin "2") (pinfunction "2_2") (pintype "passive"))
    )
    (net (code "95") (name "Net-(F18-Pad2)") (class "Default")
      (node (ref "F18") (pin "2") (pinfunction "2_2") (pintype "passive"))
      (node (ref "P14") (pin "1") (pinfunction "1_1") (pintype "passive"))
    )
    (net (code "96") (name "Net-(F19-Pad2)") (class "Default")
      (node (ref "F19") (pin "2") (pinfunction "2_2") (pintype "passive"))
      (node (ref "P14") (pin "2") (pinfunction "2_2") (pintype "passive"))
    )
    (net (code "97") (name "Net-(LED1-K)") (class "Default")
      (node (ref "LED1") (pin "2") (pinfunction "K_2") (pintype "passive"))
      (node (ref "R22") (pin "1") (pinfunction "1_1") (pintype "passive"))
    )
    (net (code "98") (name "Net-(LED2-K)") (class "Default")
      (node (ref "LED2") (pin "2") (pinfunction "K_2") (pintype "passive"))
      (node (ref "R23") (pin "1") (pinfunction "1_1") (pintype "passive"))
    )
    (net (code "99") (name "Net-(LED3-K)") (class "Default")
      (node (ref "LED3") (pin "2") (pinfunction "K_2") (pintype "passive"))
      (node (ref "R24") (pin "1") (pinfunction "1_1") (pintype "passive"))
    )
    (net (code "100") (name "Net-(LED4-K)") (class "Default")
      (node (ref "LED4") (pin "2") (pinfunction "K_2") (pintype "passive"))
      (node (ref "R25") (pin "1") (pinfunction "1_1") (pintype "passive"))
    )
    (net (code "101") (name "Net-(LED5-K)") (class "Default")
      (node (ref "LED5") (pin "2") (pinfunction "K_2") (pintype "passive"))
      (node (ref "R44") (pin "1") (pinfunction "1_1") (pintype "passive"))
    )
    (net (code "102") (name "Net-(LED6-K)") (class "Default")
      (node (ref "LED6") (pin "2") (pinfunction "K_2") (pintype "passive"))
      (node (ref "R45") (pin "1") (pinfunction "1_1") (pintype "passive"))
    )
    (net (code "103") (name "Net-(LED7-K)") (class "Default")
      (node (ref "LED7") (pin "2") (pinfunction "K_2") (pintype "passive"))
      (node (ref "R46") (pin "1") (pinfunction "1_1") (pintype "passive"))
    )
    (net (code "104") (name "Net-(LED8-K)") (class "Default")
      (node (ref "LED8") (pin "2") (pinfunction "K_2") (pintype "passive"))
      (node (ref "R47") (pin "1") (pinfunction "1_1") (pintype "passive"))
    )
    (net (code "105") (name "Net-(LED9-K)") (class "Default")
      (node (ref "LED9") (pin "2") (pinfunction "K_2") (pintype "passive"))
      (node (ref "R87") (pin "1") (pinfunction "1_1") (pintype "passive"))
    )
    (net (code "106") (name "Net-(LED10-A)") (class "Default")
      (node (ref "LED10") (pin "1") (pinfunction "A_1") (pintype "passive"))
      (node (ref "R86") (pin "2") (pinfunction "2_2") (pintype "passive"))
    )
    (net (code "107") (name "Net-(LED10-K)") (class "Default")
      (node (ref "LED10") (pin "2") (pinfunction "K_2") (pintype "passive"))
      (node (ref "Q19") (pin "3") (pinfunction "D_3") (pintype "passive"))
    )
    (net (code "108") (name "Net-(P4-Pad1)") (class "Default")
      (node (ref "P4") (pin "1") (pinfunction "1_1") (pintype "passive"))
      (node (ref "RELAY1") (pin "2") (pinfunction "2_2") (pintype "passive"))
    )
    (net (code "109") (name "Net-(P4-Pad2)") (class "Default")
      (node (ref "P4") (pin "2") (pinfunction "2_2") (pintype "passive"))
      (node (ref "RELAY1") (pin "5") (pinfunction "5_5") (pintype "passive"))
    )
    (net (code "110") (name "Net-(P4-Pad3)") (class "Default")
      (node (ref "P4") (pin "3") (pinfunction "3_3") (pintype "passive"))
      (node (ref "RELAY1") (pin "3") (pinfunction "3_3") (pintype "passive"))
    )
    (net (code "111") (name "Net-(P5-Pad1)") (class "Default")
      (node (ref "P5") (pin "1") (pinfunction "1_1") (pintype "passive"))
      (node (ref "RELAY2") (pin "2") (pinfunction "2_2") (pintype "passive"))
    )
    (net (code "112") (name "Net-(P5-Pad2)") (class "Default")
      (node (ref "P5") (pin "2") (pinfunction "2_2") (pintype "passive"))
      (node (ref "RELAY2") (pin "5") (pinfunction "5_5") (pintype "passive"))
    )
    (net (code "113") (name "Net-(P5-Pad3)") (class "Default")
      (node (ref "P5") (pin "3") (pinfunction "3_3") (pintype "passive"))
      (node (ref "RELAY2") (pin "3") (pinfunction "3_3") (pintype "passive"))
    )
    (net (code "114") (name "Net-(P6-Pad1)") (class "Default")
      (node (ref "P6") (pin "1") (pinfunction "1_1") (pintype "passive"))
      (node (ref "RELAY3") (pin "2") (pinfunction "2_2") (pintype "passive"))
    )
    (net (code "115") (name "Net-(P6-Pad2)") (class "Default")
      (node (ref "P6") (pin "2") (pinfunction "2_2") (pintype "passive"))
      (node (ref "RELAY3") (pin "5") (pinfunction "5_5") (pintype "passive"))
    )
    (net (code "116") (name "Net-(P6-Pad3)") (class "Default")
      (node (ref "P6") (pin "3") (pinfunction "3_3") (pintype "passive"))
      (node (ref "RELAY3") (pin "3") (pinfunction "3_3") (pintype "passive"))
    )
    (net (code "117") (name "Net-(P7-Pad1)") (class "Default")
      (node (ref "P7") (pin "1") (pinfunction "1_1") (pintype "passive"))
      (node (ref "RELAY4") (pin "2") (pinfunction "2_2") (pintype "passive"))
    )
    (net (code "118") (name "Net-(P7-Pad2)") (class "Default")
      (node (ref "P7") (pin "2") (pinfunction "2_2") (pintype "passive"))
      (node (ref "RELAY4") (pin "5") (pinfunction "5_5") (pintype "passive"))
    )
    (net (code "119") (name "Net-(P7-Pad3)") (class "Default")
      (node (ref "P7") (pin "3") (pinfunction "3_3") (pintype "passive"))
      (node (ref "RELAY4") (pin "3") (pinfunction "3_3") (pintype "passive"))
    )
    (net (code "120") (name "Net-(P9-Pad1)") (class "Default")
      (node (ref "P9") (pin "1") (pinfunction "1_1") (pintype "passive"))
      (node (ref "RELAY5") (pin "2") (pinfunction "2_2") (pintype "passive"))
    )
    (net (code "121") (name "Net-(P9-Pad2)") (class "Default")
      (node (ref "P9") (pin "2") (pinfunction "2_2") (pintype "passive"))
      (node (ref "RELAY5") (pin "5") (pinfunction "5_5") (pintype "passive"))
    )
    (net (code "122") (name "Net-(P9-Pad3)") (class "Default")
      (node (ref "P9") (pin "3") (pinfunction "3_3") (pintype "passive"))
      (node (ref "RELAY5") (pin "3") (pinfunction "3_3") (pintype "passive"))
    )
    (net (code "123") (name "Net-(P10-Pad1)") (class "Default")
      (node (ref "P10") (pin "1") (pinfunction "1_1") (pintype "passive"))
      (node (ref "RELAY6") (pin "2") (pinfunction "2_2") (pintype "passive"))
    )
    (net (code "124") (name "Net-(P10-Pad2)") (class "Default")
      (node (ref "P10") (pin "2") (pinfunction "2_2") (pintype "passive"))
      (node (ref "RELAY6") (pin "5") (pinfunction "5_5") (pintype "passive"))
    )
    (net (code "125") (name "Net-(P10-Pad3)") (class "Default")
      (node (ref "P10") (pin "3") (pinfunction "3_3") (pintype "passive"))
      (node (ref "RELAY6") (pin "3") (pinfunction "3_3") (pintype "passive"))
    )
    (net (code "126") (name "Net-(P11-Pad1)") (class "Default")
      (node (ref "P11") (pin "1") (pinfunction "1_1") (pintype "passive"))
      (node (ref "RELAY7") (pin "2") (pinfunction "2_2") (pintype "passive"))
    )
    (net (code "127") (name "Net-(P11-Pad2)") (class "Default")
      (node (ref "P11") (pin "2") (pinfunction "2_2") (pintype "passive"))
      (node (ref "RELAY7") (pin "5") (pinfunction "5_5") (pintype "passive"))
    )
    (net (code "128") (name "Net-(P11-Pad3)") (class "Default")
      (node (ref "P11") (pin "3") (pinfunction "3_3") (pintype "passive"))
      (node (ref "RELAY7") (pin "3") (pinfunction "3_3") (pintype "passive"))
    )
    (net (code "129") (name "Net-(P12-Pad1)") (class "Default")
      (node (ref "P12") (pin "1") (pinfunction "1_1") (pintype "passive"))
      (node (ref "RELAY8") (pin "2") (pinfunction "2_2") (pintype "passive"))
    )
    (net (code "130") (name "Net-(P12-Pad2)") (class "Default")
      (node (ref "P12") (pin "2") (pinfunction "2_2") (pintype "passive"))
      (node (ref "RELAY8") (pin "5") (pinfunction "5_5") (pintype "passive"))
    )
    (net (code "131") (name "Net-(P12-Pad3)") (class "Default")
      (node (ref "P12") (pin "3") (pinfunction "3_3") (pintype "passive"))
      (node (ref "RELAY8") (pin "3") (pinfunction "3_3") (pintype "passive"))
    )
    (net (code "132") (name "Net-(Q1-G)") (class "Default")
      (node (ref "Q1") (pin "1") (pinfunction "G_1") (pintype "passive"))
      (node (ref "Q5") (pin "3") (pinfunction "C_3") (pintype "passive"))
      (node (ref "R27") (pin "2") (pinfunction "2_2") (pintype "passive"))
      (node (ref "R39") (pin "1") (pinfunction "1_1") (pintype "passive"))
    )
    (net (code "133") (name "Net-(Q2-G)") (class "Default")
      (node (ref "Q2") (pin "1") (pinfunction "G_1") (pintype "passive"))
      (node (ref "Q6") (pin "3") (pinfunction "C_3") (pintype "passive"))
      (node (ref "R29") (pin "2") (pinfunction "2_2") (pintype "passive"))
      (node (ref "R40") (pin "1") (pinfunction "1_1") (pintype "passive"))
    )
    (net (code "134") (name "Net-(Q3-G)") (class "Default")
      (node (ref "Q3") (pin "1") (pinfunction "G_1") (pintype "passive"))
      (node (ref "Q7") (pin "3") (pinfunction "C_3") (pintype "passive"))
      (node (ref "R31") (pin "2") (pinfunction "2_2") (pintype "passive"))
      (node (ref "R41") (pin "1") (pinfunction "1_1") (pintype "passive"))
    )
    (net (code "135") (name "Net-(Q4-G)") (class "Default")
      (node (ref "Q4") (pin "1") (pinfunction "G_1") (pintype "passive"))
      (node (ref "Q8") (pin "3") (pinfunction "C_3") (pintype "passive"))
      (node (ref "R33") (pin "2") (pinfunction "2_2") (pintype "passive"))
      (node (ref "R42") (pin "1") (pinfunction "1_1") (pintype "passive"))
    )
    (net (code "136") (name "Net-(Q5-B)") (class "Default")
      (node (ref "Q5") (pin "1") (pinfunction "B_1") (pintype "passive"))
      (node (ref "R35") (pin "1") (pinfunction "1_1") (pintype "passive"))
    )
    (net (code "137") (name "Net-(Q6-B)") (class "Default")
      (node (ref "Q6") (pin "1") (pinfunction "B_1") (pintype "passive"))
      (node (ref "R36") (pin "1") (pinfunction "1_1") (pintype "passive"))
    )
    (net (code "138") (name "Net-(Q7-B)") (class "Default")
      (node (ref "Q7") (pin "1") (pinfunction "B_1") (pintype "passive"))
      (node (ref "R37") (pin "1") (pinfunction "1_1") (pintype "passive"))
    )
    (net (code "139") (name "Net-(Q8-B)") (class "Default")
      (node (ref "Q8") (pin "1") (pinfunction "B_1") (pintype "passive"))
      (node (ref "R38") (pin "1") (pinfunction "1_1") (pintype "passive"))
    )
    (net (code "140") (name "Net-(Q10-G)") (class "Default")
      (node (ref "Q10") (pin "1") (pinfunction "G_1") (pintype "passive"))
      (node (ref "Q14") (pin "3") (pinfunction "C_3") (pintype "passive"))
      (node (ref "R51") (pin "2") (pinfunction "2_2") (pintype "passive"))
      (node (ref "R63") (pin "1") (pinfunction "1_1") (pintype "passive"))
    )
    (net (code "141") (name "Net-(Q11-G)") (class "Default")
      (node (ref "Q11") (pin "1") (pinfunction "G_1") (pintype "passive"))
      (node (ref "Q15") (pin "3") (pinfunction "C_3") (pintype "passive"))
      (node (ref "R53") (pin "2") (pinfunction "2_2") (pintype "passive"))
      (node (ref "R59") (pin "1") (pinfunction "1_1") (pintype "passive"))
    )
    (net (code "142") (name "Net-(Q12-G)") (class "Default")
      (node (ref "Q12") (pin "1") (pinfunction "G_1") (pintype "passive"))
      (node (ref "Q16") (pin "3") (pinfunction "C_3") (pintype "passive"))
      (node (ref "R55") (pin "2") (pinfunction "2_2") (pintype "passive"))
      (node (ref "R61") (pin "1") (pinfunction "1_1") (pintype "passive"))
    )
    (net (code "143") (name "Net-(Q13-B)") (class "Default")
      (node (ref "Q13") (pin "1") (pinfunction "B_1") (pintype "passive"))
      (node (ref "R56") (pin "1") (pinfunction "1_1") (pintype "passive"))
    )
    (net (code "144") (name "Net-(Q13-C)") (class "Default")
      (node (ref "Q13") (pin "3") (pinfunction "C_3") (pintype "passive"))
      (node (ref "Q9") (pin "1") (pinfunction "G_1") (pintype "passive"))
      (node (ref "R49") (pin "2") (pinfunction "2_2") (pintype "passive"))
      (node (ref "R62") (pin "1") (pinfunction "1_1") (pintype "passive"))
    )
    (net (code "145") (name "Net-(Q14-B)") (class "Default")
      (node (ref "Q14") (pin "1") (pinfunction "B_1") (pintype "passive"))
      (node (ref "R57") (pin "1") (pinfunction "1_1") (pintype "passive"))
    )
    (net (code "146") (name "Net-(Q15-B)") (class "Default")
      (node (ref "Q15") (pin "1") (pinfunction "B_1") (pintype "passive"))
      (node (ref "R58") (pin "1") (pinfunction "1_1") (pintype "passive"))
    )
    (net (code "147") (name "Net-(Q16-B)") (class "Default")
      (node (ref "Q16") (pin "1") (pinfunction "B_1") (pintype "passive"))
      (node (ref "R60") (pin "1") (pinfunction "1_1") (pintype "passive"))
    )
    (net (code "148") (name "Net-(Q17-B)") (class "Default")
      (node (ref "Q17") (pin "1") (pinfunction "B_1") (pintype "passive"))
      (node (ref "R68") (pin "1") (pinfunction "1_1") (pintype "passive"))
    )
    (net (code "149") (name "Net-(Q18-B)") (class "Default")
      (node (ref "Q18") (pin "1") (pinfunction "B_1") (pintype "passive"))
      (node (ref "R71") (pin "1") (pinfunction "1_1") (pintype "passive"))
    )
    (net (code "150") (name "Net-(Q19-G)") (class "Default")
      (node (ref "Q19") (pin "1") (pinfunction "G_1") (pintype "passive"))
      (node (ref "R85") (pin "2") (pinfunction "2_2") (pintype "passive"))
    )
    (net (code "151") (name "Net-(R10-Pad1)") (class "Default")
      (node (ref "R10") (pin "1") (pinfunction "1_1") (pintype "passive"))
      (node (ref "RJ1") (pin "12") (pinfunction "12_12") (pintype "passive"))
    )
    (net (code "152") (name "Net-(R13-Pad1)") (class "Default")
      (node (ref "R13") (pin "1") (pinfunction "1_1") (pintype "passive"))
      (node (ref "RJ1") (pin "14") (pinfunction "14_14") (pintype "passive"))
    )
    (net (code "153") (name "Net-(U1-VA1)") (class "Default")
      (node (ref "D11") (pin "1") (pinfunction "1_1") (pintype "passive"))
      (node (ref "RJ1") (pin "9") (pinfunction "9_9") (pintype "passive"))
      (node (ref "U1") (pin "1") (pinfunction "VA1_1") (pintype "passive"))
      (node (ref "U1") (pin "3") (pinfunction "VB1_3") (pintype "passive"))
    )
    (net (code "154") (name "Net-(U1-VA2)") (class "Default")
      (node (ref "D11") (pin "2") (pinfunction "2_2") (pintype "passive"))
      (node (ref "RJ1") (pin "10") (pinfunction "10_10") (pintype "passive"))
      (node (ref "U1") (pin "2") (pinfunction "VA2_2") (pintype "passive"))
      (node (ref "U1") (pin "4") (pinfunction "VB2_4") (pintype "passive"))
    )
    (net (code "155") (name "Net-(U2-CRS_DV{slash}MODE2)") (class "Default")
      (node (ref "R15") (pin "2") (pinfunction "2_2") (pintype "passive"))
      (node (ref "U2") (pin "11") (pinfunction "CRS_DV/MODE2_11") (pintype "passive"))
    )
    (net (code "156") (name "Net-(U2-RBIAS)") (class "Default")
      (node (ref "R11") (pin "1") (pinfunction "1_1") (pintype "passive"))
      (node (ref "U2") (pin "24") (pinfunction "RBIAS_24") (pintype "passive"))
    )
    (net (code "157") (name "Net-(U2-RXD0{slash}MODE0)") (class "Default")
      (node (ref "R14") (pin "2") (pinfunction "2_2") (pintype "passive"))
      (node (ref "U2") (pin "8") (pinfunction "RXD0/MODE0_8") (pintype "passive"))
    )
    (net (code "158") (name "Net-(U2-RXD1{slash}MODE1)") (class "Default")
      (node (ref "R12") (pin "2") (pinfunction "2_2") (pintype "passive"))
      (node (ref "U2") (pin "7") (pinfunction "RXD1/MODE1_7") (pintype "passive"))
    )
    (net (code "159") (name "Net-(U2-RXER{slash}PHYAD0)") (class "Default")
      (node (ref "R3") (pin "2") (pinfunction "2_2") (pintype "passive"))
      (node (ref "U2") (pin "10") (pinfunction "RXER/PHYAD0_10") (pintype "passive"))
    )
    (net (code "160") (name "Net-(U2-VDDCR)") (class "Default")
      (node (ref "C10") (pin "1") (pinfunction "1_1") (pintype "passive"))
      (node (ref "C9") (pin "1") (pinfunction "1_1") (pintype "passive"))
      (node (ref "U2") (pin "6") (pinfunction "VDDCR_6") (pintype "passive"))
    )
    (net (code "161") (name "Net-(U2-XTAL1{slash}CLKIN)") (class "Default")
      (node (ref "RN1") (pin "3") (pinfunction "3_3") (pintype "passive"))
      (node (ref "U2") (pin "5") (pinfunction "XTAL1/CLKIN_5") (pintype "passive"))
    )
    (net (code "162") (name "Net-(U2-nINT{slash}REFCLKO)") (class "Default")
      (node (ref "RN1") (pin "8") (pinfunction "8_8") (pintype "passive"))
      (node (ref "U2") (pin "14") (pinfunction "nINT/REFCLKO_14") (pintype "passive"))
    )
    (net (code "163") (name "Net-(U2-nRST)") (class "Default")
      (node (ref "C14") (pin "1") (pinfunction "1_1") (pintype "passive"))
      (node (ref "R2") (pin "2") (pinfunction "2_2") (pintype "passive"))
      (node (ref "U2") (pin "15") (pinfunction "nRST_15") (pintype "passive"))
    )
    (net (code "164") (name "Net-(U5-OUT)") (class "Default")
      (node (ref "C28") (pin "1") (pinfunction "1_1") (pintype "passive"))
      (node (ref "U5") (pin "1") (pinfunction "OUT_1") (pintype "passive"))
      (node (ref "U7") (pin "8") (pinfunction "VCC_8") (pintype "passive"))
    )
    (net (code "165") (name "Net-(U6-RST#)") (class "Default")
      (node (ref "R80") (pin "1") (pinfunction "1_1") (pintype "passive"))
      (node (ref "U6") (pin "9") (pinfunction "RST#_9") (pintype "passive"))
    )
    (net (code "166") (name "Net-(U7-VBAT)") (class "Default")
      (node (ref "BT1") (pin "1") (pinfunction "1_1") (pintype "passive"))
      (node (ref "U7") (pin "3") (pinfunction "VBAT_3") (pintype "passive"))
    )
    (net (code "167") (name "Net-(U7-X1)") (class "Default")
      (node (ref "U7") (pin "1") (pinfunction "X1_1") (pintype "passive"))
      (node (ref "X2") (pin "1") (pinfunction "OSC1_1") (pintype "passive"))
    )
    (net (code "168") (name "Net-(U7-X2)") (class "Default")
      (node (ref "U7") (pin "2") (pinfunction "X2_2") (pintype "passive"))
      (node (ref "X2") (pin "2") (pinfunction "OSC2_2") (pintype "passive"))
    )
    (net (code "169") (name "Net-(U8-IO14)") (class "Default")
      (node (ref "R84") (pin "1") (pinfunction "1_1") (pintype "passive"))
      (node (ref "R85") (pin "1") (pinfunction "1_1") (pintype "passive"))
      (node (ref "U8") (pin "13") (pinfunction "IO14_13") (pintype "passive"))
    )
    (net (code "170") (name "Net-(USB1-CC1)") (class "Default")
      (node (ref "R72") (pin "1") (pinfunction "1_1") (pintype "passive"))
      (node (ref "USB1") (pin "A5") (pinfunction "CC1_A5") (pintype "passive"))
    )
    (net (code "171") (name "Net-(USB1-CC2)") (class "Default")
      (node (ref "R73") (pin "1") (pinfunction "1_1") (pintype "passive"))
      (node (ref "USB1") (pin "B5") (pinfunction "CC2_B5") (pintype "passive"))
    )
    (net (code "172") (name "Net-(X1-Enable{slash}Disable)") (class "Default")
      (node (ref "R17") (pin "2") (pinfunction "2_2") (pintype "passive"))
      (node (ref "R18") (pin "1") (pinfunction "1_1") (pintype "passive"))
      (node (ref "X1") (pin "1") (pinfunction "Enable/Disable_1") (pintype "passive"))
    )
    (net (code "173") (name "Net-(X1-OUT)") (class "Default")
      (node (ref "RN1") (pin "6") (pinfunction "6_6") (pintype "passive"))
      (node (ref "RN1") (pin "7") (pinfunction "7_7") (pintype "passive"))
      (node (ref "X1") (pin "3") (pinfunction "OUT_3") (pintype "passive"))
    )
    (net (code "174") (name "unconnected-(BOOT-A-Pad1)") (class "Default")
      (node (ref "BOOT") (pin "1") (pinfunction "A_1") (pintype "passive+no_connect"))
    )
    (net (code "175") (name "unconnected-(BOOT-D-Pad4)") (class "Default")
      (node (ref "BOOT") (pin "4") (pinfunction "D_4") (pintype "passive+no_connect"))
    )
    (net (code "176") (name "unconnected-(EN-A-Pad1)") (class "Default")
      (node (ref "EN") (pin "1") (pinfunction "A_1") (pintype "passive+no_connect"))
    )
    (net (code "177") (name "unconnected-(EN-D-Pad4)") (class "Default")
      (node (ref "EN") (pin "4") (pinfunction "D_4") (pintype "passive+no_connect"))
    )
    (net (code "178") (name "unconnected-(H1-Pad2)") (class "Default")
      (node (ref "H1") (pin "2") (pinfunction "2_2") (pintype "passive+no_connect"))
    )
    (net (code "179") (name "unconnected-(H1-Pad3)") (class "Default")
      (node (ref "H1") (pin "3") (pinfunction "3_3") (pintype "passive+no_connect"))
    )
    (net (code "180") (name "unconnected-(H1-Pad6)") (class "Default")
      (node (ref "H1") (pin "6") (pinfunction "6_6") (pintype "passive+no_connect"))
    )
    (net (code "181") (name "unconnected-(RF1-SIG-Pad1)") (class "Default")
      (node (ref "RF1") (pin "1") (pinfunction "SIG_1") (pintype "passive"))
    )
    (net (code "182") (name "unconnected-(RJ1-Pad7)") (class "Default")
      (node (ref "RJ1") (pin "7") (pinfunction "7_7") (pintype "passive+no_connect"))
    )
    (net (code "183") (name "unconnected-(RJ1-Pad8)") (class "Default")
      (node (ref "RJ1") (pin "8") (pinfunction "8_8") (pintype "passive+no_connect"))
    )
    (net (code "184") (name "unconnected-(RN1-Pad4)") (class "Default")
      (node (ref "RN1") (pin "4") (pinfunction "4_4") (pintype "passive+no_connect"))
    )
    (net (code "185") (name "unconnected-(RN1-Pad5)") (class "Default")
      (node (ref "RN1") (pin "5") (pinfunction "5_5") (pintype "passive+no_connect"))
    )
    (net (code "186") (name "unconnected-(U1-AT{slash}DET+-Pad5)") (class "Default")
      (node (ref "U1") (pin "5") (pinfunction "AT/DET+_5") (pintype "passive+no_connect"))
    )
    (net (code "187") (name "unconnected-(U1-GND-Pad6)") (class "Default")
      (node (ref "U1") (pin "6") (pinfunction "GND_6") (pintype "passive+no_connect"))
    )
    (net (code "188") (name "unconnected-(U2-XTAL2-Pad4)") (class "Default")
      (node (ref "U2") (pin "4") (pinfunction "XTAL2_4") (pintype "passive+no_connect"))
    )
    (net (code "189") (name "unconnected-(U3-INT#-Pad13)") (class "Default")
      (node (ref "U3") (pin "13") (pinfunction "INT#_13") (pintype "passive+no_connect"))
    )
    (net (code "190") (name "unconnected-(U6-CTS-Pad23)") (class "Default")
      (node (ref "U6") (pin "23") (pinfunction "CTS_23") (pintype "passive+no_connect"))
    )
    (net (code "191") (name "unconnected-(U6-DCD-Pad1)") (class "Default")
      (node (ref "U6") (pin "1") (pinfunction "DCD_1") (pintype "passive+no_connect"))
    )
    (net (code "192") (name "unconnected-(U6-DSR-Pad27)") (class "Default")
      (node (ref "U6") (pin "27") (pinfunction "DSR_27") (pintype "passive+no_connect"))
    )
    (net (code "193") (name "unconnected-(U6-NC-Pad10)") (class "Default")
      (node (ref "U6") (pin "10") (pinfunction "NC_10") (pintype "passive+no_connect"))
    )
    (net (code "194") (name "unconnected-(U6-NC-Pad13)") (class "Default")
      (node (ref "U6") (pin "13") (pinfunction "NC_13") (pintype "passive+no_connect"))
    )
    (net (code "195") (name "unconnected-(U6-NC-Pad14)") (class "Default")
      (node (ref "U6") (pin "14") (pinfunction "NC_14") (pintype "passive+no_connect"))
    )
    (net (code "196") (name "unconnected-(U6-NC-Pad15)") (class "Default")
      (node (ref "U6") (pin "15") (pinfunction "NC_15") (pintype "passive+no_connect"))
    )
    (net (code "197") (name "unconnected-(U6-NC-Pad16)") (class "Default")
      (node (ref "U6") (pin "16") (pinfunction "NC_16") (pintype "passive+no_connect"))
    )
    (net (code "198") (name "unconnected-(U6-NC-Pad17)") (class "Default")
      (node (ref "U6") (pin "17") (pinfunction "NC_17") (pintype "passive+no_connect"))
    )
    (net (code "199") (name "unconnected-(U6-NC-Pad18)") (class "Default")
      (node (ref "U6") (pin "18") (pinfunction "NC_18") (pintype "passive+no_connect"))
    )
    (net (code "200") (name "unconnected-(U6-NC-Pad19)") (class "Default")
      (node (ref "U6") (pin "19") (pinfunction "NC_19") (pintype "passive+no_connect"))
    )
    (net (code "201") (name "unconnected-(U6-NC-Pad20)") (class "Default")
      (node (ref "U6") (pin "20") (pinfunction "NC_20") (pintype "passive+no_connect"))
    )
    (net (code "202") (name "unconnected-(U6-NC-Pad21)") (class "Default")
      (node (ref "U6") (pin "21") (pinfunction "NC_21") (pintype "passive+no_connect"))
    )
    (net (code "203") (name "unconnected-(U6-NC-Pad22)") (class "Default")
      (node (ref "U6") (pin "22") (pinfunction "NC_22") (pintype "passive+no_connect"))
    )
    (net (code "204") (name "unconnected-(U6-RI-Pad2)") (class "Default")
      (node (ref "U6") (pin "2") (pinfunction "RI_2") (pintype "passive+no_connect"))
    )
    (net (code "205") (name "unconnected-(U6-SUSPEND#-Pad11)") (class "Default")
      (node (ref "U6") (pin "11") (pinfunction "SUSPEND#_11") (pintype "passive+no_connect"))
    )
    (net (code "206") (name "unconnected-(U6-SUSPEND-Pad12)") (class "Default")
      (node (ref "U6") (pin "12") (pinfunction "SUSPEND_12") (pintype "passive+no_connect"))
    )
    (net (code "207") (name "unconnected-(U7-SQW{slash}OUT-Pad7)") (class "Default")
      (node (ref "U7") (pin "7") (pinfunction "SQW/OUT_7") (pintype "passive+no_connect"))
    )
    (net (code "208") (name "unconnected-(U8-CLK-Pad20)") (class "Default")
      (node (ref "U8") (pin "20") (pinfunction "CLK_20") (pintype "passive+no_connect"))
    )
    (net (code "209") (name "unconnected-(U8-CMD-Pad19)") (class "Default")
      (node (ref "U8") (pin "19") (pinfunction "CMD_19") (pintype "passive+no_connect"))
    )
    (net (code "210") (name "unconnected-(U8-IO2-Pad24)") (class "Default")
      (node (ref "U8") (pin "24") (pinfunction "IO2_24") (pintype "passive+no_connect"))
    )
    (net (code "211") (name "unconnected-(U8-IO15-Pad23)") (class "Default")
      (node (ref "U8") (pin "23") (pinfunction "IO15_23") (pintype "passive+no_connect"))
    )
    (net (code "212") (name "unconnected-(U8-IO34-Pad6)") (class "Default")
      (node (ref "U8") (pin "6") (pinfunction "IO34_6") (pintype "passive+no_connect"))
    )
    (net (code "213") (name "unconnected-(U8-IO35-Pad7)") (class "Default")
      (node (ref "U8") (pin "7") (pinfunction "IO35_7") (pintype "passive+no_connect"))
    )
    (net (code "214") (name "unconnected-(U8-NC-Pad32)") (class "Default")
      (node (ref "U8") (pin "32") (pinfunction "NC_32") (pintype "passive+no_connect"))
    )
    (net (code "215") (name "unconnected-(U8-SD0-Pad21)") (class "Default")
      (node (ref "U8") (pin "21") (pinfunction "SD0_21") (pintype "passive+no_connect"))
    )
    (net (code "216") (name "unconnected-(U8-SD1-Pad22)") (class "Default")
      (node (ref "U8") (pin "22") (pinfunction "SD1_22") (pintype "passive+no_connect"))
    )
    (net (code "217") (name "unconnected-(U8-SD2-Pad17)") (class "Default")
      (node (ref "U8") (pin "17") (pinfunction "SD2_17") (pintype "passive+no_connect"))
    )
    (net (code "218") (name "unconnected-(U8-SD3-Pad18)") (class "Default")
      (node (ref "U8") (pin "18") (pinfunction "SD3_18") (pintype "passive+no_connect"))
    )
    (net (code "219") (name "unconnected-(U8-SENSOR_VN-Pad5)") (class "Default")
      (node (ref "U8") (pin "5") (pinfunction "SENSOR_VN_5") (pintype "passive+no_connect"))
    )
    (net (code "220") (name "unconnected-(U8-SENSOR_VP-Pad4)") (class "Default")
      (node (ref "U8") (pin "4") (pinfunction "SENSOR_VP_4") (pintype "passive+no_connect"))
    )
    (net (code "221") (name "unconnected-(USB1-SUB1-PadA8)") (class "Default")
      (node (ref "USB1") (pin "A8") (pinfunction "SUB1_A8") (pintype "passive+no_connect"))
    )
    (net (code "222") (name "unconnected-(USB1-SUB2-PadB8)") (class "Default")
      (node (ref "USB1") (pin "B8") (pinfunction "SUB2_B8") (pintype "passive+no_connect"))
    )
  )
)
